# TB-OSW-DRV_V1_0.net
KiCad netlist of a schematic drawn in Altium Designer
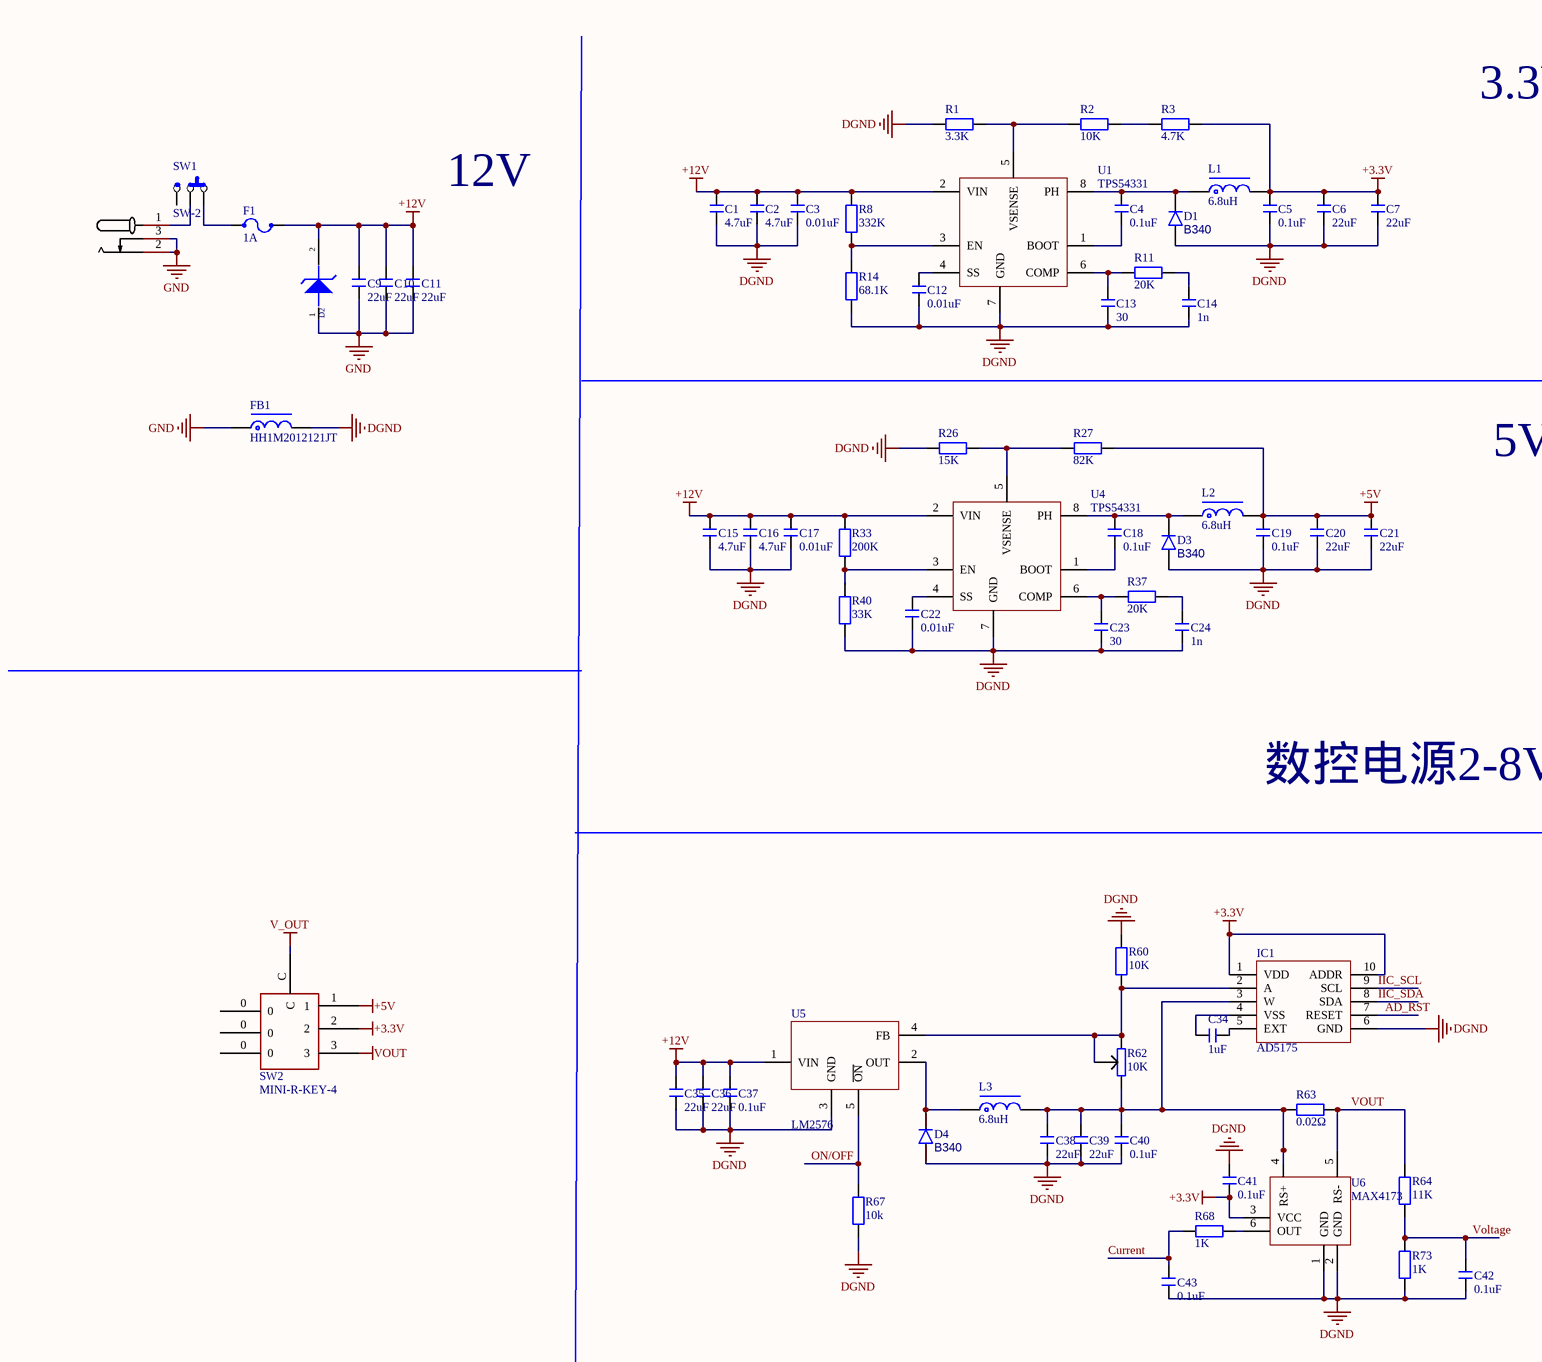
[diagram p0: TB-OSW-DRV V1.0.SchDoc, top left]
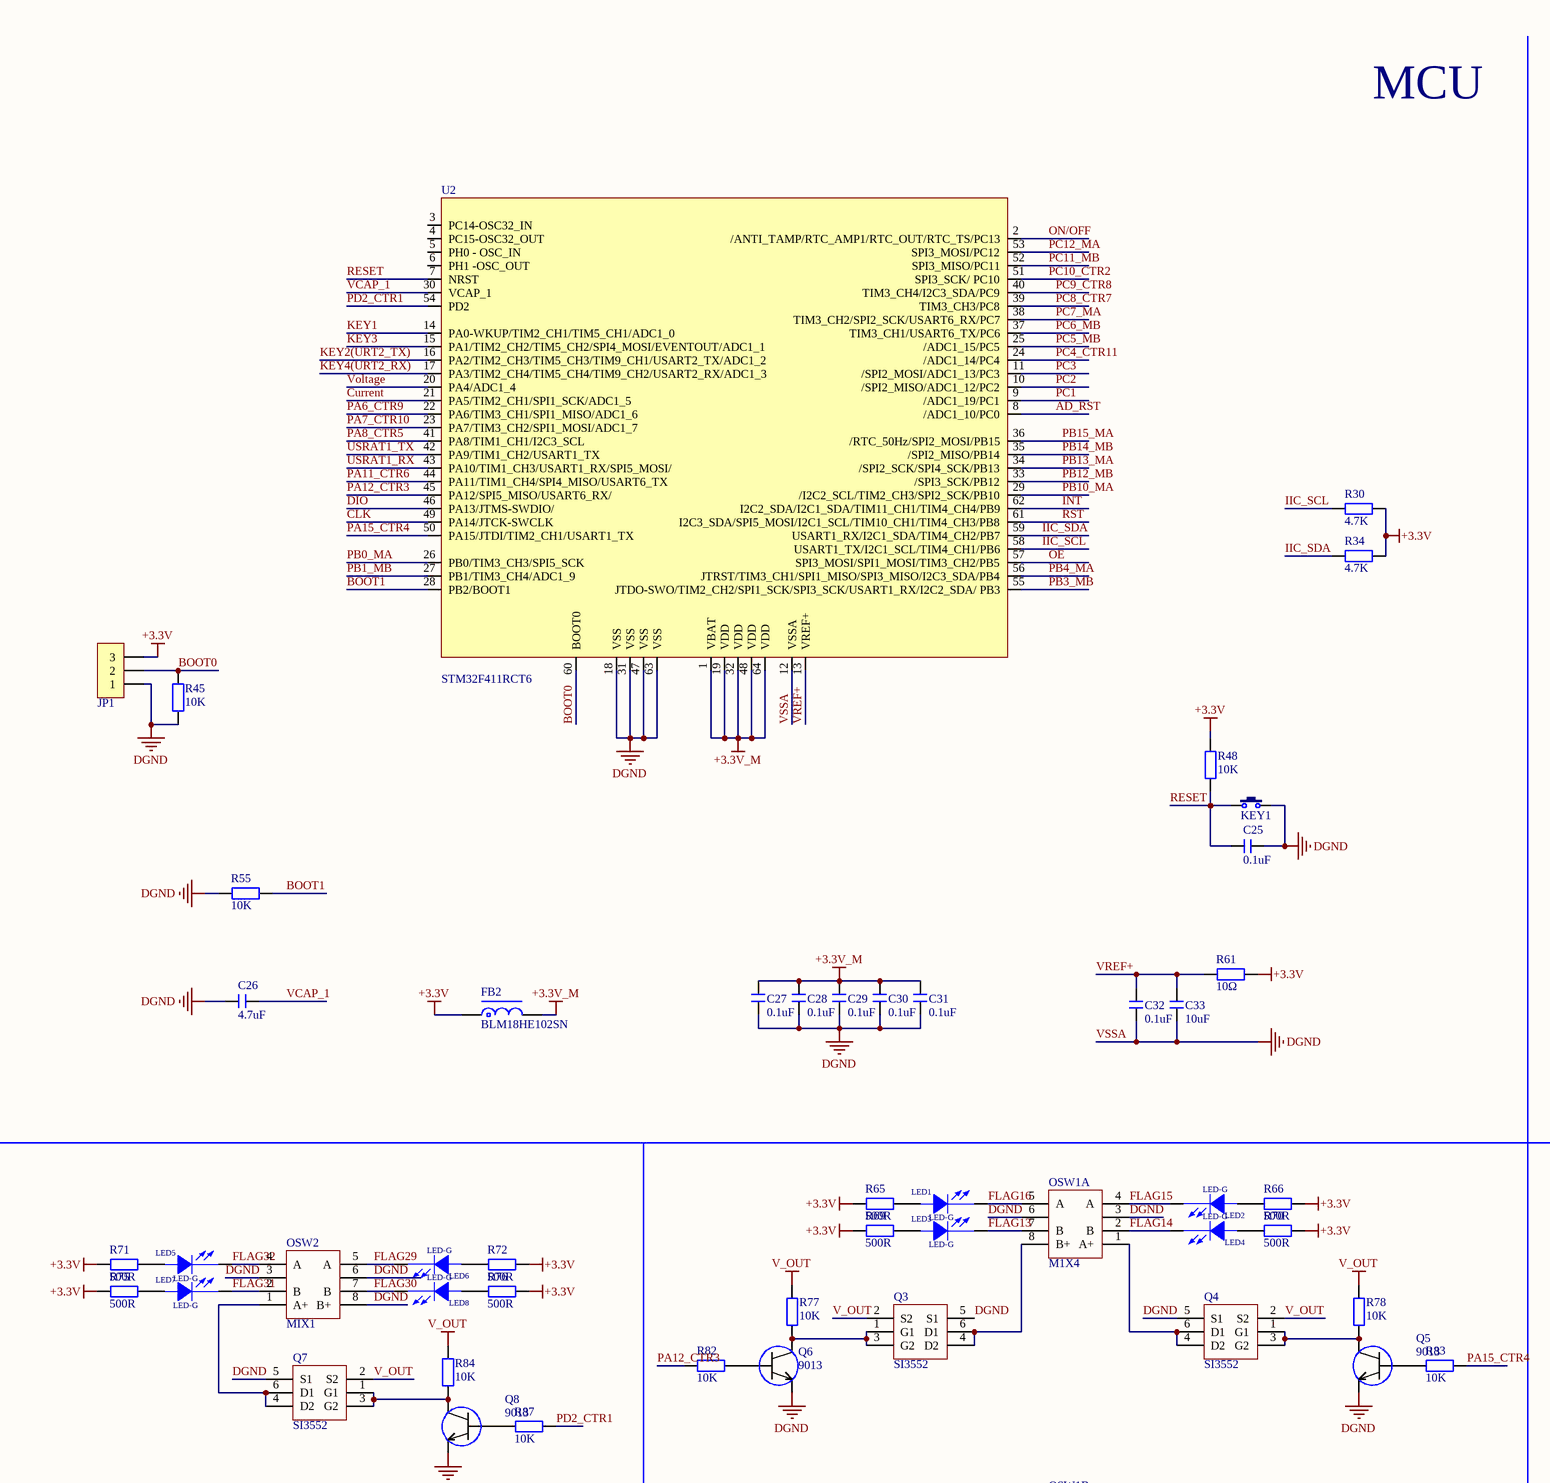
[diagram p1: TB-OSW-DRV V1.0.SchDoc, top middle]
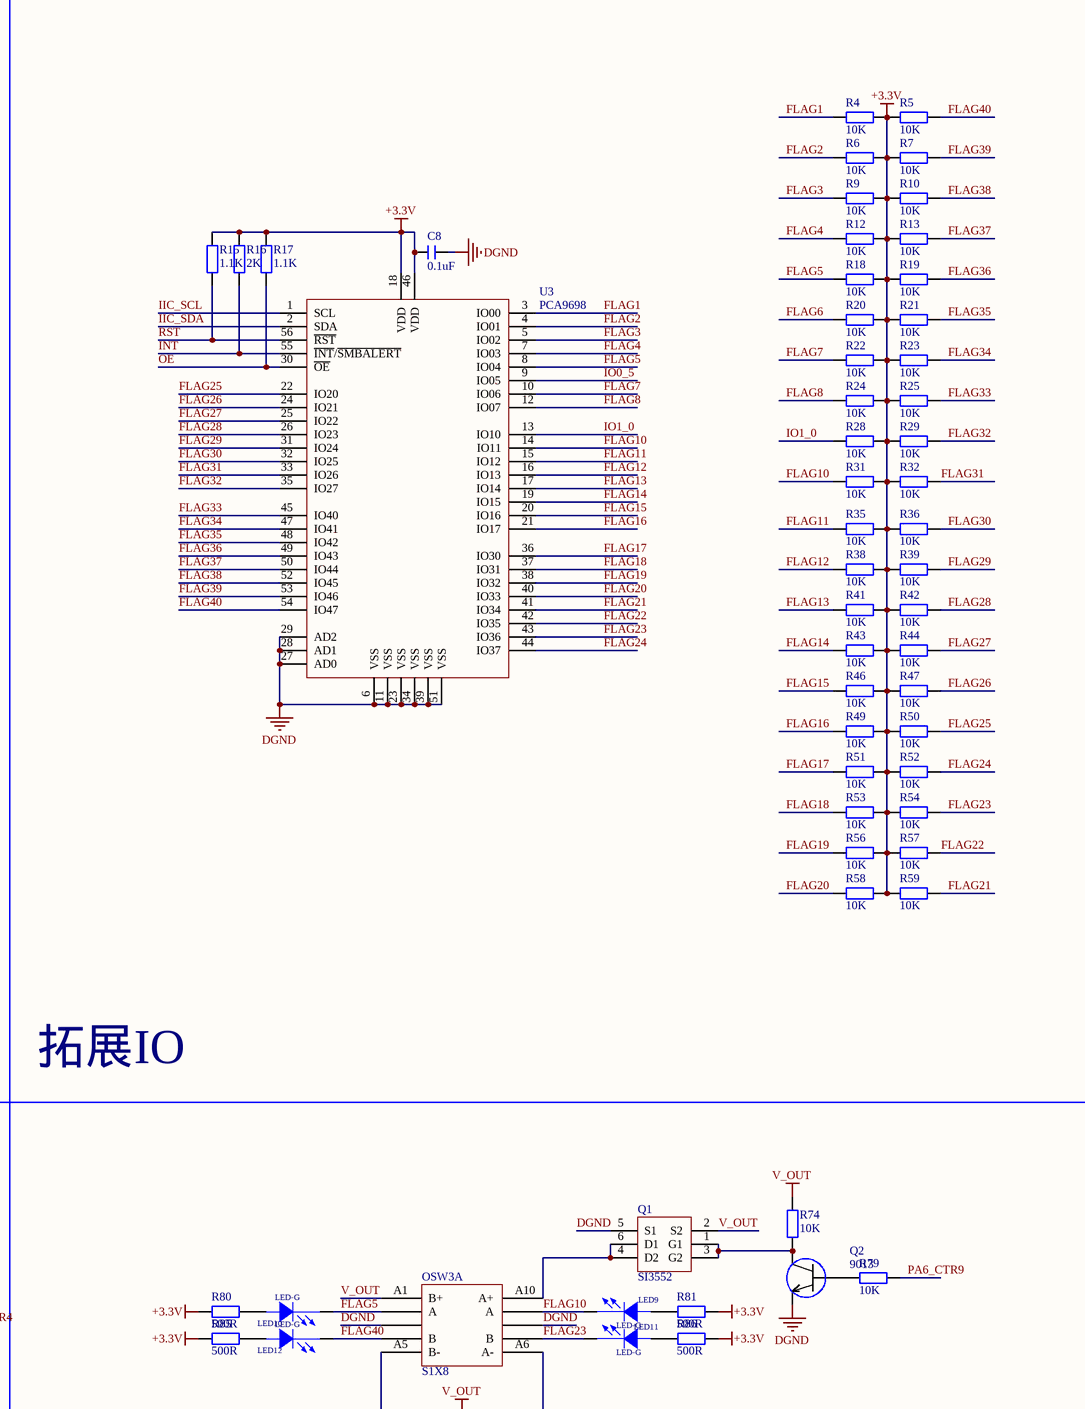
[diagram p2: TB-OSW-DRV V1.0.SchDoc, top right]
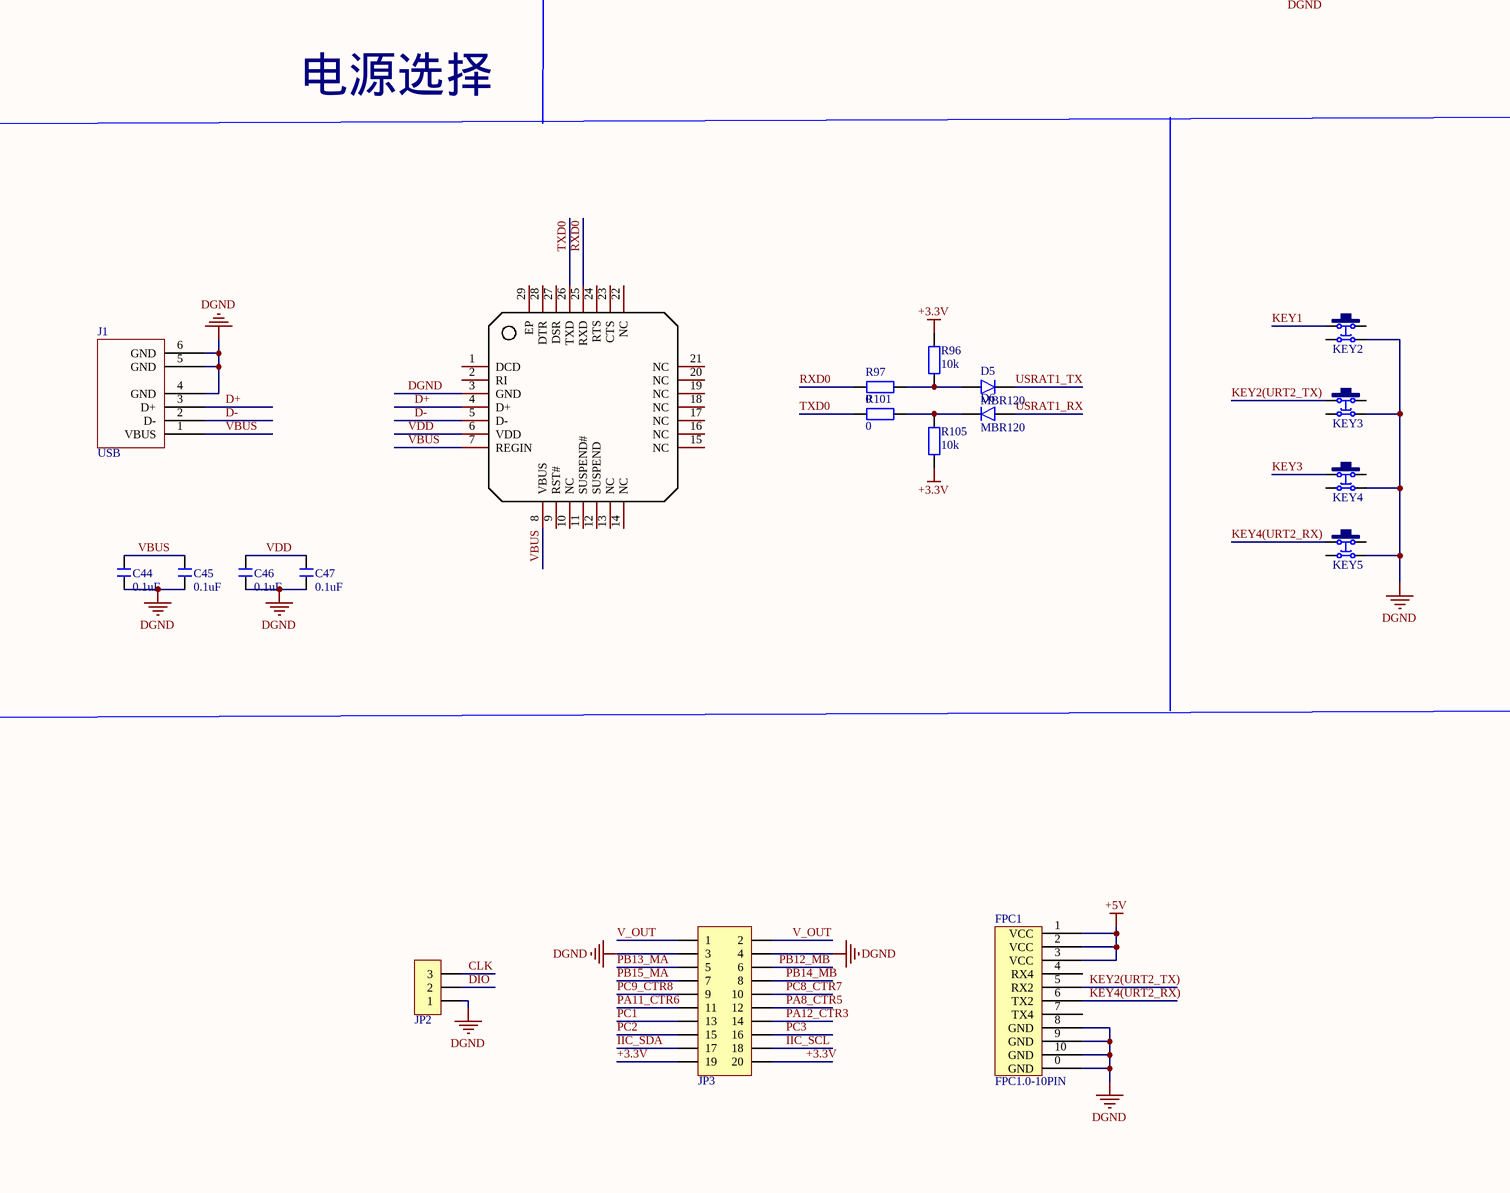
[diagram p3: TB-OSW-DRV V1.0.SchDoc, bottom left]
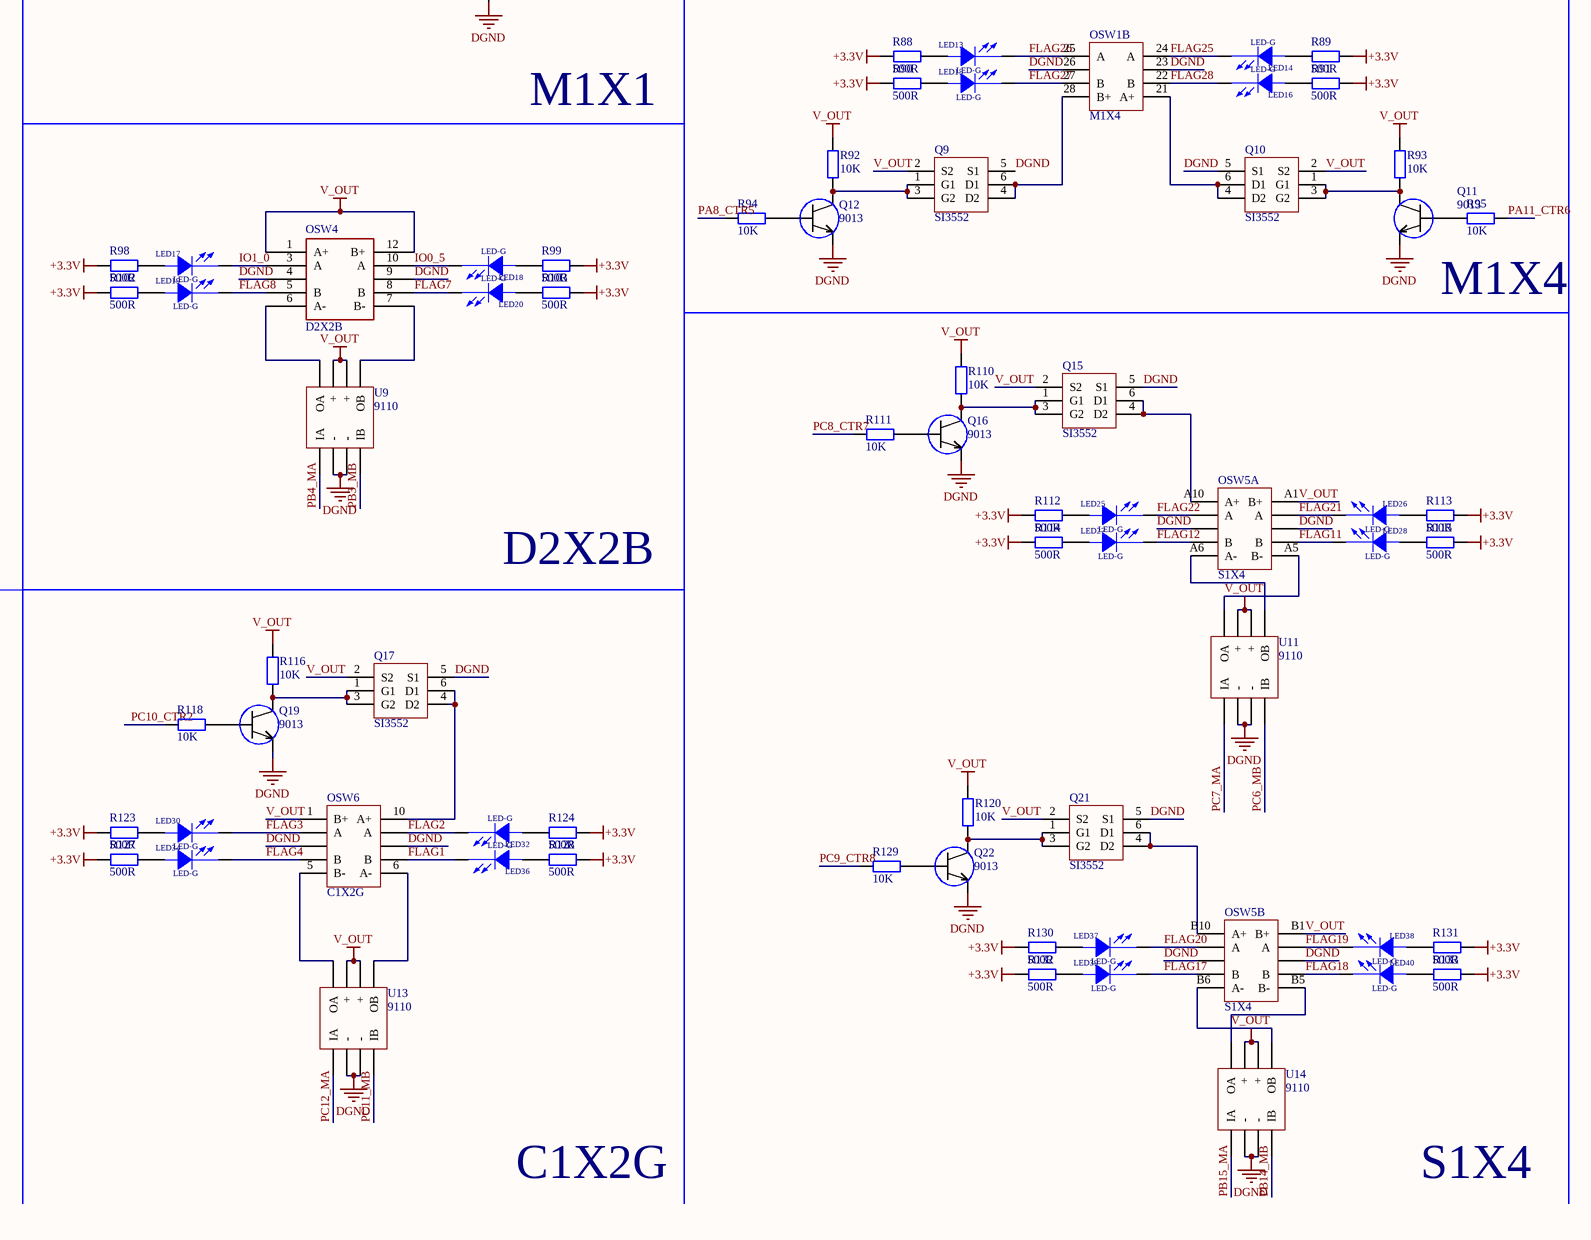
[diagram p4: TB-OSW-DRV V1.0.SchDoc, bottom middle]
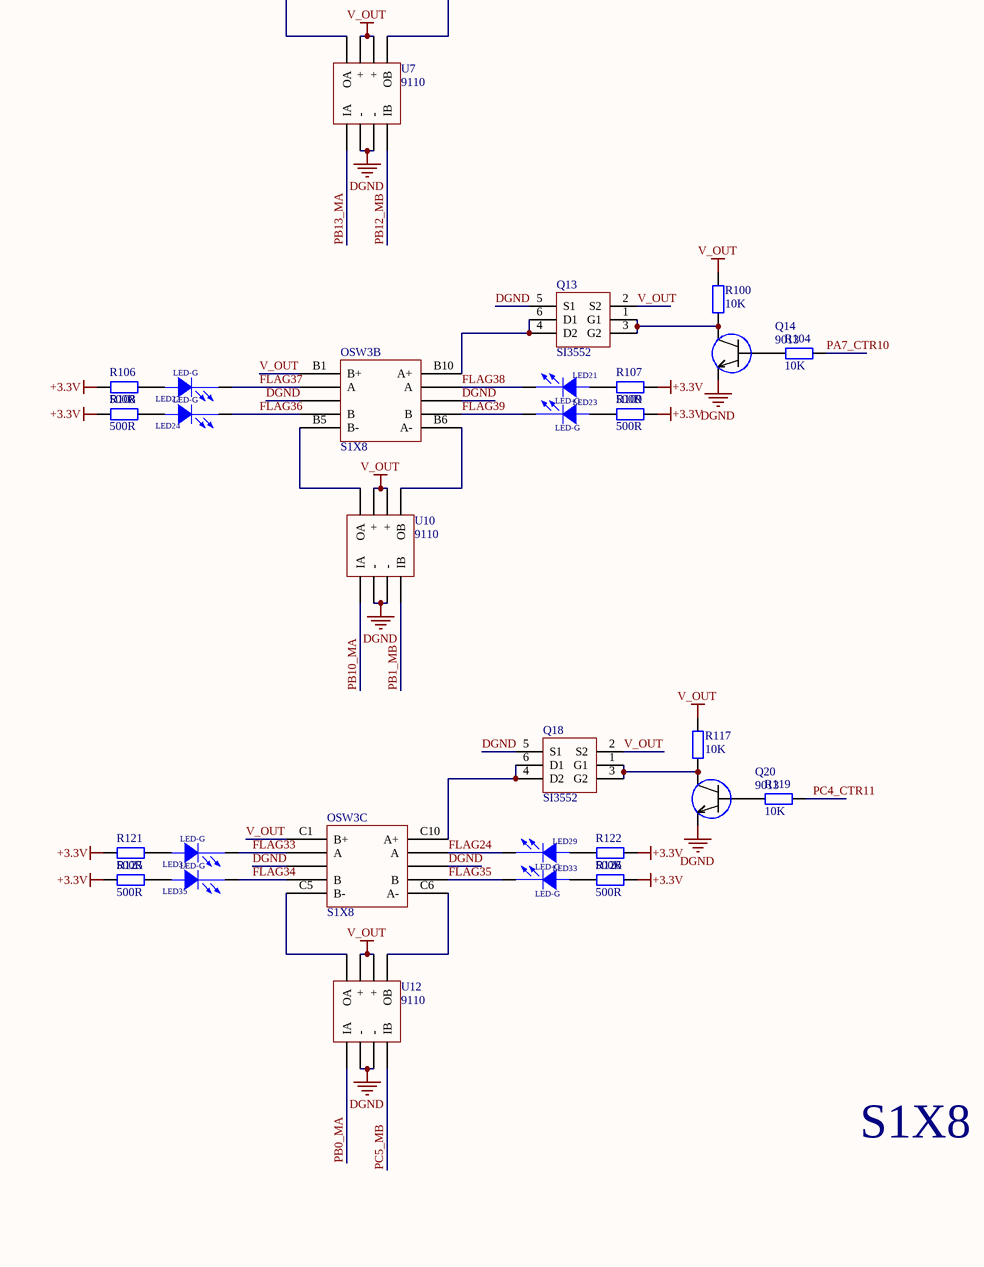
[diagram p5: TB-OSW-DRV V1.0.SchDoc, bottom right]

(export (version "E")
  (design (tool "Eeschema 10.0.6"))
  (components
    (comp (ref "C1")
      (value "4.7uF")
      (footprint "C 0805")
      (description "无极性贴片电容")
      (fields (field (name "版权归属") "源创客"))
      (libsource (lib "电阻-电容-电感") (part "C"))
    )
    (comp (ref "C2")
      (value "4.7uF")
      (footprint "C 0805")
      (description "无极性贴片电容")
      (fields (field (name "版权归属") "源创客"))
      (libsource (lib "电阻-电容-电感") (part "C"))
    )
    (comp (ref "C3")
      (value "0.01uF")
      (footprint "C 0805")
      (description "无极性贴片电容")
      (fields (field (name "版权归属") "源创客"))
      (libsource (lib "电阻-电容-电感") (part "C"))
    )
    (comp (ref "C4")
      (value "0.1uF")
      (footprint "C 0603")
      (description "无极性贴片电容")
      (fields (field (name "版权归属") "源创客"))
      (libsource (lib "电阻-电容-电感") (part "C"))
    )
    (comp (ref "C5")
      (value "0.1uF")
      (footprint "C 0603")
      (description "无极性贴片电容")
      (fields (field (name "版权归属") "源创客"))
      (libsource (lib "电阻-电容-电感") (part "C"))
    )
    (comp (ref "C6")
      (value "22uF")
      (footprint "C 0805")
      (description "无极性贴片电容")
      (fields (field (name "版权归属") "源创客"))
      (libsource (lib "电阻-电容-电感") (part "C"))
    )
    (comp (ref "C7")
      (value "22uF")
      (footprint "C 0805")
      (description "无极性贴片电容")
      (fields (field (name "版权归属") "源创客"))
      (libsource (lib "电阻-电容-电感") (part "C"))
    )
    (comp (ref "C8")
      (value "0.1uF")
      (footprint "C 0603")
      (description "无极性贴片电容")
      (fields (field (name "版权归属") "源创客"))
      (libsource (lib "电阻-电容-电感") (part "C"))
    )
    (comp (ref "C9")
      (value "22uF")
      (footprint "C 1206")
      (description "无极性贴片电容")
      (fields (field (name "版权归属") "源创客"))
      (libsource (lib "电阻-电容-电感") (part "C"))
    )
    (comp (ref "C10")
      (value "22uF")
      (footprint "C 1206")
      (description "无极性贴片电容")
      (fields (field (name "版权归属") "源创客"))
      (libsource (lib "电阻-电容-电感") (part "C"))
    )
    (comp (ref "C11")
      (value "22uF")
      (footprint "C 1206")
      (description "无极性贴片电容")
      (fields (field (name "版权归属") "源创客"))
      (libsource (lib "电阻-电容-电感") (part "C"))
    )
    (comp (ref "C12")
      (value "0.01uF")
      (footprint "C 0603")
      (description "无极性贴片电容")
      (fields (field (name "版权归属") "源创客"))
      (libsource (lib "电阻-电容-电感") (part "C"))
    )
    (comp (ref "C13")
      (value "30")
      (footprint "C 0603")
      (description "无极性贴片电容")
      (fields (field (name "版权归属") "源创客"))
      (libsource (lib "电阻-电容-电感") (part "C"))
    )
    (comp (ref "C14")
      (value "1n")
      (footprint "C 0603")
      (description "无极性贴片电容")
      (fields (field (name "版权归属") "源创客"))
      (libsource (lib "电阻-电容-电感") (part "C"))
    )
    (comp (ref "C15")
      (value "4.7uF")
      (footprint "C 0805")
      (description "无极性贴片电容")
      (fields (field (name "版权归属") "源创客"))
      (libsource (lib "电阻-电容-电感") (part "C"))
    )
    (comp (ref "C16")
      (value "4.7uF")
      (footprint "C 0805")
      (description "无极性贴片电容")
      (fields (field (name "版权归属") "源创客"))
      (libsource (lib "电阻-电容-电感") (part "C"))
    )
    (comp (ref "C17")
      (value "0.01uF")
      (footprint "C 0805")
      (description "无极性贴片电容")
      (fields (field (name "版权归属") "源创客"))
      (libsource (lib "电阻-电容-电感") (part "C"))
    )
    (comp (ref "C18")
      (value "0.1uF")
      (footprint "C 0603")
      (description "无极性贴片电容")
      (fields (field (name "版权归属") "源创客"))
      (libsource (lib "电阻-电容-电感") (part "C"))
    )
    (comp (ref "C19")
      (value "0.1uF")
      (footprint "C 0603")
      (description "无极性贴片电容")
      (fields (field (name "版权归属") "源创客"))
      (libsource (lib "电阻-电容-电感") (part "C"))
    )
    (comp (ref "C20")
      (value "22uF")
      (footprint "C 0805")
      (description "无极性贴片电容")
      (fields (field (name "版权归属") "源创客"))
      (libsource (lib "电阻-电容-电感") (part "C"))
    )
    (comp (ref "C21")
      (value "22uF")
      (footprint "C 0805")
      (description "无极性贴片电容")
      (fields (field (name "版权归属") "源创客"))
      (libsource (lib "电阻-电容-电感") (part "C"))
    )
    (comp (ref "C22")
      (value "0.01uF")
      (footprint "C 0603")
      (description "无极性贴片电容")
      (fields (field (name "版权归属") "源创客"))
      (libsource (lib "电阻-电容-电感") (part "C"))
    )
    (comp (ref "C23")
      (value "30")
      (footprint "C 0603")
      (description "无极性贴片电容")
      (fields (field (name "版权归属") "源创客"))
      (libsource (lib "电阻-电容-电感") (part "C"))
    )
    (comp (ref "C24")
      (value "1n")
      (footprint "C 0603")
      (description "无极性贴片电容")
      (fields (field (name "版权归属") "源创客"))
      (libsource (lib "电阻-电容-电感") (part "C"))
    )
    (comp (ref "C25")
      (value "0.1uF")
      (footprint "C 0603")
      (description "无极性贴片电容")
      (fields (field (name "版权归属") "源创客"))
      (libsource (lib "电阻-电容-电感") (part "C"))
    )
    (comp (ref "C26")
      (value "4.7uF")
      (footprint "C 0603")
      (description "无极性贴片电容")
      (fields (field (name "版权归属") "源创客"))
      (libsource (lib "电阻-电容-电感") (part "C"))
    )
    (comp (ref "C27")
      (value "0.1uF")
      (footprint "C 0603")
      (description "无极性贴片电容")
      (fields (field (name "版权归属") "源创客"))
      (libsource (lib "电阻-电容-电感") (part "C"))
    )
    (comp (ref "C28")
      (value "0.1uF")
      (footprint "C 0603")
      (description "无极性贴片电容")
      (fields (field (name "版权归属") "源创客"))
      (libsource (lib "电阻-电容-电感") (part "C"))
    )
    (comp (ref "C29")
      (value "0.1uF")
      (footprint "C 0603")
      (description "无极性贴片电容")
      (fields (field (name "版权归属") "源创客"))
      (libsource (lib "电阻-电容-电感") (part "C"))
    )
    (comp (ref "C30")
      (value "0.1uF")
      (footprint "C 0603")
      (description "无极性贴片电容")
      (fields (field (name "版权归属") "源创客"))
      (libsource (lib "电阻-电容-电感") (part "C"))
    )
    (comp (ref "C31")
      (value "0.1uF")
      (footprint "C 0603")
      (description "无极性贴片电容")
      (fields (field (name "版权归属") "源创客"))
      (libsource (lib "电阻-电容-电感") (part "C"))
    )
    (comp (ref "C32")
      (value "0.1uF")
      (footprint "C 0603")
      (description "无极性贴片电容")
      (fields (field (name "版权归属") "源创客"))
      (libsource (lib "电阻-电容-电感") (part "C"))
    )
    (comp (ref "C33")
      (value "10uF")
      (footprint "C 0603")
      (description "无极性贴片电容")
      (fields (field (name "版权归属") "源创客"))
      (libsource (lib "电阻-电容-电感") (part "C"))
    )
    (comp (ref "C34")
      (value "1uF")
      (footprint "C 0603")
      (description "无极性贴片电容")
      (fields (field (name "版权归属") "源创客"))
      (libsource (lib "电阻-电容-电感") (part "C"))
    )
    (comp (ref "C35")
      (value "22uF")
      (footprint "C 1206")
      (description "无极性贴片电容")
      (fields (field (name "版权归属") "源创客"))
      (libsource (lib "电阻-电容-电感") (part "C"))
    )
    (comp (ref "C36")
      (value "22uF")
      (footprint "C 1206")
      (description "无极性贴片电容")
      (fields (field (name "版权归属") "源创客"))
      (libsource (lib "电阻-电容-电感") (part "C"))
    )
    (comp (ref "C37")
      (value "0.1uF")
      (footprint "C 0603")
      (description "无极性贴片电容")
      (fields (field (name "版权归属") "源创客"))
      (libsource (lib "电阻-电容-电感") (part "C"))
    )
    (comp (ref "C38")
      (value "22uF")
      (footprint "C 0805")
      (description "无极性贴片电容")
      (fields (field (name "版权归属") "源创客"))
      (libsource (lib "电阻-电容-电感") (part "C"))
    )
    (comp (ref "C39")
      (value "22uF")
      (footprint "C 0805")
      (description "无极性贴片电容")
      (fields (field (name "版权归属") "源创客"))
      (libsource (lib "电阻-电容-电感") (part "C"))
    )
    (comp (ref "C40")
      (value "0.1uF")
      (footprint "C 0603")
      (description "无极性贴片电容")
      (fields (field (name "版权归属") "源创客"))
      (libsource (lib "电阻-电容-电感") (part "C"))
    )
    (comp (ref "C41")
      (value "0.1uF")
      (footprint "C 0603")
      (description "无极性贴片电容")
      (fields (field (name "版权归属") "源创客"))
      (libsource (lib "电阻-电容-电感") (part "C"))
    )
    (comp (ref "C42")
      (value "0.1uF")
      (footprint "C 0603")
      (description "无极性贴片电容")
      (fields (field (name "版权归属") "源创客"))
      (libsource (lib "电阻-电容-电感") (part "C"))
    )
    (comp (ref "C43")
      (value "0.1uF")
      (footprint "C 0603")
      (description "无极性贴片电容")
      (fields (field (name "版权归属") "源创客"))
      (libsource (lib "电阻-电容-电感") (part "C"))
    )
    (comp (ref "C44")
      (value "0.1uF")
      (footprint "C 0603")
      (description "无极性贴片电容")
      (fields (field (name "版权归属") "源创客"))
      (libsource (lib "电阻-电容-电感") (part "C"))
    )
    (comp (ref "C45")
      (value "0.1uF")
      (footprint "C 0603")
      (description "无极性贴片电容")
      (fields (field (name "版权归属") "源创客"))
      (libsource (lib "电阻-电容-电感") (part "C"))
    )
    (comp (ref "C46")
      (value "0.1uF")
      (footprint "C 0603")
      (description "无极性贴片电容")
      (fields (field (name "版权归属") "源创客"))
      (libsource (lib "电阻-电容-电感") (part "C"))
    )
    (comp (ref "C47")
      (value "0.1uF")
      (footprint "C 0603")
      (description "无极性贴片电容")
      (fields (field (name "版权归属") "源创客"))
      (libsource (lib "电阻-电容-电感") (part "C"))
    )
    (comp (ref "D1")
      (value "B340")
      (footprint "d1808")
      (libsource (lib "New_Integrated_Library") (part "DIODE"))
    )
    (comp (ref "D2")
      (value "TVS_SDO5C_SOD-323")
      (footprint "SOD-323")
      (description "1455000041")
      (libsource (lib "New_Integrated_Library") (part "TVS_SDO5C_SOD-323"))
    )
    (comp (ref "D3")
      (value "B340")
      (footprint "d1808")
      (libsource (lib "New_Integrated_Library") (part "DIODE"))
    )
    (comp (ref "D4")
      (value "B340")
      (footprint "d1808")
      (libsource (lib "New_Integrated_Library") (part "DIODE"))
    )
    (comp (ref "D5") (value "MBR120") (footprint "SOD-123") (libsource (lib "Schlib2") (part "MRB120")))
    (comp (ref "D6") (value "MBR120") (footprint "SOD-123") (libsource (lib "Schlib2") (part "MRB120")))
    (comp (ref "DC1")
      (value "DC005")
      (footprint "DC-IN-TH_DC005")
      (fields (field (name "MANUFACTURER") "SHOU HAN(首韩)"))
      (libsource (lib "New_Integrated_Library") (part "DC005"))
    )
    (comp (ref "F1") (value "1A") (footprint "R1206") (libsource (lib "Schlib2") (part "FUSE")))
    (comp (ref "FB1")
      (value "HH1M2012121JT")
      (footprint "L 0805")
      (description "小功率贴片电感")
      (fields (field (name "版权归属") "源创客"))
      (libsource (lib "电阻-电容-电感") (part "L"))
    )
    (comp (ref "FB2")
      (value "BLM18HE102SN")
      (footprint "L 0805")
      (description "小功率贴片电感")
      (fields (field (name "版权归属") "源创客"))
      (libsource (lib "电阻-电容-电感") (part "L"))
    )
    (comp (ref "FPC1")
      (value "FPC1.0-10PIN")
      (footprint "FPC1.0-2H-WS-10P")
      (libsource (lib "Schlib2") (part "2.4迪文串口屏"))
    )
    (comp (ref "IC1") (value "AD5175") (footprint "AD5175") (libsource (lib "Schlib2") (part "AD5175")))
    (comp (ref "J1") (value "USB") (footprint "USB-B") (libsource (lib "Schlib2") (part "USB")))
    (comp (ref "JP1")
      (value "HDR-1X3")
      (footprint "HDR-1X3")
      (description "3P接插件")
      (fields (field (name "版权归属") "源创客"))
      (libsource (lib "接插件") (part "Header 3"))
    )
    (comp (ref "JP2")
      (value "HDR-1X3")
      (footprint "HDR-1X3")
      (description "3P接插件")
      (fields (field (name "版权归属") "源创客"))
      (libsource (lib "接插件") (part "Header 3"))
    )
    (comp (ref "JP3")
      (value "Header 2X10")
      (footprint "HDR-10X2")
      (description "10*2P接插件")
      (fields (field (name "版权归属") "源创客"))
      (libsource (lib "接插件") (part "Header 10X2"))
    )
    (comp (ref "KEY1")
      (value "3x6x5")
      (footprint "TSW SMD-3*6*2.5")
      (description "3x6轻触开关")
      (fields (field (name "版权归属") "源创客"))
      (libsource (lib "按键-开关") (part "TSW 3x6"))
    )
    (comp (ref "KEY2")
      (value "12x12x5")
      (footprint "TSW DIP-12*12*11")
      (description "直插12x12轻触开关")
      (fields (field (name "版权归属") "源创客"))
      (libsource (lib "按键-开关") (part "TSW DIP-12x12"))
    )
    (comp (ref "KEY3")
      (value "12x12x5")
      (footprint "TSW DIP-12*12*11")
      (description "直插12x12轻触开关")
      (fields (field (name "版权归属") "源创客"))
      (libsource (lib "按键-开关") (part "TSW DIP-12x12"))
    )
    (comp (ref "KEY4")
      (value "12x12x5")
      (footprint "TSW DIP-12*12*11")
      (description "直插12x12轻触开关")
      (fields (field (name "版权归属") "源创客"))
      (libsource (lib "按键-开关") (part "TSW DIP-12x12"))
    )
    (comp (ref "KEY5")
      (value "12x12x5")
      (footprint "TSW DIP-12*12*11")
      (description "直插12x12轻触开关")
      (fields (field (name "版权归属") "源创客"))
      (libsource (lib "按键-开关") (part "TSW DIP-12x12"))
    )
    (comp (ref "L1")
      (value "6.8uH")
      (footprint "CD54")
      (description "贴片功率电感")
      (fields (field (name "版权归属") "源创客"))
      (libsource (lib "电阻-电容-电感") (part "L-CD"))
    )
    (comp (ref "L2")
      (value "6.8uH")
      (footprint "CD54")
      (description "贴片功率电感")
      (fields (field (name "版权归属") "源创客"))
      (libsource (lib "电阻-电容-电感") (part "L-CD"))
    )
    (comp (ref "L3")
      (value "6.8uH")
      (footprint "CD54")
      (description "贴片功率电感")
      (fields (field (name "版权归属") "源创客"))
      (libsource (lib "电阻-电容-电感") (part "L-CD"))
    )
    (comp (ref "LED1")
      (value "LED-G")
      (footprint "D0603B")
      (description "5110400395")
      (fields (field (name "Comment") "D_LED-G_D0603"))
      (libsource (lib "Schlib2") (part "D_LED-G_D0603"))
    )
    (comp (ref "LED2")
      (value "LED-G")
      (footprint "D0603B")
      (description "5110400395")
      (fields (field (name "Comment") "D_LED-G_D0603"))
      (libsource (lib "Schlib2") (part "D_LED-G_D0603"))
    )
    (comp (ref "LED3")
      (value "LED-G")
      (footprint "D0603B")
      (description "5110400395")
      (fields (field (name "Comment") "D_LED-G_D0603"))
      (libsource (lib "Schlib2") (part "D_LED-G_D0603"))
    )
    (comp (ref "LED4")
      (value "LED-G")
      (footprint "D0603B")
      (description "5110400395")
      (fields (field (name "Comment") "D_LED-G_D0603"))
      (libsource (lib "Schlib2") (part "D_LED-G_D0603"))
    )
    (comp (ref "LED5")
      (value "LED-G")
      (footprint "D0603B")
      (description "5110400395")
      (fields (field (name "Comment") "D_LED-G_D0603"))
      (libsource (lib "Schlib2") (part "D_LED-G_D0603"))
    )
    (comp (ref "LED6")
      (value "LED-G")
      (footprint "D0603B")
      (description "5110400395")
      (fields (field (name "Comment") "D_LED-G_D0603"))
      (libsource (lib "Schlib2") (part "D_LED-G_D0603"))
    )
    (comp (ref "LED7")
      (value "LED-G")
      (footprint "D0603B")
      (description "5110400395")
      (fields (field (name "Comment") "D_LED-G_D0603"))
      (libsource (lib "Schlib2") (part "D_LED-G_D0603"))
    )
    (comp (ref "LED8")
      (value "LED-G")
      (footprint "D0603B")
      (description "5110400395")
      (fields (field (name "Comment") "D_LED-G_D0603"))
      (libsource (lib "Schlib2") (part "D_LED-G_D0603"))
    )
    (comp (ref "LED9")
      (value "LED-G")
      (footprint "D0603B")
      (description "5110400395")
      (fields (field (name "Comment") "D_LED-G_D0603"))
      (libsource (lib "Schlib2") (part "D_LED-G_D0603"))
    )
    (comp (ref "LED10")
      (value "LED-G")
      (footprint "D0603B")
      (description "5110400395")
      (fields (field (name "Comment") "D_LED-G_D0603"))
      (libsource (lib "Schlib2") (part "D_LED-G_D0603"))
    )
    (comp (ref "LED11")
      (value "LED-G")
      (footprint "D0603B")
      (description "5110400395")
      (fields (field (name "Comment") "D_LED-G_D0603"))
      (libsource (lib "Schlib2") (part "D_LED-G_D0603"))
    )
    (comp (ref "LED12")
      (value "LED-G")
      (footprint "D0603B")
      (description "5110400395")
      (fields (field (name "Comment") "D_LED-G_D0603"))
      (libsource (lib "Schlib2") (part "D_LED-G_D0603"))
    )
    (comp (ref "LED13")
      (value "LED-G")
      (footprint "D0603B")
      (description "5110400395")
      (fields (field (name "Comment") "D_LED-G_D0603"))
      (libsource (lib "Schlib2") (part "D_LED-G_D0603"))
    )
    (comp (ref "LED14")
      (value "LED-G")
      (footprint "D0603B")
      (description "5110400395")
      (fields (field (name "Comment") "D_LED-G_D0603"))
      (libsource (lib "Schlib2") (part "D_LED-G_D0603"))
    )
    (comp (ref "LED15")
      (value "LED-G")
      (footprint "D0603B")
      (description "5110400395")
      (fields (field (name "Comment") "D_LED-G_D0603"))
      (libsource (lib "Schlib2") (part "D_LED-G_D0603"))
    )
    (comp (ref "LED16")
      (value "LED-G")
      (footprint "D0603B")
      (description "5110400395")
      (fields (field (name "Comment") "D_LED-G_D0603"))
      (libsource (lib "Schlib2") (part "D_LED-G_D0603"))
    )
    (comp (ref "LED17")
      (value "LED-G")
      (footprint "D0603B")
      (description "5110400395")
      (fields (field (name "Comment") "D_LED-G_D0603"))
      (libsource (lib "Schlib2") (part "D_LED-G_D0603"))
    )
    (comp (ref "LED18")
      (value "LED-G")
      (footprint "D0603B")
      (description "5110400395")
      (fields (field (name "Comment") "D_LED-G_D0603"))
      (libsource (lib "Schlib2") (part "D_LED-G_D0603"))
    )
    (comp (ref "LED19")
      (value "LED-G")
      (footprint "D0603B")
      (description "5110400395")
      (fields (field (name "Comment") "D_LED-G_D0603"))
      (libsource (lib "Schlib2") (part "D_LED-G_D0603"))
    )
    (comp (ref "LED20")
      (value "LED-G")
      (footprint "D0603B")
      (description "5110400395")
      (fields (field (name "Comment") "D_LED-G_D0603"))
      (libsource (lib "Schlib2") (part "D_LED-G_D0603"))
    )
    (comp (ref "LED21")
      (value "LED-G")
      (footprint "D0603B")
      (description "5110400395")
      (fields (field (name "Comment") "D_LED-G_D0603"))
      (libsource (lib "Schlib2") (part "D_LED-G_D0603"))
    )
    (comp (ref "LED22")
      (value "LED-G")
      (footprint "D0603B")
      (description "5110400395")
      (fields (field (name "Comment") "D_LED-G_D0603"))
      (libsource (lib "Schlib2") (part "D_LED-G_D0603"))
    )
    (comp (ref "LED23")
      (value "LED-G")
      (footprint "D0603B")
      (description "5110400395")
      (fields (field (name "Comment") "D_LED-G_D0603"))
      (libsource (lib "Schlib2") (part "D_LED-G_D0603"))
    )
    (comp (ref "LED24")
      (value "LED-G")
      (footprint "D0603B")
      (description "5110400395")
      (fields (field (name "Comment") "D_LED-G_D0603"))
      (libsource (lib "Schlib2") (part "D_LED-G_D0603"))
    )
    (comp (ref "LED25")
      (value "LED-G")
      (footprint "D0603B")
      (description "5110400395")
      (fields (field (name "Comment") "D_LED-G_D0603"))
      (libsource (lib "Schlib2") (part "D_LED-G_D0603"))
    )
    (comp (ref "LED26")
      (value "LED-G")
      (footprint "D0603B")
      (description "5110400395")
      (fields (field (name "Comment") "D_LED-G_D0603"))
      (libsource (lib "Schlib2") (part "D_LED-G_D0603"))
    )
    (comp (ref "LED27")
      (value "LED-G")
      (footprint "D0603B")
      (description "5110400395")
      (fields (field (name "Comment") "D_LED-G_D0603"))
      (libsource (lib "Schlib2") (part "D_LED-G_D0603"))
    )
    (comp (ref "LED28")
      (value "LED-G")
      (footprint "D0603B")
      (description "5110400395")
      (fields (field (name "Comment") "D_LED-G_D0603"))
      (libsource (lib "Schlib2") (part "D_LED-G_D0603"))
    )
    (comp (ref "LED29")
      (value "LED-G")
      (footprint "D0603B")
      (description "5110400395")
      (fields (field (name "Comment") "D_LED-G_D0603"))
      (libsource (lib "Schlib2") (part "D_LED-G_D0603"))
    )
    (comp (ref "LED30")
      (value "LED-G")
      (footprint "D0603B")
      (description "5110400395")
      (fields (field (name "Comment") "D_LED-G_D0603"))
      (libsource (lib "Schlib2") (part "D_LED-G_D0603"))
    )
    (comp (ref "LED31")
      (value "LED-G")
      (footprint "D0603B")
      (description "5110400395")
      (fields (field (name "Comment") "D_LED-G_D0603"))
      (libsource (lib "Schlib2") (part "D_LED-G_D0603"))
    )
    (comp (ref "LED32")
      (value "LED-G")
      (footprint "D0603B")
      (description "5110400395")
      (fields (field (name "Comment") "D_LED-G_D0603"))
      (libsource (lib "Schlib2") (part "D_LED-G_D0603"))
    )
    (comp (ref "LED33")
      (value "LED-G")
      (footprint "D0603B")
      (description "5110400395")
      (fields (field (name "Comment") "D_LED-G_D0603"))
      (libsource (lib "Schlib2") (part "D_LED-G_D0603"))
    )
    (comp (ref "LED34")
      (value "LED-G")
      (footprint "D0603B")
      (description "5110400395")
      (fields (field (name "Comment") "D_LED-G_D0603"))
      (libsource (lib "Schlib2") (part "D_LED-G_D0603"))
    )
    (comp (ref "LED35")
      (value "LED-G")
      (footprint "D0603B")
      (description "5110400395")
      (fields (field (name "Comment") "D_LED-G_D0603"))
      (libsource (lib "Schlib2") (part "D_LED-G_D0603"))
    )
    (comp (ref "LED36")
      (value "LED-G")
      (footprint "D0603B")
      (description "5110400395")
      (fields (field (name "Comment") "D_LED-G_D0603"))
      (libsource (lib "Schlib2") (part "D_LED-G_D0603"))
    )
    (comp (ref "LED37")
      (value "LED-G")
      (footprint "D0603B")
      (description "5110400395")
      (fields (field (name "Comment") "D_LED-G_D0603"))
      (libsource (lib "Schlib2") (part "D_LED-G_D0603"))
    )
    (comp (ref "LED38")
      (value "LED-G")
      (footprint "D0603B")
      (description "5110400395")
      (fields (field (name "Comment") "D_LED-G_D0603"))
      (libsource (lib "Schlib2") (part "D_LED-G_D0603"))
    )
    (comp (ref "LED39")
      (value "LED-G")
      (footprint "D0603B")
      (description "5110400395")
      (fields (field (name "Comment") "D_LED-G_D0603"))
      (libsource (lib "Schlib2") (part "D_LED-G_D0603"))
    )
    (comp (ref "LED40")
      (value "LED-G")
      (footprint "D0603B")
      (description "5110400395")
      (fields (field (name "Comment") "D_LED-G_D0603"))
      (libsource (lib "Schlib2") (part "D_LED-G_D0603"))
    )
    (comp (ref "OSW1")
      (value "M1X4")
      (footprint "MIN1X4")
      (libsource (lib "New_Integrated_Library") (part "OSWM2"))
    )
    (comp (ref "OSW2")
      (value "MIX1")
      (footprint "M1X1 - duplicate")
      (libsource (lib "New_Integrated_Library") (part "OSWM1"))
    )
    (comp (ref "OSW3")
      (value "S1X8")
      (footprint "S1X8 - duplicate")
      (libsource (lib "New_Integrated_Library") (part "OSW3"))
    )
    (comp (ref "OSW4")
      (value "D2X2B")
      (footprint "D2X2B - duplicate")
      (libsource (lib "Schlib2") (part "D2X2B"))
    )
    (comp (ref "OSW5")
      (value "S1X4")
      (footprint "S1X4 - duplicate")
      (libsource (lib "New_Integrated_Library") (part "OSW2"))
    )
    (comp (ref "OSW6")
      (value "C1X2G")
      (footprint "C1X2G - duplicate")
      (libsource (lib "New_Integrated_Library") (part "OSW1"))
    )
    (comp (ref "Q1") (value "SI3552") (footprint "3552") (libsource (lib "") (part "SI3552_1")))
    (comp (ref "Q2") (value "9013") (footprint "SOT-23") (libsource (lib "Schlib2") (part "S9013_SOT23")))
    (comp (ref "Q3") (value "SI3552") (footprint "3552") (libsource (lib "Schlib2") (part "SI3552")))
    (comp (ref "Q4") (value "SI3552") (footprint "3552") (libsource (lib "") (part "SI3552_1")))
    (comp (ref "Q5") (value "9013") (footprint "SOT-23") (libsource (lib "Schlib2") (part "S9013_SOT23")))
    (comp (ref "Q6") (value "9013") (footprint "SOT-23") (libsource (lib "") (part "S9013_SOT23_1")))
    (comp (ref "Q7") (value "SI3552") (footprint "3552") (libsource (lib "") (part "SI3552_1")))
    (comp (ref "Q8") (value "9013") (footprint "SOT-23") (libsource (lib "Schlib2") (part "S9013_SOT23")))
    (comp (ref "Q9") (value "SI3552") (footprint "3552") (libsource (lib "Schlib2") (part "SI3552")))
    (comp (ref "Q10") (value "SI3552") (footprint "3552") (libsource (lib "") (part "SI3552_1")))
    (comp (ref "Q11") (value "9013") (footprint "SOT-23") (libsource (lib "Schlib2") (part "S9013_SOT23")))
    (comp (ref "Q12") (value "9013") (footprint "SOT-23") (libsource (lib "") (part "S9013_SOT23_1")))
    (comp (ref "Q13") (value "SI3552") (footprint "3552") (libsource (lib "") (part "SI3552_1")))
    (comp (ref "Q14") (value "9013") (footprint "SOT-23") (libsource (lib "Schlib2") (part "S9013_SOT23")))
    (comp (ref "Q15") (value "SI3552") (footprint "3552") (libsource (lib "Schlib2") (part "SI3552")))
    (comp (ref "Q16") (value "9013") (footprint "SOT-23") (libsource (lib "") (part "S9013_SOT23_1")))
    (comp (ref "Q17") (value "SI3552") (footprint "3552") (libsource (lib "Schlib2") (part "SI3552")))
    (comp (ref "Q18") (value "SI3552") (footprint "3552") (libsource (lib "") (part "SI3552_1")))
    (comp (ref "Q19") (value "9013") (footprint "SOT-23") (libsource (lib "") (part "S9013_SOT23_1")))
    (comp (ref "Q20") (value "9013") (footprint "SOT-23") (libsource (lib "Schlib2") (part "S9013_SOT23")))
    (comp (ref "Q21") (value "SI3552") (footprint "3552") (libsource (lib "Schlib2") (part "SI3552")))
    (comp (ref "Q22") (value "9013") (footprint "SOT-23") (libsource (lib "") (part "S9013_SOT23_1")))
    (comp (ref "R1")
      (value "3.3K")
      (footprint "R 0603")
      (description "贴片电阻")
      (fields (field (name "版权归属") "源创客"))
      (libsource (lib "电阻-电容-电感") (part "R"))
    )
    (comp (ref "R2")
      (value "10K")
      (footprint "R 0603")
      (description "贴片电阻")
      (fields (field (name "版权归属") "源创客"))
      (libsource (lib "电阻-电容-电感") (part "R"))
    )
    (comp (ref "R3")
      (value "4.7K")
      (footprint "R 0603")
      (description "贴片电阻")
      (fields (field (name "版权归属") "源创客"))
      (libsource (lib "电阻-电容-电感") (part "R"))
    )
    (comp (ref "R4")
      (value "10K")
      (footprint "R 0603")
      (description "贴片电阻")
      (fields (field (name "版权归属") "源创客"))
      (libsource (lib "电阻-电容-电感") (part "R"))
    )
    (comp (ref "R5")
      (value "10K")
      (footprint "R 0603")
      (description "贴片电阻")
      (fields (field (name "版权归属") "源创客"))
      (libsource (lib "电阻-电容-电感") (part "R"))
    )
    (comp (ref "R6")
      (value "10K")
      (footprint "R 0603")
      (description "贴片电阻")
      (fields (field (name "版权归属") "源创客"))
      (libsource (lib "电阻-电容-电感") (part "R"))
    )
    (comp (ref "R7")
      (value "10K")
      (footprint "R 0603")
      (description "贴片电阻")
      (fields (field (name "版权归属") "源创客"))
      (libsource (lib "电阻-电容-电感") (part "R"))
    )
    (comp (ref "R8")
      (value "332K")
      (footprint "R 0603")
      (description "贴片电阻")
      (fields (field (name "版权归属") "源创客"))
      (libsource (lib "电阻-电容-电感") (part "R"))
    )
    (comp (ref "R9")
      (value "10K")
      (footprint "R 0603")
      (description "贴片电阻")
      (fields (field (name "版权归属") "源创客"))
      (libsource (lib "电阻-电容-电感") (part "R"))
    )
    (comp (ref "R10")
      (value "10K")
      (footprint "R 0603")
      (description "贴片电阻")
      (fields (field (name "版权归属") "源创客"))
      (libsource (lib "电阻-电容-电感") (part "R"))
    )
    (comp (ref "R11")
      (value "20K")
      (footprint "R 0603")
      (description "贴片电阻")
      (fields (field (name "版权归属") "源创客"))
      (libsource (lib "电阻-电容-电感") (part "R"))
    )
    (comp (ref "R12")
      (value "10K")
      (footprint "R 0603")
      (description "贴片电阻")
      (fields (field (name "版权归属") "源创客"))
      (libsource (lib "电阻-电容-电感") (part "R"))
    )
    (comp (ref "R13")
      (value "10K")
      (footprint "R 0603")
      (description "贴片电阻")
      (fields (field (name "版权归属") "源创客"))
      (libsource (lib "电阻-电容-电感") (part "R"))
    )
    (comp (ref "R14")
      (value "68.1K")
      (footprint "R 0603")
      (description "贴片电阻")
      (fields (field (name "版权归属") "源创客"))
      (libsource (lib "电阻-电容-电感") (part "R"))
    )
    (comp (ref "R15")
      (value "1.1K")
      (footprint "R 0603")
      (description "贴片电阻")
      (fields (field (name "版权归属") "源创客"))
      (libsource (lib "电阻-电容-电感") (part "R"))
    )
    (comp (ref "R16")
      (value "2K")
      (footprint "R 0603")
      (description "贴片电阻")
      (fields (field (name "版权归属") "源创客"))
      (libsource (lib "电阻-电容-电感") (part "R"))
    )
    (comp (ref "R17")
      (value "1.1K")
      (footprint "R 0603")
      (description "贴片电阻")
      (fields (field (name "版权归属") "源创客"))
      (libsource (lib "电阻-电容-电感") (part "R"))
    )
    (comp (ref "R18")
      (value "10K")
      (footprint "R 0603")
      (description "贴片电阻")
      (fields (field (name "版权归属") "源创客"))
      (libsource (lib "电阻-电容-电感") (part "R"))
    )
    (comp (ref "R19")
      (value "10K")
      (footprint "R 0603")
      (description "贴片电阻")
      (fields (field (name "版权归属") "源创客"))
      (libsource (lib "电阻-电容-电感") (part "R"))
    )
    (comp (ref "R20")
      (value "10K")
      (footprint "R 0603")
      (description "贴片电阻")
      (fields (field (name "版权归属") "源创客"))
      (libsource (lib "电阻-电容-电感") (part "R"))
    )
    (comp (ref "R21")
      (value "10K")
      (footprint "R 0603")
      (description "贴片电阻")
      (fields (field (name "版权归属") "源创客"))
      (libsource (lib "电阻-电容-电感") (part "R"))
    )
    (comp (ref "R22")
      (value "10K")
      (footprint "R 0603")
      (description "贴片电阻")
      (fields (field (name "版权归属") "源创客"))
      (libsource (lib "电阻-电容-电感") (part "R"))
    )
    (comp (ref "R23")
      (value "10K")
      (footprint "R 0603")
      (description "贴片电阻")
      (fields (field (name "版权归属") "源创客"))
      (libsource (lib "电阻-电容-电感") (part "R"))
    )
    (comp (ref "R24")
      (value "10K")
      (footprint "R 0603")
      (description "贴片电阻")
      (fields (field (name "版权归属") "源创客"))
      (libsource (lib "电阻-电容-电感") (part "R"))
    )
    (comp (ref "R25")
      (value "10K")
      (footprint "R 0603")
      (description "贴片电阻")
      (fields (field (name "版权归属") "源创客"))
      (libsource (lib "电阻-电容-电感") (part "R"))
    )
    (comp (ref "R26")
      (value "15K")
      (footprint "R 0603")
      (description "贴片电阻")
      (fields (field (name "版权归属") "源创客"))
      (libsource (lib "电阻-电容-电感") (part "R"))
    )
    (comp (ref "R27")
      (value "82K")
      (footprint "R 0603")
      (description "贴片电阻")
      (fields (field (name "版权归属") "源创客"))
      (libsource (lib "电阻-电容-电感") (part "R"))
    )
    (comp (ref "R28")
      (value "10K")
      (footprint "R 0603")
      (description "贴片电阻")
      (fields (field (name "版权归属") "源创客"))
      (libsource (lib "电阻-电容-电感") (part "R"))
    )
    (comp (ref "R29")
      (value "10K")
      (footprint "R 0603")
      (description "贴片电阻")
      (fields (field (name "版权归属") "源创客"))
      (libsource (lib "电阻-电容-电感") (part "R"))
    )
    (comp (ref "R30")
      (value "4.7K")
      (footprint "R 0603")
      (description "贴片电阻")
      (fields (field (name "版权归属") "源创客"))
      (libsource (lib "电阻-电容-电感") (part "R"))
    )
    (comp (ref "R31")
      (value "10K")
      (footprint "R 0603")
      (description "贴片电阻")
      (fields (field (name "版权归属") "源创客"))
      (libsource (lib "电阻-电容-电感") (part "R"))
    )
    (comp (ref "R32")
      (value "10K")
      (footprint "R 0603")
      (description "贴片电阻")
      (fields (field (name "版权归属") "源创客"))
      (libsource (lib "电阻-电容-电感") (part "R"))
    )
    (comp (ref "R33")
      (value "200K")
      (footprint "R 0603")
      (description "贴片电阻")
      (fields (field (name "版权归属") "源创客"))
      (libsource (lib "电阻-电容-电感") (part "R"))
    )
    (comp (ref "R34")
      (value "4.7K")
      (footprint "R 0603")
      (description "贴片电阻")
      (fields (field (name "版权归属") "源创客"))
      (libsource (lib "电阻-电容-电感") (part "R"))
    )
    (comp (ref "R35")
      (value "10K")
      (footprint "R 0603")
      (description "贴片电阻")
      (fields (field (name "版权归属") "源创客"))
      (libsource (lib "电阻-电容-电感") (part "R"))
    )
    (comp (ref "R36")
      (value "10K")
      (footprint "R 0603")
      (description "贴片电阻")
      (fields (field (name "版权归属") "源创客"))
      (libsource (lib "电阻-电容-电感") (part "R"))
    )
    (comp (ref "R37")
      (value "20K")
      (footprint "R 0603")
      (description "贴片电阻")
      (fields (field (name "版权归属") "源创客"))
      (libsource (lib "电阻-电容-电感") (part "R"))
    )
    (comp (ref "R38")
      (value "10K")
      (footprint "R 0603")
      (description "贴片电阻")
      (fields (field (name "版权归属") "源创客"))
      (libsource (lib "电阻-电容-电感") (part "R"))
    )
    (comp (ref "R39")
      (value "10K")
      (footprint "R 0603")
      (description "贴片电阻")
      (fields (field (name "版权归属") "源创客"))
      (libsource (lib "电阻-电容-电感") (part "R"))
    )
    (comp (ref "R40")
      (value "33K")
      (footprint "R 0603")
      (description "贴片电阻")
      (fields (field (name "版权归属") "源创客"))
      (libsource (lib "电阻-电容-电感") (part "R"))
    )
    (comp (ref "R41")
      (value "10K")
      (footprint "R 0603")
      (description "贴片电阻")
      (fields (field (name "版权归属") "源创客"))
      (libsource (lib "电阻-电容-电感") (part "R"))
    )
    (comp (ref "R42")
      (value "10K")
      (footprint "R 0603")
      (description "贴片电阻")
      (fields (field (name "版权归属") "源创客"))
      (libsource (lib "电阻-电容-电感") (part "R"))
    )
    (comp (ref "R43")
      (value "10K")
      (footprint "R 0603")
      (description "贴片电阻")
      (fields (field (name "版权归属") "源创客"))
      (libsource (lib "电阻-电容-电感") (part "R"))
    )
    (comp (ref "R44")
      (value "10K")
      (footprint "R 0603")
      (description "贴片电阻")
      (fields (field (name "版权归属") "源创客"))
      (libsource (lib "电阻-电容-电感") (part "R"))
    )
    (comp (ref "R45")
      (value "10K")
      (footprint "R 0603")
      (description "贴片电阻")
      (fields (field (name "版权归属") "源创客"))
      (libsource (lib "电阻-电容-电感") (part "R"))
    )
    (comp (ref "R46")
      (value "10K")
      (footprint "R 0603")
      (description "贴片电阻")
      (fields (field (name "版权归属") "源创客"))
      (libsource (lib "电阻-电容-电感") (part "R"))
    )
    (comp (ref "R47")
      (value "10K")
      (footprint "R 0603")
      (description "贴片电阻")
      (fields (field (name "版权归属") "源创客"))
      (libsource (lib "电阻-电容-电感") (part "R"))
    )
    (comp (ref "R48")
      (value "10K")
      (footprint "R 0603")
      (description "贴片电阻")
      (fields (field (name "版权归属") "源创客"))
      (libsource (lib "电阻-电容-电感") (part "R"))
    )
    (comp (ref "R49")
      (value "10K")
      (footprint "R 0603")
      (description "贴片电阻")
      (fields (field (name "版权归属") "源创客"))
      (libsource (lib "电阻-电容-电感") (part "R"))
    )
    (comp (ref "R50")
      (value "10K")
      (footprint "R 0603")
      (description "贴片电阻")
      (fields (field (name "版权归属") "源创客"))
      (libsource (lib "电阻-电容-电感") (part "R"))
    )
    (comp (ref "R51")
      (value "10K")
      (footprint "R 0603")
      (description "贴片电阻")
      (fields (field (name "版权归属") "源创客"))
      (libsource (lib "电阻-电容-电感") (part "R"))
    )
    (comp (ref "R52")
      (value "10K")
      (footprint "R 0603")
      (description "贴片电阻")
      (fields (field (name "版权归属") "源创客"))
      (libsource (lib "电阻-电容-电感") (part "R"))
    )
    (comp (ref "R53")
      (value "10K")
      (footprint "R 0603")
      (description "贴片电阻")
      (fields (field (name "版权归属") "源创客"))
      (libsource (lib "电阻-电容-电感") (part "R"))
    )
    (comp (ref "R54")
      (value "10K")
      (footprint "R 0603")
      (description "贴片电阻")
      (fields (field (name "版权归属") "源创客"))
      (libsource (lib "电阻-电容-电感") (part "R"))
    )
    (comp (ref "R55")
      (value "10K")
      (footprint "R 0603")
      (description "贴片电阻")
      (fields (field (name "版权归属") "源创客"))
      (libsource (lib "电阻-电容-电感") (part "R"))
    )
    (comp (ref "R56")
      (value "10K")
      (footprint "R 0603")
      (description "贴片电阻")
      (fields (field (name "版权归属") "源创客"))
      (libsource (lib "电阻-电容-电感") (part "R"))
    )
    (comp (ref "R57")
      (value "10K")
      (footprint "R 0603")
      (description "贴片电阻")
      (fields (field (name "版权归属") "源创客"))
      (libsource (lib "电阻-电容-电感") (part "R"))
    )
    (comp (ref "R58")
      (value "10K")
      (footprint "R 0603")
      (description "贴片电阻")
      (fields (field (name "版权归属") "源创客"))
      (libsource (lib "电阻-电容-电感") (part "R"))
    )
    (comp (ref "R59")
      (value "10K")
      (footprint "R 0603")
      (description "贴片电阻")
      (fields (field (name "版权归属") "源创客"))
      (libsource (lib "电阻-电容-电感") (part "R"))
    )
    (comp (ref "R60")
      (value "10K")
      (footprint "R 0603")
      (description "贴片电阻")
      (fields (field (name "版权归属") "源创客"))
      (libsource (lib "电阻-电容-电感") (part "R"))
    )
    (comp (ref "R61")
      (value "10Ω")
      (footprint "R 0603")
      (description "贴片电阻")
      (fields (field (name "版权归属") "源创客"))
      (libsource (lib "电阻-电容-电感") (part "R"))
    )
    (comp (ref "R62") (value "10K") (footprint "3296W") (libsource (lib "Schlib2") (part "RES-V")))
    (comp (ref "R63")
      (value "0.02Ω")
      (footprint "R 1206")
      (description "贴片电阻")
      (fields (field (name "版权归属") "源创客"))
      (libsource (lib "电阻-电容-电感") (part "R"))
    )
    (comp (ref "R64")
      (value "11K")
      (footprint "R 0603")
      (description "贴片电阻")
      (fields (field (name "版权归属") "源创客"))
      (libsource (lib "电阻-电容-电感") (part "R"))
    )
    (comp (ref "R65")
      (value "500R")
      (footprint "R 0603")
      (description "贴片电阻")
      (fields (field (name "版权归属") "源创客"))
      (libsource (lib "电阻-电容-电感") (part "R"))
    )
    (comp (ref "R66")
      (value "500R")
      (footprint "R 0603")
      (description "贴片电阻")
      (fields (field (name "版权归属") "源创客"))
      (libsource (lib "电阻-电容-电感") (part "R"))
    )
    (comp (ref "R67")
      (value "10k")
      (footprint "R 0603")
      (description "贴片电阻")
      (fields (field (name "版权归属") "源创客"))
      (libsource (lib "电阻-电容-电感") (part "R"))
    )
    (comp (ref "R68")
      (value "1K")
      (footprint "R 0603")
      (description "贴片电阻")
      (fields (field (name "版权归属") "源创客"))
      (libsource (lib "电阻-电容-电感") (part "R"))
    )
    (comp (ref "R69")
      (value "500R")
      (footprint "R 0603")
      (description "贴片电阻")
      (fields (field (name "版权归属") "源创客"))
      (libsource (lib "电阻-电容-电感") (part "R"))
    )
    (comp (ref "R70")
      (value "500R")
      (footprint "R 0603")
      (description "贴片电阻")
      (fields (field (name "版权归属") "源创客"))
      (libsource (lib "电阻-电容-电感") (part "R"))
    )
    (comp (ref "R71")
      (value "500R")
      (footprint "R 0603")
      (description "贴片电阻")
      (fields (field (name "版权归属") "源创客"))
      (libsource (lib "电阻-电容-电感") (part "R"))
    )
    (comp (ref "R72")
      (value "500R")
      (footprint "R 0603")
      (description "贴片电阻")
      (fields (field (name "版权归属") "源创客"))
      (libsource (lib "电阻-电容-电感") (part "R"))
    )
    (comp (ref "R73")
      (value "1K")
      (footprint "R 0603")
      (description "贴片电阻")
      (fields (field (name "版权归属") "源创客"))
      (libsource (lib "电阻-电容-电感") (part "R"))
    )
    (comp (ref "R74")
      (value "10K")
      (footprint "R 0603")
      (description "贴片电阻")
      (fields (field (name "版权归属") "源创客"))
      (libsource (lib "电阻-电容-电感") (part "R"))
    )
    (comp (ref "R75")
      (value "500R")
      (footprint "R 0603")
      (description "贴片电阻")
      (fields (field (name "版权归属") "源创客"))
      (libsource (lib "电阻-电容-电感") (part "R"))
    )
    (comp (ref "R76")
      (value "500R")
      (footprint "R 0603")
      (description "贴片电阻")
      (fields (field (name "版权归属") "源创客"))
      (libsource (lib "电阻-电容-电感") (part "R"))
    )
    (comp (ref "R77")
      (value "10K")
      (footprint "R 0603")
      (description "贴片电阻")
      (fields (field (name "版权归属") "源创客"))
      (libsource (lib "电阻-电容-电感") (part "R"))
    )
    (comp (ref "R78")
      (value "10K")
      (footprint "R 0603")
      (description "贴片电阻")
      (fields (field (name "版权归属") "源创客"))
      (libsource (lib "电阻-电容-电感") (part "R"))
    )
    (comp (ref "R79")
      (value "10K")
      (footprint "R 0603")
      (description "贴片电阻")
      (fields (field (name "版权归属") "源创客"))
      (libsource (lib "电阻-电容-电感") (part "R"))
    )
    (comp (ref "R80")
      (value "500R")
      (footprint "R 0603")
      (description "贴片电阻")
      (fields (field (name "版权归属") "源创客"))
      (libsource (lib "电阻-电容-电感") (part "R"))
    )
    (comp (ref "R81")
      (value "500R")
      (footprint "R 0603")
      (description "贴片电阻")
      (fields (field (name "版权归属") "源创客"))
      (libsource (lib "电阻-电容-电感") (part "R"))
    )
    (comp (ref "R82")
      (value "10K")
      (footprint "R 0603")
      (description "贴片电阻")
      (fields (field (name "版权归属") "源创客"))
      (libsource (lib "电阻-电容-电感") (part "R"))
    )
    (comp (ref "R83")
      (value "10K")
      (footprint "R 0603")
      (description "贴片电阻")
      (fields (field (name "版权归属") "源创客"))
      (libsource (lib "电阻-电容-电感") (part "R"))
    )
    (comp (ref "R84")
      (value "10K")
      (footprint "R 0603")
      (description "贴片电阻")
      (fields (field (name "版权归属") "源创客"))
      (libsource (lib "电阻-电容-电感") (part "R"))
    )
    (comp (ref "R85")
      (value "500R")
      (footprint "R 0603")
      (description "贴片电阻")
      (fields (field (name "版权归属") "源创客"))
      (libsource (lib "电阻-电容-电感") (part "R"))
    )
    (comp (ref "R86")
      (value "500R")
      (footprint "R 0603")
      (description "贴片电阻")
      (fields (field (name "版权归属") "源创客"))
      (libsource (lib "电阻-电容-电感") (part "R"))
    )
    (comp (ref "R87")
      (value "10K")
      (footprint "R 0603")
      (description "贴片电阻")
      (fields (field (name "版权归属") "源创客"))
      (libsource (lib "电阻-电容-电感") (part "R"))
    )
    (comp (ref "R88")
      (value "500R")
      (footprint "R 0603")
      (description "贴片电阻")
      (fields (field (name "版权归属") "源创客"))
      (libsource (lib "电阻-电容-电感") (part "R"))
    )
    (comp (ref "R89")
      (value "500R")
      (footprint "R 0603")
      (description "贴片电阻")
      (fields (field (name "版权归属") "源创客"))
      (libsource (lib "电阻-电容-电感") (part "R"))
    )
    (comp (ref "R90")
      (value "500R")
      (footprint "R 0603")
      (description "贴片电阻")
      (fields (field (name "版权归属") "源创客"))
      (libsource (lib "电阻-电容-电感") (part "R"))
    )
    (comp (ref "R91")
      (value "500R")
      (footprint "R 0603")
      (description "贴片电阻")
      (fields (field (name "版权归属") "源创客"))
      (libsource (lib "电阻-电容-电感") (part "R"))
    )
    (comp (ref "R92")
      (value "10K")
      (footprint "R 0603")
      (description "贴片电阻")
      (fields (field (name "版权归属") "源创客"))
      (libsource (lib "电阻-电容-电感") (part "R"))
    )
    (comp (ref "R93")
      (value "10K")
      (footprint "R 0603")
      (description "贴片电阻")
      (fields (field (name "版权归属") "源创客"))
      (libsource (lib "电阻-电容-电感") (part "R"))
    )
    (comp (ref "R94")
      (value "10K")
      (footprint "R 0603")
      (description "贴片电阻")
      (fields (field (name "版权归属") "源创客"))
      (libsource (lib "电阻-电容-电感") (part "R"))
    )
    (comp (ref "R95")
      (value "10K")
      (footprint "R 0603")
      (description "贴片电阻")
      (fields (field (name "版权归属") "源创客"))
      (libsource (lib "电阻-电容-电感") (part "R"))
    )
    (comp (ref "R96")
      (value "10k")
      (footprint "R 0603")
      (description "贴片电阻")
      (fields (field (name "版权归属") "源创客"))
      (libsource (lib "电阻-电容-电感") (part "R"))
    )
    (comp (ref "R97")
      (value "0")
      (footprint "R 0603")
      (description "贴片电阻")
      (fields (field (name "版权归属") "源创客"))
      (libsource (lib "电阻-电容-电感") (part "R"))
    )
    (comp (ref "R98")
      (value "500R")
      (footprint "R 0603")
      (description "贴片电阻")
      (fields (field (name "版权归属") "源创客"))
      (libsource (lib "电阻-电容-电感") (part "R"))
    )
    (comp (ref "R99")
      (value "500R")
      (footprint "R 0603")
      (description "贴片电阻")
      (fields (field (name "版权归属") "源创客"))
      (libsource (lib "电阻-电容-电感") (part "R"))
    )
    (comp (ref "R100")
      (value "10K")
      (footprint "R 0603")
      (description "贴片电阻")
      (fields (field (name "版权归属") "源创客"))
      (libsource (lib "电阻-电容-电感") (part "R"))
    )
    (comp (ref "R101")
      (value "0")
      (footprint "R 0603")
      (description "贴片电阻")
      (fields (field (name "版权归属") "源创客"))
      (libsource (lib "电阻-电容-电感") (part "R"))
    )
    (comp (ref "R102")
      (value "500R")
      (footprint "R 0603")
      (description "贴片电阻")
      (fields (field (name "版权归属") "源创客"))
      (libsource (lib "电阻-电容-电感") (part "R"))
    )
    (comp (ref "R103")
      (value "500R")
      (footprint "R 0603")
      (description "贴片电阻")
      (fields (field (name "版权归属") "源创客"))
      (libsource (lib "电阻-电容-电感") (part "R"))
    )
    (comp (ref "R104")
      (value "10K")
      (footprint "R 0603")
      (description "贴片电阻")
      (fields (field (name "版权归属") "源创客"))
      (libsource (lib "电阻-电容-电感") (part "R"))
    )
    (comp (ref "R105")
      (value "10k")
      (footprint "R 0603")
      (description "贴片电阻")
      (fields (field (name "版权归属") "源创客"))
      (libsource (lib "电阻-电容-电感") (part "R"))
    )
    (comp (ref "R106")
      (value "500R")
      (footprint "R 0603")
      (description "贴片电阻")
      (fields (field (name "版权归属") "源创客"))
      (libsource (lib "电阻-电容-电感") (part "R"))
    )
    (comp (ref "R107")
      (value "500R")
      (footprint "R 0603")
      (description "贴片电阻")
      (fields (field (name "版权归属") "源创客"))
      (libsource (lib "电阻-电容-电感") (part "R"))
    )
    (comp (ref "R108")
      (value "500R")
      (footprint "R 0603")
      (description "贴片电阻")
      (fields (field (name "版权归属") "源创客"))
      (libsource (lib "电阻-电容-电感") (part "R"))
    )
    (comp (ref "R109")
      (value "500R")
      (footprint "R 0603")
      (description "贴片电阻")
      (fields (field (name "版权归属") "源创客"))
      (libsource (lib "电阻-电容-电感") (part "R"))
    )
    (comp (ref "R110")
      (value "10K")
      (footprint "R 0603")
      (description "贴片电阻")
      (fields (field (name "版权归属") "源创客"))
      (libsource (lib "电阻-电容-电感") (part "R"))
    )
    (comp (ref "R111")
      (value "10K")
      (footprint "R 0603")
      (description "贴片电阻")
      (fields (field (name "版权归属") "源创客"))
      (libsource (lib "电阻-电容-电感") (part "R"))
    )
    (comp (ref "R112")
      (value "500R")
      (footprint "R 0603")
      (description "贴片电阻")
      (fields (field (name "版权归属") "源创客"))
      (libsource (lib "电阻-电容-电感") (part "R"))
    )
    (comp (ref "R113")
      (value "500R")
      (footprint "R 0603")
      (description "贴片电阻")
      (fields (field (name "版权归属") "源创客"))
      (libsource (lib "电阻-电容-电感") (part "R"))
    )
    (comp (ref "R114")
      (value "500R")
      (footprint "R 0603")
      (description "贴片电阻")
      (fields (field (name "版权归属") "源创客"))
      (libsource (lib "电阻-电容-电感") (part "R"))
    )
    (comp (ref "R115")
      (value "500R")
      (footprint "R 0603")
      (description "贴片电阻")
      (fields (field (name "版权归属") "源创客"))
      (libsource (lib "电阻-电容-电感") (part "R"))
    )
    (comp (ref "R116")
      (value "10K")
      (footprint "R 0603")
      (description "贴片电阻")
      (fields (field (name "版权归属") "源创客"))
      (libsource (lib "电阻-电容-电感") (part "R"))
    )
    (comp (ref "R117")
      (value "10K")
      (footprint "R 0603")
      (description "贴片电阻")
      (fields (field (name "版权归属") "源创客"))
      (libsource (lib "电阻-电容-电感") (part "R"))
    )
    (comp (ref "R118")
      (value "10K")
      (footprint "R 0603")
      (description "贴片电阻")
      (fields (field (name "版权归属") "源创客"))
      (libsource (lib "电阻-电容-电感") (part "R"))
    )
    (comp (ref "R119")
      (value "10K")
      (footprint "R 0603")
      (description "贴片电阻")
      (fields (field (name "版权归属") "源创客"))
      (libsource (lib "电阻-电容-电感") (part "R"))
    )
    (comp (ref "R120")
      (value "10K")
      (footprint "R 0603")
      (description "贴片电阻")
      (fields (field (name "版权归属") "源创客"))
      (libsource (lib "电阻-电容-电感") (part "R"))
    )
    (comp (ref "R121")
      (value "500R")
      (footprint "R 0603")
      (description "贴片电阻")
      (fields (field (name "版权归属") "源创客"))
      (libsource (lib "电阻-电容-电感") (part "R"))
    )
    (comp (ref "R122")
      (value "500R")
      (footprint "R 0603")
      (description "贴片电阻")
      (fields (field (name "版权归属") "源创客"))
      (libsource (lib "电阻-电容-电感") (part "R"))
    )
    (comp (ref "R123")
      (value "500R")
      (footprint "R 0603")
      (description "贴片电阻")
      (fields (field (name "版权归属") "源创客"))
      (libsource (lib "电阻-电容-电感") (part "R"))
    )
    (comp (ref "R124")
      (value "500R")
      (footprint "R 0603")
      (description "贴片电阻")
      (fields (field (name "版权归属") "源创客"))
      (libsource (lib "电阻-电容-电感") (part "R"))
    )
    (comp (ref "R125")
      (value "500R")
      (footprint "R 0603")
      (description "贴片电阻")
      (fields (field (name "版权归属") "源创客"))
      (libsource (lib "电阻-电容-电感") (part "R"))
    )
    (comp (ref "R126")
      (value "500R")
      (footprint "R 0603")
      (description "贴片电阻")
      (fields (field (name "版权归属") "源创客"))
      (libsource (lib "电阻-电容-电感") (part "R"))
    )
    (comp (ref "R127")
      (value "500R")
      (footprint "R 0603")
      (description "贴片电阻")
      (fields (field (name "版权归属") "源创客"))
      (libsource (lib "电阻-电容-电感") (part "R"))
    )
    (comp (ref "R128")
      (value "500R")
      (footprint "R 0603")
      (description "贴片电阻")
      (fields (field (name "版权归属") "源创客"))
      (libsource (lib "电阻-电容-电感") (part "R"))
    )
    (comp (ref "R129")
      (value "10K")
      (footprint "R 0603")
      (description "贴片电阻")
      (fields (field (name "版权归属") "源创客"))
      (libsource (lib "电阻-电容-电感") (part "R"))
    )
    (comp (ref "R130")
      (value "500R")
      (footprint "R 0603")
      (description "贴片电阻")
      (fields (field (name "版权归属") "源创客"))
      (libsource (lib "电阻-电容-电感") (part "R"))
    )
    (comp (ref "R131")
      (value "500R")
      (footprint "R 0603")
      (description "贴片电阻")
      (fields (field (name "版权归属") "源创客"))
      (libsource (lib "电阻-电容-电感") (part "R"))
    )
    (comp (ref "R132")
      (value "500R")
      (footprint "R 0603")
      (description "贴片电阻")
      (fields (field (name "版权归属") "源创客"))
      (libsource (lib "电阻-电容-电感") (part "R"))
    )
    (comp (ref "R133")
      (value "500R")
      (footprint "R 0603")
      (description "贴片电阻")
      (fields (field (name "版权归属") "源创客"))
      (libsource (lib "电阻-电容-电感") (part "R"))
    )
    (comp (ref "SW1") (value "SW-2") (footprint "SWSD - V") (libsource (lib "glsun") (part "SW-2")))
    (comp (ref "SW2")
      (value "MINI-R-KEY-4")
      (footprint "MINI-R-KEY-4")
      (libsource (lib "Schlib2") (part "MINI-R-KEY-4"))
    )
    (comp (ref "U1")
      (value "TPS54331")
      (footprint "SOP8")
      (libsource (lib "New_Integrated_Library") (part "TPS54331_SOP8"))
    )
    (comp (ref "U2")
      (value "STM32F411RCT6")
      (footprint "TQFP64")
      (libsource (lib "New_Integrated_Library") (part "STM32F411_64"))
    )
    (comp (ref "U3") (value "PCA9698") (footprint "PCA9698") (libsource (lib "Schlib2") (part "PCA9698_")))
    (comp (ref "U4")
      (value "TPS54331")
      (footprint "SOP8")
      (libsource (lib "New_Integrated_Library") (part "TPS54331_SOP8"))
    )
    (comp (ref "U5")
      (value "LM2576")
      (footprint "TO-263-5")
      (libsource (lib "New_Integrated_Library") (part "LM2576"))
    )
    (comp (ref "U6")
      (value "MAX4173")
      (footprint "SOT-23-6")
      (libsource (lib "New_Integrated_Library") (part "MAX4173_SOT23-6"))
    )
    (comp (ref "U7") (value "9110") (footprint "SOP8") (libsource (lib "Schlib2") (part "L9110S_SOP8")))
    (comp (ref "U8")
      (value "CP2102-GMR")
      (footprint "WQFN-28_L5.0-W5.0-P0.50-BL-EP3.2")
      (fields (field (name "MANUFACTURER") "SILICON LABS(芯科)"))
      (libsource (lib "Schlib2") (part "CP2102-GMR"))
    )
    (comp (ref "U9") (value "9110") (footprint "SOP8") (libsource (lib "Schlib2") (part "L9110S_SOP8")))
    (comp (ref "U10") (value "9110") (footprint "SOP8") (libsource (lib "Schlib2") (part "L9110S_SOP8")))
    (comp (ref "U11") (value "9110") (footprint "SOP8") (libsource (lib "Schlib2") (part "L9110S_SOP8")))
    (comp (ref "U12") (value "9110") (footprint "SOP8") (libsource (lib "Schlib2") (part "L9110S_SOP8")))
    (comp (ref "U13") (value "9110") (footprint "SOP8") (libsource (lib "Schlib2") (part "L9110S_SOP8")))
    (comp (ref "U14") (value "9110") (footprint "SOP8") (libsource (lib "Schlib2") (part "L9110S_SOP8")))
  )
  (nets
    (net (code "1") (name "+3.3V") (class "Default")
      (node (ref "C41") (pin "1") (pinfunction "1_1") (pintype "passive"))
      (node (ref "C5") (pin "1") (pinfunction "1_1") (pintype "passive"))
      (node (ref "C6") (pin "1") (pinfunction "1_1") (pintype "passive"))
      (node (ref "C7") (pin "1") (pinfunction "1_1") (pintype "passive"))
      (node (ref "C8") (pin "2") (pinfunction "2_2") (pintype "passive"))
      (node (ref "FB2") (pin "1") (pinfunction "1_1") (pintype "passive"))
      (node (ref "IC1") (pin "1") (pinfunction "VDD_1") (pintype "passive"))
      (node (ref "IC1") (pin "10") (pinfunction "ADDR_10") (pintype "passive"))
      (node (ref "JP1") (pin "3") (pinfunction "3_3") (pintype "passive"))
      (node (ref "JP3") (pin "19") (pinfunction "19_19") (pintype "passive"))
      (node (ref "JP3") (pin "20") (pinfunction "20_20") (pintype "passive"))
      (node (ref "L1") (pin "2") (pinfunction "2_2") (pintype "passive"))
      (node (ref "R10") (pin "2") (pinfunction "2_2") (pintype "passive"))
      (node (ref "R102") (pin "2") (pinfunction "2_2") (pintype "passive"))
      (node (ref "R103") (pin "1") (pinfunction "1_1") (pintype "passive"))
      (node (ref "R105") (pin "1") (pinfunction "1_1") (pintype "passive"))
      (node (ref "R106") (pin "1") (pinfunction "1_1") (pintype "passive"))
      (node (ref "R107") (pin "2") (pinfunction "2_2") (pintype "passive"))
      (node (ref "R108") (pin "2") (pinfunction "2_2") (pintype "passive"))
      (node (ref "R109") (pin "1") (pinfunction "1_1") (pintype "passive"))
      (node (ref "R112") (pin "2") (pinfunction "2_2") (pintype "passive"))
      (node (ref "R113") (pin "2") (pinfunction "2_2") (pintype "passive"))
      (node (ref "R114") (pin "1") (pinfunction "1_1") (pintype "passive"))
      (node (ref "R115") (pin "1") (pinfunction "1_1") (pintype "passive"))
      (node (ref "R12") (pin "1") (pinfunction "1_1") (pintype "passive"))
      (node (ref "R121") (pin "1") (pinfunction "1_1") (pintype "passive"))
      (node (ref "R122") (pin "2") (pinfunction "2_2") (pintype "passive"))
      (node (ref "R123") (pin "2") (pinfunction "2_2") (pintype "passive"))
      (node (ref "R124") (pin "2") (pinfunction "2_2") (pintype "passive"))
      (node (ref "R125") (pin "2") (pinfunction "2_2") (pintype "passive"))
      (node (ref "R126") (pin "1") (pinfunction "1_1") (pintype "passive"))
      (node (ref "R127") (pin "1") (pinfunction "1_1") (pintype "passive"))
      (node (ref "R128") (pin "1") (pinfunction "1_1") (pintype "passive"))
      (node (ref "R13") (pin "2") (pinfunction "2_2") (pintype "passive"))
      (node (ref "R130") (pin "2") (pinfunction "2_2") (pintype "passive"))
      (node (ref "R131") (pin "2") (pinfunction "2_2") (pintype "passive"))
      (node (ref "R132") (pin "1") (pinfunction "1_1") (pintype "passive"))
      (node (ref "R133") (pin "1") (pinfunction "1_1") (pintype "passive"))
      (node (ref "R15") (pin "1") (pinfunction "1_1") (pintype "passive"))
      (node (ref "R16") (pin "1") (pinfunction "1_1") (pintype "passive"))
      (node (ref "R17") (pin "1") (pinfunction "1_1") (pintype "passive"))
      (node (ref "R18") (pin "1") (pinfunction "1_1") (pintype "passive"))
      (node (ref "R19") (pin "2") (pinfunction "2_2") (pintype "passive"))
      (node (ref "R20") (pin "1") (pinfunction "1_1") (pintype "passive"))
      (node (ref "R21") (pin "2") (pinfunction "2_2") (pintype "passive"))
      (node (ref "R22") (pin "1") (pinfunction "1_1") (pintype "passive"))
      (node (ref "R23") (pin "2") (pinfunction "2_2") (pintype "passive"))
      (node (ref "R24") (pin "1") (pinfunction "1_1") (pintype "passive"))
      (node (ref "R25") (pin "2") (pinfunction "2_2") (pintype "passive"))
      (node (ref "R28") (pin "1") (pinfunction "1_1") (pintype "passive"))
      (node (ref "R29") (pin "2") (pinfunction "2_2") (pintype "passive"))
      (node (ref "R3") (pin "2") (pinfunction "2_2") (pintype "passive"))
      (node (ref "R30") (pin "1") (pinfunction "1_1") (pintype "passive"))
      (node (ref "R31") (pin "1") (pinfunction "1_1") (pintype "passive"))
      (node (ref "R32") (pin "2") (pinfunction "2_2") (pintype "passive"))
      (node (ref "R34") (pin "1") (pinfunction "1_1") (pintype "passive"))
      (node (ref "R35") (pin "1") (pinfunction "1_1") (pintype "passive"))
      (node (ref "R36") (pin "2") (pinfunction "2_2") (pintype "passive"))
      (node (ref "R38") (pin "1") (pinfunction "1_1") (pintype "passive"))
      (node (ref "R39") (pin "2") (pinfunction "2_2") (pintype "passive"))
      (node (ref "R4") (pin "1") (pinfunction "1_1") (pintype "passive"))
      (node (ref "R41") (pin "1") (pinfunction "1_1") (pintype "passive"))
      (node (ref "R42") (pin "2") (pinfunction "2_2") (pintype "passive"))
      (node (ref "R43") (pin "1") (pinfunction "1_1") (pintype "passive"))
      (node (ref "R44") (pin "2") (pinfunction "2_2") (pintype "passive"))
      (node (ref "R46") (pin "1") (pinfunction "1_1") (pintype "passive"))
      (node (ref "R47") (pin "2") (pinfunction "2_2") (pintype "passive"))
      (node (ref "R48") (pin "2") (pinfunction "2_2") (pintype "passive"))
      (node (ref "R49") (pin "1") (pinfunction "1_1") (pintype "passive"))
      (node (ref "R5") (pin "2") (pinfunction "2_2") (pintype "passive"))
      (node (ref "R50") (pin "2") (pinfunction "2_2") (pintype "passive"))
      (node (ref "R51") (pin "1") (pinfunction "1_1") (pintype "passive"))
      (node (ref "R52") (pin "2") (pinfunction "2_2") (pintype "passive"))
      (node (ref "R53") (pin "1") (pinfunction "1_1") (pintype "passive"))
      (node (ref "R54") (pin "2") (pinfunction "2_2") (pintype "passive"))
      (node (ref "R56") (pin "1") (pinfunction "1_1") (pintype "passive"))
      (node (ref "R57") (pin "2") (pinfunction "2_2") (pintype "passive"))
      (node (ref "R58") (pin "1") (pinfunction "1_1") (pintype "passive"))
      (node (ref "R59") (pin "2") (pinfunction "2_2") (pintype "passive"))
      (node (ref "R6") (pin "1") (pinfunction "1_1") (pintype "passive"))
      (node (ref "R61") (pin "1") (pinfunction "1_1") (pintype "passive"))
      (node (ref "R65") (pin "2") (pinfunction "2_2") (pintype "passive"))
      (node (ref "R66") (pin "2") (pinfunction "2_2") (pintype "passive"))
      (node (ref "R69") (pin "1") (pinfunction "1_1") (pintype "passive"))
      (node (ref "R7") (pin "2") (pinfunction "2_2") (pintype "passive"))
      (node (ref "R70") (pin "1") (pinfunction "1_1") (pintype "passive"))
      (node (ref "R71") (pin "1") (pinfunction "1_1") (pintype "passive"))
      (node (ref "R72") (pin "2") (pinfunction "2_2") (pintype "passive"))
      (node (ref "R75") (pin "2") (pinfunction "2_2") (pintype "passive"))
      (node (ref "R76") (pin "1") (pinfunction "1_1") (pintype "passive"))
      (node (ref "R80") (pin "1") (pinfunction "1_1") (pintype "passive"))
      (node (ref "R81") (pin "2") (pinfunction "2_2") (pintype "passive"))
      (node (ref "R85") (pin "2") (pinfunction "2_2") (pintype "passive"))
      (node (ref "R86") (pin "1") (pinfunction "1_1") (pintype "passive"))
      (node (ref "R88") (pin "2") (pinfunction "2_2") (pintype "passive"))
      (node (ref "R89") (pin "2") (pinfunction "2_2") (pintype "passive"))
      (node (ref "R9") (pin "1") (pinfunction "1_1") (pintype "passive"))
      (node (ref "R90") (pin "1") (pinfunction "1_1") (pintype "passive"))
      (node (ref "R91") (pin "1") (pinfunction "1_1") (pintype "passive"))
      (node (ref "R96") (pin "2") (pinfunction "2_2") (pintype "passive"))
      (node (ref "R98") (pin "1") (pinfunction "1_1") (pintype "passive"))
      (node (ref "R99") (pin "2") (pinfunction "2_2") (pintype "passive"))
      (node (ref "SW2") (pin "2") (pinfunction "2_2") (pintype "passive"))
      (node (ref "U3") (pin "18") (pinfunction "VDD_18") (pintype "passive"))
      (node (ref "U3") (pin "46") (pinfunction "VDD_46") (pintype "passive"))
      (node (ref "U6") (pin "3") (pinfunction "VCC_3") (pintype "passive"))
    )
    (net (code "2") (name "+3.3V_M") (class "Default")
      (node (ref "C27") (pin "1") (pinfunction "1_1") (pintype "passive"))
      (node (ref "C28") (pin "1") (pinfunction "1_1") (pintype "passive"))
      (node (ref "C29") (pin "1") (pinfunction "1_1") (pintype "passive"))
      (node (ref "C30") (pin "1") (pinfunction "1_1") (pintype "passive"))
      (node (ref "C31") (pin "1") (pinfunction "1_1") (pintype "passive"))
      (node (ref "FB2") (pin "2") (pinfunction "2_2") (pintype "passive"))
      (node (ref "U2") (pin "1") (pinfunction "VBAT_1") (pintype "passive"))
      (node (ref "U2") (pin "19") (pinfunction "VDD_19") (pintype "passive"))
      (node (ref "U2") (pin "32") (pinfunction "VDD_32") (pintype "passive"))
      (node (ref "U2") (pin "48") (pinfunction "VDD_48") (pintype "passive"))
      (node (ref "U2") (pin "64") (pinfunction "VDD_64") (pintype "passive"))
    )
    (net (code "3") (name "+5V") (class "Default")
      (node (ref "C19") (pin "1") (pinfunction "1_1") (pintype "passive"))
      (node (ref "C20") (pin "1") (pinfunction "1_1") (pintype "passive"))
      (node (ref "C21") (pin "1") (pinfunction "1_1") (pintype "passive"))
      (node (ref "FPC1") (pin "1") (pinfunction "VCC_1") (pintype "passive"))
      (node (ref "FPC1") (pin "2") (pinfunction "VCC_2") (pintype "passive"))
      (node (ref "FPC1") (pin "3") (pinfunction "VCC_3") (pintype "passive"))
      (node (ref "L2") (pin "2") (pinfunction "2_2") (pintype "passive"))
      (node (ref "R27") (pin "2") (pinfunction "2_2") (pintype "passive"))
      (node (ref "SW2") (pin "1") (pinfunction "1_1") (pintype "passive"))
    )
    (net (code "4") (name "+12V") (class "Default")
      (node (ref "C1") (pin "1") (pinfunction "1_1") (pintype "passive"))
      (node (ref "C10") (pin "1") (pinfunction "1_1") (pintype "passive"))
      (node (ref "C11") (pin "1") (pinfunction "1_1") (pintype "passive"))
      (node (ref "C15") (pin "1") (pinfunction "1_1") (pintype "passive"))
      (node (ref "C16") (pin "1") (pinfunction "1_1") (pintype "passive"))
      (node (ref "C17") (pin "1") (pinfunction "1_1") (pintype "passive"))
      (node (ref "C2") (pin "1") (pinfunction "1_1") (pintype "passive"))
      (node (ref "C3") (pin "1") (pinfunction "1_1") (pintype "passive"))
      (node (ref "C35") (pin "1") (pinfunction "1_1") (pintype "passive"))
      (node (ref "C36") (pin "1") (pinfunction "1_1") (pintype "passive"))
      (node (ref "C37") (pin "1") (pinfunction "1_1") (pintype "passive"))
      (node (ref "C9") (pin "1") (pinfunction "1_1") (pintype "passive"))
      (node (ref "D2") (pin "2") (pinfunction "2_2") (pintype "passive"))
      (node (ref "F1") (pin "2") (pintype "passive"))
      (node (ref "R33") (pin "1") (pinfunction "1_1") (pintype "passive"))
      (node (ref "R8") (pin "1") (pinfunction "1_1") (pintype "passive"))
      (node (ref "U1") (pin "2") (pinfunction "VIN_2") (pintype "passive"))
      (node (ref "U4") (pin "2") (pinfunction "VIN_2") (pintype "passive"))
      (node (ref "U5") (pin "1") (pinfunction "VIN_1") (pintype "passive"))
    )
    (net (code "6") (name "/AD_RST") (class "Default")
      (node (ref "IC1") (pin "7") (pinfunction "RESET_7") (pintype "passive"))
      (node (ref "U2") (pin "8") (pinfunction "/ADC1_10/PC0_8") (pintype "passive"))
    )
    (net (code "7") (name "/BOOT0") (class "Default")
      (node (ref "JP1") (pin "2") (pinfunction "2_2") (pintype "passive"))
      (node (ref "R45") (pin "1") (pinfunction "1_1") (pintype "passive"))
      (node (ref "U2") (pin "60") (pinfunction "BOOT0_60") (pintype "passive"))
    )
    (net (code "8") (name "/BOOT1") (class "Default")
      (node (ref "R55") (pin "1") (pinfunction "1_1") (pintype "passive"))
      (node (ref "U2") (pin "28") (pinfunction "PB2/BOOT1_28") (pintype "passive"))
    )
    (net (code "9") (name "/CLK") (class "Default")
      (node (ref "JP2") (pin "3") (pinfunction "3_3") (pintype "passive"))
      (node (ref "U2") (pin "49") (pinfunction "PA14/JTCK-SWCLK_49") (pintype "passive"))
    )
    (net (code "10") (name "/Current") (class "Default")
      (node (ref "C43") (pin "1") (pinfunction "1_1") (pintype "passive"))
      (node (ref "R68") (pin "1") (pinfunction "1_1") (pintype "passive"))
      (node (ref "U2") (pin "21") (pinfunction "PA5/TIM2_CH1/SPI1_SCK/ADC1_5_21") (pintype "passive"))
    )
    (net (code "11") (name "/D+") (class "Default")
      (node (ref "J1") (pin "3") (pinfunction "D+_3") (pintype "passive"))
      (node (ref "U8") (pin "4") (pinfunction "D+_4") (pintype "passive"))
    )
    (net (code "12") (name "/D-") (class "Default")
      (node (ref "J1") (pin "2") (pinfunction "D-_2") (pintype "passive"))
      (node (ref "U8") (pin "5") (pinfunction "D-_5") (pintype "passive"))
    )
    (net (code "13") (name "/DIO") (class "Default")
      (node (ref "JP2") (pin "2") (pinfunction "2_2") (pintype "passive"))
      (node (ref "U2") (pin "46") (pinfunction "PA13/JTMS-SWDIO/_46") (pintype "passive"))
    )
    (net (code "14") (name "/FLAG1") (class "Default")
      (node (ref "LED36") (pin "2") (pinfunction "CATHODE_2") (pintype "passive"))
      (node (ref "OSW6") (pin "7") (pinfunction "B_7") (pintype "passive"))
      (node (ref "R4") (pin "2") (pinfunction "2_2") (pintype "passive"))
      (node (ref "U3") (pin "3") (pinfunction "IO00_3") (pintype "passive"))
    )
    (net (code "15") (name "/FLAG2") (class "Default")
      (node (ref "LED32") (pin "2") (pinfunction "CATHODE_2") (pintype "passive"))
      (node (ref "OSW6") (pin "9") (pinfunction "A_9") (pintype "passive"))
      (node (ref "R6") (pin "2") (pinfunction "2_2") (pintype "passive"))
      (node (ref "U3") (pin "4") (pinfunction "IO01_4") (pintype "passive"))
    )
    (net (code "16") (name "/FLAG3") (class "Default")
      (node (ref "LED30") (pin "2") (pinfunction "CATHODE_2") (pintype "passive"))
      (node (ref "OSW6") (pin "2") (pinfunction "A_2") (pintype "passive"))
      (node (ref "R9") (pin "2") (pinfunction "2_2") (pintype "passive"))
      (node (ref "U3") (pin "5") (pinfunction "IO02_5") (pintype "passive"))
    )
    (net (code "17") (name "/FLAG4") (class "Default")
      (node (ref "LED34") (pin "2") (pinfunction "CATHODE_2") (pintype "passive"))
      (node (ref "OSW6") (pin "4") (pinfunction "B_4") (pintype "passive"))
      (node (ref "R12") (pin "2") (pinfunction "2_2") (pintype "passive"))
      (node (ref "U3") (pin "7") (pinfunction "IO03_7") (pintype "passive"))
    )
    (net (code "18") (name "/FLAG5") (class "Default")
      (node (ref "LED10") (pin "2") (pinfunction "CATHODE_2") (pintype "passive"))
      (node (ref "OSW3") (pin "A2") (pinfunction "A_A2") (pintype "passive"))
      (node (ref "R18") (pin "2") (pinfunction "2_2") (pintype "passive"))
      (node (ref "U3") (pin "8") (pinfunction "IO04_8") (pintype "passive"))
    )
    (net (code "19") (name "/FLAG6") (class "Default")
      (node (ref "R20") (pin "2") (pinfunction "2_2") (pintype "passive"))
    )
    (net (code "20") (name "/FLAG7") (class "Default")
      (node (ref "LED20") (pin "2") (pinfunction "CATHODE_2") (pintype "passive"))
      (node (ref "OSW4") (pin "8") (pinfunction "B_8") (pintype "passive"))
      (node (ref "R22") (pin "2") (pinfunction "2_2") (pintype "passive"))
      (node (ref "U3") (pin "10") (pinfunction "IO06_10") (pintype "passive"))
    )
    (net (code "21") (name "/FLAG8") (class "Default")
      (node (ref "LED19") (pin "2") (pinfunction "CATHODE_2") (pintype "passive"))
      (node (ref "OSW4") (pin "5") (pinfunction "B_5") (pintype "passive"))
      (node (ref "R24") (pin "2") (pinfunction "2_2") (pintype "passive"))
      (node (ref "U3") (pin "12") (pinfunction "IO07_12") (pintype "passive"))
    )
    (net (code "22") (name "/FLAG10") (class "Default")
      (node (ref "LED9") (pin "2") (pinfunction "CATHODE_2") (pintype "passive"))
      (node (ref "OSW3") (pin "A9") (pinfunction "A_A9") (pintype "passive"))
      (node (ref "R31") (pin "2") (pinfunction "2_2") (pintype "passive"))
      (node (ref "U3") (pin "14") (pinfunction "IO11_14") (pintype "passive"))
    )
    (net (code "23") (name "/FLAG11") (class "Default")
      (node (ref "LED28") (pin "2") (pinfunction "CATHODE_2") (pintype "passive"))
      (node (ref "OSW5") (pin "A4") (pinfunction "B_A4") (pintype "passive"))
      (node (ref "R35") (pin "2") (pinfunction "2_2") (pintype "passive"))
      (node (ref "U3") (pin "15") (pinfunction "IO12_15") (pintype "passive"))
    )
    (net (code "24") (name "/FLAG12") (class "Default")
      (node (ref "LED27") (pin "2") (pinfunction "CATHODE_2") (pintype "passive"))
      (node (ref "OSW5") (pin "A7") (pinfunction "B_A7") (pintype "passive"))
      (node (ref "R38") (pin "2") (pinfunction "2_2") (pintype "passive"))
      (node (ref "U3") (pin "16") (pinfunction "IO13_16") (pintype "passive"))
    )
    (net (code "25") (name "/FLAG13") (class "Default")
      (node (ref "LED3") (pin "2") (pinfunction "CATHODE_2") (pintype "passive"))
      (node (ref "OSW1") (pin "7") (pinfunction "B_7") (pintype "passive"))
      (node (ref "R41") (pin "2") (pinfunction "2_2") (pintype "passive"))
      (node (ref "U3") (pin "17") (pinfunction "IO14_17") (pintype "passive"))
    )
    (net (code "26") (name "/FLAG14") (class "Default")
      (node (ref "LED4") (pin "2") (pinfunction "CATHODE_2") (pintype "passive"))
      (node (ref "OSW1") (pin "2") (pinfunction "B_2") (pintype "passive"))
      (node (ref "R43") (pin "2") (pinfunction "2_2") (pintype "passive"))
      (node (ref "U3") (pin "19") (pinfunction "IO15_19") (pintype "passive"))
    )
    (net (code "27") (name "/FLAG15") (class "Default")
      (node (ref "LED2") (pin "2") (pinfunction "CATHODE_2") (pintype "passive"))
      (node (ref "OSW1") (pin "4") (pinfunction "A_4") (pintype "passive"))
      (node (ref "R46") (pin "2") (pinfunction "2_2") (pintype "passive"))
      (node (ref "U3") (pin "20") (pinfunction "IO16_20") (pintype "passive"))
    )
    (net (code "28") (name "/FLAG16") (class "Default")
      (node (ref "LED1") (pin "2") (pinfunction "CATHODE_2") (pintype "passive"))
      (node (ref "OSW1") (pin "5") (pinfunction "A_5") (pintype "passive"))
      (node (ref "R49") (pin "2") (pinfunction "2_2") (pintype "passive"))
      (node (ref "U3") (pin "21") (pinfunction "IO17_21") (pintype "passive"))
    )
    (net (code "29") (name "/FLAG17") (class "Default")
      (node (ref "LED39") (pin "2") (pinfunction "CATHODE_2") (pintype "passive"))
      (node (ref "OSW5") (pin "B7") (pinfunction "B_B7") (pintype "passive"))
      (node (ref "R51") (pin "2") (pinfunction "2_2") (pintype "passive"))
      (node (ref "U3") (pin "36") (pinfunction "IO30_36") (pintype "passive"))
    )
    (net (code "30") (name "/FLAG18") (class "Default")
      (node (ref "LED40") (pin "2") (pinfunction "CATHODE_2") (pintype "passive"))
      (node (ref "OSW5") (pin "B4") (pinfunction "B_B4") (pintype "passive"))
      (node (ref "R53") (pin "2") (pinfunction "2_2") (pintype "passive"))
      (node (ref "U3") (pin "37") (pinfunction "IO31_37") (pintype "passive"))
    )
    (net (code "31") (name "/FLAG19") (class "Default")
      (node (ref "LED38") (pin "2") (pinfunction "CATHODE_2") (pintype "passive"))
      (node (ref "OSW5") (pin "B2") (pinfunction "A_B2") (pintype "passive"))
      (node (ref "R56") (pin "2") (pinfunction "2_2") (pintype "passive"))
      (node (ref "U3") (pin "38") (pinfunction "IO32_38") (pintype "passive"))
    )
    (net (code "32") (name "/FLAG20") (class "Default")
      (node (ref "LED37") (pin "2") (pinfunction "CATHODE_2") (pintype "passive"))
      (node (ref "OSW5") (pin "B9") (pinfunction "A_B9") (pintype "passive"))
      (node (ref "R58") (pin "2") (pinfunction "2_2") (pintype "passive"))
      (node (ref "U3") (pin "40") (pinfunction "IO33_40") (pintype "passive"))
    )
    (net (code "33") (name "/FLAG21") (class "Default")
      (node (ref "LED26") (pin "2") (pinfunction "CATHODE_2") (pintype "passive"))
      (node (ref "OSW5") (pin "A2") (pinfunction "A_A2") (pintype "passive"))
      (node (ref "R59") (pin "1") (pinfunction "1_1") (pintype "passive"))
      (node (ref "U3") (pin "41") (pinfunction "IO34_41") (pintype "passive"))
    )
    (net (code "34") (name "/FLAG22") (class "Default")
      (node (ref "LED25") (pin "2") (pinfunction "CATHODE_2") (pintype "passive"))
      (node (ref "OSW5") (pin "A9") (pinfunction "A_A9") (pintype "passive"))
      (node (ref "R57") (pin "1") (pinfunction "1_1") (pintype "passive"))
      (node (ref "U3") (pin "42") (pinfunction "IO35_42") (pintype "passive"))
    )
    (net (code "35") (name "/FLAG23") (class "Default")
      (node (ref "LED11") (pin "2") (pinfunction "CATHODE_2") (pintype "passive"))
      (node (ref "OSW3") (pin "A7") (pinfunction "B_A7") (pintype "passive"))
      (node (ref "R54") (pin "1") (pinfunction "1_1") (pintype "passive"))
      (node (ref "U3") (pin "43") (pinfunction "IO36_43") (pintype "passive"))
    )
    (net (code "36") (name "/FLAG24") (class "Default")
      (node (ref "LED29") (pin "2") (pinfunction "CATHODE_2") (pintype "passive"))
      (node (ref "OSW3") (pin "C9") (pinfunction "A_C9") (pintype "passive"))
      (node (ref "R52") (pin "1") (pinfunction "1_1") (pintype "passive"))
      (node (ref "U3") (pin "44") (pinfunction "IO37_44") (pintype "passive"))
    )
    (net (code "37") (name "/FLAG25") (class "Default")
      (node (ref "LED14") (pin "2") (pinfunction "CATHODE_2") (pintype "passive"))
      (node (ref "OSW1") (pin "24") (pinfunction "A_24") (pintype "passive"))
      (node (ref "R50") (pin "1") (pinfunction "1_1") (pintype "passive"))
      (node (ref "U3") (pin "22") (pinfunction "IO20_22") (pintype "passive"))
    )
    (net (code "38") (name "/FLAG26") (class "Default")
      (node (ref "LED13") (pin "2") (pinfunction "CATHODE_2") (pintype "passive"))
      (node (ref "OSW1") (pin "25") (pinfunction "A_25") (pintype "passive"))
      (node (ref "R47") (pin "1") (pinfunction "1_1") (pintype "passive"))
      (node (ref "U3") (pin "24") (pinfunction "IO21_24") (pintype "passive"))
    )
    (net (code "39") (name "/FLAG27") (class "Default")
      (node (ref "LED15") (pin "2") (pinfunction "CATHODE_2") (pintype "passive"))
      (node (ref "OSW1") (pin "27") (pinfunction "B_27") (pintype "passive"))
      (node (ref "R44") (pin "1") (pinfunction "1_1") (pintype "passive"))
      (node (ref "U3") (pin "25") (pinfunction "IO22_25") (pintype "passive"))
    )
    (net (code "40") (name "/FLAG28") (class "Default")
      (node (ref "LED16") (pin "2") (pinfunction "CATHODE_2") (pintype "passive"))
      (node (ref "OSW1") (pin "22") (pinfunction "B_22") (pintype "passive"))
      (node (ref "R42") (pin "1") (pinfunction "1_1") (pintype "passive"))
      (node (ref "U3") (pin "26") (pinfunction "IO23_26") (pintype "passive"))
    )
    (net (code "41") (name "/FLAG29") (class "Default")
      (node (ref "LED6") (pin "2") (pinfunction "CATHODE_2") (pintype "passive"))
      (node (ref "OSW2") (pin "5") (pinfunction "A_5") (pintype "passive"))
      (node (ref "R39") (pin "1") (pinfunction "1_1") (pintype "passive"))
      (node (ref "U3") (pin "31") (pinfunction "IO24_31") (pintype "passive"))
    )
    (net (code "42") (name "/FLAG30") (class "Default")
      (node (ref "LED8") (pin "2") (pinfunction "CATHODE_2") (pintype "passive"))
      (node (ref "OSW2") (pin "7") (pinfunction "B_7") (pintype "passive"))
      (node (ref "R36") (pin "1") (pinfunction "1_1") (pintype "passive"))
      (node (ref "U3") (pin "32") (pinfunction "IO25_32") (pintype "passive"))
    )
    (net (code "43") (name "/FLAG31") (class "Default")
      (node (ref "LED7") (pin "2") (pinfunction "CATHODE_2") (pintype "passive"))
      (node (ref "OSW2") (pin "2") (pinfunction "B_2") (pintype "passive"))
      (node (ref "R32") (pin "1") (pinfunction "1_1") (pintype "passive"))
      (node (ref "U3") (pin "33") (pinfunction "IO26_33") (pintype "passive"))
    )
    (net (code "44") (name "/FLAG32") (class "Default")
      (node (ref "LED5") (pin "2") (pinfunction "CATHODE_2") (pintype "passive"))
      (node (ref "OSW2") (pin "4") (pinfunction "A_4") (pintype "passive"))
      (node (ref "R29") (pin "1") (pinfunction "1_1") (pintype "passive"))
      (node (ref "U3") (pin "35") (pinfunction "IO27_35") (pintype "passive"))
    )
    (net (code "45") (name "/FLAG33") (class "Default")
      (node (ref "LED31") (pin "2") (pinfunction "CATHODE_2") (pintype "passive"))
      (node (ref "OSW3") (pin "C2") (pinfunction "A_C2") (pintype "passive"))
      (node (ref "R25") (pin "1") (pinfunction "1_1") (pintype "passive"))
      (node (ref "U3") (pin "45") (pinfunction "IO40_45") (pintype "passive"))
    )
    (net (code "46") (name "/FLAG34") (class "Default")
      (node (ref "LED35") (pin "2") (pinfunction "CATHODE_2") (pintype "passive"))
      (node (ref "OSW3") (pin "C4") (pinfunction "B_C4") (pintype "passive"))
      (node (ref "R23") (pin "1") (pinfunction "1_1") (pintype "passive"))
      (node (ref "U3") (pin "47") (pinfunction "IO41_47") (pintype "passive"))
    )
    (net (code "47") (name "/FLAG35") (class "Default")
      (node (ref "LED33") (pin "2") (pinfunction "CATHODE_2") (pintype "passive"))
      (node (ref "OSW3") (pin "C7") (pinfunction "B_C7") (pintype "passive"))
      (node (ref "R21") (pin "1") (pinfunction "1_1") (pintype "passive"))
      (node (ref "U3") (pin "48") (pinfunction "IO42_48") (pintype "passive"))
    )
    (net (code "48") (name "/FLAG36") (class "Default")
      (node (ref "LED24") (pin "2") (pinfunction "CATHODE_2") (pintype "passive"))
      (node (ref "OSW3") (pin "B4") (pinfunction "B_B4") (pintype "passive"))
      (node (ref "R19") (pin "1") (pinfunction "1_1") (pintype "passive"))
      (node (ref "U3") (pin "49") (pinfunction "IO43_49") (pintype "passive"))
    )
    (net (code "49") (name "/FLAG37") (class "Default")
      (node (ref "LED22") (pin "2") (pinfunction "CATHODE_2") (pintype "passive"))
      (node (ref "OSW3") (pin "B2") (pinfunction "A_B2") (pintype "passive"))
      (node (ref "R13") (pin "1") (pinfunction "1_1") (pintype "passive"))
      (node (ref "U3") (pin "50") (pinfunction "IO44_50") (pintype "passive"))
    )
    (net (code "50") (name "/FLAG38") (class "Default")
      (node (ref "LED21") (pin "2") (pinfunction "CATHODE_2") (pintype "passive"))
      (node (ref "OSW3") (pin "B9") (pinfunction "A_B9") (pintype "passive"))
      (node (ref "R10") (pin "1") (pinfunction "1_1") (pintype "passive"))
      (node (ref "U3") (pin "52") (pinfunction "IO45_52") (pintype "passive"))
    )
    (net (code "51") (name "/FLAG39") (class "Default")
      (node (ref "LED23") (pin "2") (pinfunction "CATHODE_2") (pintype "passive"))
      (node (ref "OSW3") (pin "B7") (pinfunction "B_B7") (pintype "passive"))
      (node (ref "R7") (pin "1") (pinfunction "1_1") (pintype "passive"))
      (node (ref "U3") (pin "53") (pinfunction "IO46_53") (pintype "passive"))
    )
    (net (code "52") (name "/FLAG40") (class "Default")
      (node (ref "LED12") (pin "2") (pinfunction "CATHODE_2") (pintype "passive"))
      (node (ref "OSW3") (pin "A4") (pinfunction "B_A4") (pintype "passive"))
      (node (ref "R5") (pin "1") (pinfunction "1_1") (pintype "passive"))
      (node (ref "U3") (pin "54") (pinfunction "IO47_54") (pintype "passive"))
    )
    (net (code "53") (name "/IIC_SCL") (class "Default")
      (node (ref "IC1") (pin "9") (pinfunction "SCL_9") (pintype "passive"))
      (node (ref "JP3") (pin "18") (pinfunction "18_18") (pintype "passive"))
      (node (ref "R30") (pin "2") (pinfunction "2_2") (pintype "passive"))
      (node (ref "U2") (pin "58") (pinfunction "USART1_TX/I2C1_SCL/TIM4_CH1/PB6_58") (pintype "passive"))
      (node (ref "U3") (pin "1") (pinfunction "SCL_1") (pintype "passive"))
    )
    (net (code "54") (name "/IIC_SDA") (class "Default")
      (node (ref "IC1") (pin "8") (pinfunction "SDA_8") (pintype "passive"))
      (node (ref "JP3") (pin "17") (pinfunction "17_17") (pintype "passive"))
      (node (ref "R34") (pin "2") (pinfunction "2_2") (pintype "passive"))
      (node (ref "U2") (pin "59") (pinfunction "USART1_RX/I2C1_SDA/TIM4_CH2/PB7_59") (pintype "passive"))
      (node (ref "U3") (pin "2") (pinfunction "SDA_2") (pintype "passive"))
    )
    (net (code "55") (name "/INT") (class "Default")
      (node (ref "R16") (pin "2") (pinfunction "2_2") (pintype "passive"))
      (node (ref "U2") (pin "62") (pinfunction "I2C2_SDA/I2C1_SDA/TIM11_CH1/TIM4_CH4/PB9_62") (pintype "passive"))
      (node (ref "U3") (pin "55") (pinfunction "~{INT}/~{SMBALERT}_55") (pintype "passive"))
    )
    (net (code "56") (name "/IO0_5") (class "Default")
      (node (ref "LED18") (pin "2") (pinfunction "CATHODE_2") (pintype "passive"))
      (node (ref "OSW4") (pin "10") (pinfunction "A_10") (pintype "passive"))
      (node (ref "U3") (pin "9") (pinfunction "IO05_9") (pintype "passive"))
    )
    (net (code "57") (name "/IO1_0") (class "Default")
      (node (ref "LED17") (pin "2") (pinfunction "CATHODE_2") (pintype "passive"))
      (node (ref "OSW4") (pin "3") (pinfunction "A_3") (pintype "passive"))
      (node (ref "R28") (pin "2") (pinfunction "2_2") (pintype "passive"))
      (node (ref "U3") (pin "13") (pinfunction "IO10_13") (pintype "passive"))
    )
    (net (code "58") (name "/KEY1") (class "Default")
      (node (ref "KEY2") (pin "1") (pinfunction "1_1") (pintype "passive"))
      (node (ref "U2") (pin "14") (pinfunction "PA0-WKUP/TIM2_CH1/TIM5_CH1/ADC1_0_14") (pintype "passive"))
    )
    (net (code "59") (name "/KEY2(URT2_TX)") (class "Default")
      (node (ref "FPC1") (pin "5") (pinfunction "RX2_5") (pintype "passive"))
      (node (ref "KEY3") (pin "1") (pinfunction "1_1") (pintype "passive"))
      (node (ref "U2") (pin "16") (pinfunction "PA2/TIM2_CH3/TIM5_CH3/TIM9_CH1/USART2_TX/ADC1_2_16") (pintype "passive"))
    )
    (net (code "60") (name "/KEY3") (class "Default")
      (node (ref "KEY4") (pin "1") (pinfunction "1_1") (pintype "passive"))
      (node (ref "U2") (pin "15") (pinfunction "PA1/TIM2_CH2/TIM5_CH2/SPI4_MOSI/EVENTOUT/ADC1_1_15") (pintype "passive"))
    )
    (net (code "61") (name "/KEY4(URT2_RX)") (class "Default")
      (node (ref "FPC1") (pin "6") (pinfunction "TX2_6") (pintype "passive"))
      (node (ref "KEY5") (pin "1") (pinfunction "1_1") (pintype "passive"))
      (node (ref "U2") (pin "17") (pinfunction "PA3/TIM2_CH4/TIM5_CH4/TIM9_CH2/USART2_RX/ADC1_3_17") (pintype "passive"))
    )
    (net (code "62") (name "/OE") (class "Default")
      (node (ref "R17") (pin "2") (pinfunction "2_2") (pintype "passive"))
      (node (ref "U2") (pin "57") (pinfunction "SPI3_MOSI/SPI1_MOSI/TIM3_CH2/PB5_57") (pintype "passive"))
      (node (ref "U3") (pin "30") (pinfunction "~{OE}_30") (pintype "passive"))
    )
    (net (code "63") (name "/ON{slash}OFF") (class "Default")
      (node (ref "R67") (pin "2") (pinfunction "2_2") (pintype "passive"))
      (node (ref "U2") (pin "2") (pinfunction "/ANTI_TAMP/RTC_AMP1/RTC_OUT/RTC_TS/PC13_2") (pintype "passive"))
      (node (ref "U5") (pin "5") (pinfunction "~{ON}_5") (pintype "passive"))
    )
    (net (code "64") (name "/PA6_CTR9") (class "Default")
      (node (ref "R79") (pin "2") (pinfunction "2_2") (pintype "passive"))
      (node (ref "U2") (pin "22") (pinfunction "PA6/TIM3_CH1/SPI1_MISO/ADC1_6_22") (pintype "passive"))
    )
    (net (code "65") (name "/PA7_CTR10") (class "Default")
      (node (ref "R104") (pin "2") (pinfunction "2_2") (pintype "passive"))
      (node (ref "U2") (pin "23") (pinfunction "PA7/TIM3_CH2/SPI1_MOSI/ADC1_7_23") (pintype "passive"))
    )
    (net (code "66") (name "/PA8_CTR5") (class "Default")
      (node (ref "JP3") (pin "12") (pinfunction "12_12") (pintype "passive"))
      (node (ref "R94") (pin "2") (pinfunction "2_2") (pintype "passive"))
      (node (ref "U2") (pin "41") (pinfunction "PA8/TIM1_CH1/I2C3_SCL_41") (pintype "passive"))
    )
    (net (code "67") (name "/PA11_CTR6") (class "Default")
      (node (ref "JP3") (pin "11") (pinfunction "11_11") (pintype "passive"))
      (node (ref "R95") (pin "2") (pinfunction "2_2") (pintype "passive"))
      (node (ref "U2") (pin "44") (pinfunction "PA11/TIM1_CH4/SPI4_MISO/USART6_TX_44") (pintype "passive"))
    )
    (net (code "68") (name "/PA12_CTR3") (class "Default")
      (node (ref "JP3") (pin "14") (pinfunction "14_14") (pintype "passive"))
      (node (ref "R82") (pin "2") (pinfunction "2_2") (pintype "passive"))
      (node (ref "U2") (pin "45") (pinfunction "PA12/SPI5_MISO/USART6_RX/_45") (pintype "passive"))
    )
    (net (code "69") (name "/PA15_CTR4") (class "Default")
      (node (ref "R83") (pin "2") (pinfunction "2_2") (pintype "passive"))
      (node (ref "U2") (pin "50") (pinfunction "PA15/JTDI/TIM2_CH1/USART1_TX_50") (pintype "passive"))
    )
    (net (code "70") (name "/PB0_MA") (class "Default")
      (node (ref "U12") (pin "6") (pinfunction "IA_6") (pintype "passive"))
      (node (ref "U2") (pin "26") (pinfunction "PB0/TIM3_CH3/SPI5_SCK_26") (pintype "passive"))
    )
    (net (code "71") (name "/PB1_MB") (class "Default")
      (node (ref "U10") (pin "7") (pinfunction "IB_7") (pintype "passive"))
      (node (ref "U2") (pin "27") (pinfunction "PB1/TIM3_CH4/ADC1_9_27") (pintype "passive"))
    )
    (net (code "72") (name "/PB3_MB") (class "Default")
      (node (ref "U2") (pin "55") (pinfunction "JTDO-SWO/TIM2_CH2/SPI1_SCK/SPI3_SCK/USART1_RX/I2C2_SDA/_PB3_55") (pintype "passive"))
      (node (ref "U9") (pin "7") (pinfunction "IB_7") (pintype "passive"))
    )
    (net (code "73") (name "/PB4_MA") (class "Default")
      (node (ref "U2") (pin "56") (pinfunction "JTRST/TIM3_CH1/SPI1_MISO/SPI3_MISO/I2C3_SDA/PB4_56") (pintype "passive"))
      (node (ref "U9") (pin "6") (pinfunction "IA_6") (pintype "passive"))
    )
    (net (code "74") (name "/PB10_MA") (class "Default")
      (node (ref "U10") (pin "6") (pinfunction "IA_6") (pintype "passive"))
      (node (ref "U2") (pin "29") (pinfunction "/I2C2_SCL/TIM2_CH3/SPI2_SCK/PB10_29") (pintype "passive"))
    )
    (net (code "75") (name "/PB12_MB") (class "Default")
      (node (ref "JP3") (pin "6") (pinfunction "6_6") (pintype "passive"))
      (node (ref "U2") (pin "33") (pinfunction "/SPI3_SCK/PB12_33") (pintype "passive"))
      (node (ref "U7") (pin "7") (pinfunction "IB_7") (pintype "passive"))
    )
    (net (code "76") (name "/PB13_MA") (class "Default")
      (node (ref "JP3") (pin "5") (pinfunction "5_5") (pintype "passive"))
      (node (ref "U2") (pin "34") (pinfunction "/SPI2_SCK/SPI4_SCK/PB13_34") (pintype "passive"))
      (node (ref "U7") (pin "6") (pinfunction "IA_6") (pintype "passive"))
    )
    (net (code "77") (name "/PB14_MB") (class "Default")
      (node (ref "JP3") (pin "8") (pinfunction "8_8") (pintype "passive"))
      (node (ref "U14") (pin "7") (pinfunction "IB_7") (pintype "passive"))
      (node (ref "U2") (pin "35") (pinfunction "/SPI2_MISO/PB14_35") (pintype "passive"))
    )
    (net (code "78") (name "/PB15_MA") (class "Default")
      (node (ref "JP3") (pin "7") (pinfunction "7_7") (pintype "passive"))
      (node (ref "U14") (pin "6") (pinfunction "IA_6") (pintype "passive"))
      (node (ref "U2") (pin "36") (pinfunction "/RTC_50Hz/SPI2_MOSI/PB15_36") (pintype "passive"))
    )
    (net (code "79") (name "/PC1") (class "Default")
      (node (ref "JP3") (pin "13") (pinfunction "13_13") (pintype "passive"))
      (node (ref "U2") (pin "9") (pinfunction "/ADC1_19/PC1_9") (pintype "passive"))
    )
    (net (code "80") (name "/PC2") (class "Default")
      (node (ref "JP3") (pin "15") (pinfunction "15_15") (pintype "passive"))
      (node (ref "U2") (pin "10") (pinfunction "/SPI2_MISO/ADC1_12/PC2_10") (pintype "passive"))
    )
    (net (code "81") (name "/PC3") (class "Default")
      (node (ref "JP3") (pin "16") (pinfunction "16_16") (pintype "passive"))
      (node (ref "U2") (pin "11") (pinfunction "/SPI2_MOSI/ADC1_13/PC3_11") (pintype "passive"))
    )
    (net (code "82") (name "/PC4_CTR11") (class "Default")
      (node (ref "R119") (pin "2") (pinfunction "2_2") (pintype "passive"))
      (node (ref "U2") (pin "24") (pinfunction "/ADC1_14/PC4_24") (pintype "passive"))
    )
    (net (code "83") (name "/PC5_MB") (class "Default")
      (node (ref "U12") (pin "7") (pinfunction "IB_7") (pintype "passive"))
      (node (ref "U2") (pin "25") (pinfunction "/ADC1_15/PC5_25") (pintype "passive"))
    )
    (net (code "84") (name "/PC6_MB") (class "Default")
      (node (ref "U11") (pin "7") (pinfunction "IB_7") (pintype "passive"))
      (node (ref "U2") (pin "37") (pinfunction "TIM3_CH1/USART6_TX/PC6_37") (pintype "passive"))
    )
    (net (code "85") (name "/PC7_MA") (class "Default")
      (node (ref "U11") (pin "6") (pinfunction "IA_6") (pintype "passive"))
      (node (ref "U2") (pin "38") (pinfunction "TIM3_CH2/SPI2_SCK/USART6_RX/PC7_38") (pintype "passive"))
    )
    (net (code "86") (name "/PC8_CTR7") (class "Default")
      (node (ref "JP3") (pin "10") (pinfunction "10_10") (pintype "passive"))
      (node (ref "R111") (pin "2") (pinfunction "2_2") (pintype "passive"))
      (node (ref "U2") (pin "39") (pinfunction "TIM3_CH3/PC8_39") (pintype "passive"))
    )
    (net (code "87") (name "/PC9_CTR8") (class "Default")
      (node (ref "JP3") (pin "9") (pinfunction "9_9") (pintype "passive"))
      (node (ref "R129") (pin "2") (pinfunction "2_2") (pintype "passive"))
      (node (ref "U2") (pin "40") (pinfunction "TIM3_CH4/I2C3_SDA/PC9_40") (pintype "passive"))
    )
    (net (code "88") (name "/PC10_CTR2") (class "Default")
      (node (ref "R118") (pin "2") (pinfunction "2_2") (pintype "passive"))
      (node (ref "U2") (pin "51") (pinfunction "SPI3_SCK/_PC10_51") (pintype "passive"))
    )
    (net (code "89") (name "/PC11_MB") (class "Default")
      (node (ref "U13") (pin "7") (pinfunction "IB_7") (pintype "passive"))
      (node (ref "U2") (pin "52") (pinfunction "SPI3_MISO/PC11_52") (pintype "passive"))
    )
    (net (code "90") (name "/PC12_MA") (class "Default")
      (node (ref "U13") (pin "6") (pinfunction "IA_6") (pintype "passive"))
      (node (ref "U2") (pin "53") (pinfunction "SPI3_MOSI/PC12_53") (pintype "passive"))
    )
    (net (code "91") (name "/PD2_CTR1") (class "Default")
      (node (ref "R87") (pin "2") (pinfunction "2_2") (pintype "passive"))
      (node (ref "U2") (pin "54") (pinfunction "PD2_54") (pintype "passive"))
    )
    (net (code "92") (name "/RESET") (class "Default")
      (node (ref "C25") (pin "2") (pinfunction "2_2") (pintype "passive"))
      (node (ref "KEY1") (pin "1") (pinfunction "1_1") (pintype "passive"))
      (node (ref "R48") (pin "1") (pinfunction "1_1") (pintype "passive"))
      (node (ref "U2") (pin "7") (pinfunction "NRST_7") (pintype "passive"))
    )
    (net (code "93") (name "/RST") (class "Default")
      (node (ref "R15") (pin "2") (pinfunction "2_2") (pintype "passive"))
      (node (ref "U2") (pin "61") (pinfunction "I2C3_SDA/SPI5_MOSI/I2C1_SCL/TIM10_CH1/TIM4_CH3/PB8_61") (pintype "passive"))
      (node (ref "U3") (pin "56") (pinfunction "~{RST}_56") (pintype "passive"))
    )
    (net (code "94") (name "/RXD0") (class "Default")
      (node (ref "R97") (pin "2") (pinfunction "2_2") (pintype "passive"))
      (node (ref "U8") (pin "25") (pinfunction "RXD_25") (pintype "passive"))
    )
    (net (code "95") (name "/TXD0") (class "Default")
      (node (ref "R101") (pin "2") (pinfunction "2_2") (pintype "passive"))
      (node (ref "U8") (pin "26") (pinfunction "TXD_26") (pintype "passive"))
    )
    (net (code "96") (name "/USRAT1_RX") (class "Default")
      (node (ref "D6") (pin "-") (pinfunction "1_-") (pintype "passive"))
      (node (ref "U2") (pin "43") (pinfunction "PA10/TIM1_CH3/USART1_RX/SPI5_MOSI/_43") (pintype "passive"))
    )
    (net (code "97") (name "/USRAT1_TX") (class "Default")
      (node (ref "D5") (pin "+") (pinfunction "2_+") (pintype "passive"))
      (node (ref "U2") (pin "42") (pinfunction "PA9/TIM1_CH2/USART1_TX_42") (pintype "passive"))
    )
    (net (code "98") (name "/VBUS") (class "Default")
      (node (ref "C44") (pin "2") (pinfunction "2_2") (pintype "passive"))
      (node (ref "C45") (pin "2") (pinfunction "2_2") (pintype "passive"))
      (node (ref "J1") (pin "1") (pinfunction "VBUS_1") (pintype "passive"))
      (node (ref "U8") (pin "7") (pinfunction "REGIN_7") (pintype "passive"))
      (node (ref "U8") (pin "8") (pinfunction "VBUS_8") (pintype "passive"))
    )
    (net (code "99") (name "/VCAP_1") (class "Default")
      (node (ref "C26") (pin "2") (pinfunction "2_2") (pintype "passive"))
      (node (ref "U2") (pin "30") (pinfunction "VCAP_1_30") (pintype "passive"))
    )
    (net (code "100") (name "/VDD") (class "Default")
      (node (ref "C46") (pin "2") (pinfunction "2_2") (pintype "passive"))
      (node (ref "C47") (pin "2") (pinfunction "2_2") (pintype "passive"))
      (node (ref "U8") (pin "6") (pinfunction "VDD_6") (pintype "passive"))
    )
    (net (code "101") (name "/VREF+") (class "Default")
      (node (ref "C32") (pin "2") (pinfunction "2_2") (pintype "passive"))
      (node (ref "C33") (pin "1") (pinfunction "1_1") (pintype "passive"))
      (node (ref "R61") (pin "2") (pinfunction "2_2") (pintype "passive"))
      (node (ref "U2") (pin "13") (pinfunction "VREF+_13") (pintype "passive"))
    )
    (net (code "102") (name "/Voltage") (class "Default")
      (node (ref "C42") (pin "2") (pinfunction "2_2") (pintype "passive"))
      (node (ref "R64") (pin "1") (pinfunction "1_1") (pintype "passive"))
      (node (ref "R73") (pin "2") (pinfunction "2_2") (pintype "passive"))
      (node (ref "U2") (pin "20") (pinfunction "PA4/ADC1_4_20") (pintype "passive"))
    )
    (net (code "103") (name "DGND") (class "Default")
      (node (ref "C1") (pin "2") (pinfunction "2_2") (pintype "passive"))
      (node (ref "C12") (pin "2") (pinfunction "2_2") (pintype "passive"))
      (node (ref "C13") (pin "2") (pinfunction "2_2") (pintype "passive"))
      (node (ref "C14") (pin "2") (pinfunction "2_2") (pintype "passive"))
      (node (ref "C15") (pin "2") (pinfunction "2_2") (pintype "passive"))
      (node (ref "C16") (pin "2") (pinfunction "2_2") (pintype "passive"))
      (node (ref "C17") (pin "2") (pinfunction "2_2") (pintype "passive"))
      (node (ref "C19") (pin "2") (pinfunction "2_2") (pintype "passive"))
      (node (ref "C2") (pin "2") (pinfunction "2_2") (pintype "passive"))
      (node (ref "C20") (pin "2") (pinfunction "2_2") (pintype "passive"))
      (node (ref "C21") (pin "2") (pinfunction "2_2") (pintype "passive"))
      (node (ref "C22") (pin "2") (pinfunction "2_2") (pintype "passive"))
      (node (ref "C23") (pin "2") (pinfunction "2_2") (pintype "passive"))
      (node (ref "C24") (pin "2") (pinfunction "2_2") (pintype "passive"))
      (node (ref "C25") (pin "1") (pinfunction "1_1") (pintype "passive"))
      (node (ref "C26") (pin "1") (pinfunction "1_1") (pintype "passive"))
      (node (ref "C27") (pin "2") (pinfunction "2_2") (pintype "passive"))
      (node (ref "C28") (pin "2") (pinfunction "2_2") (pintype "passive"))
      (node (ref "C29") (pin "2") (pinfunction "2_2") (pintype "passive"))
      (node (ref "C3") (pin "2") (pinfunction "2_2") (pintype "passive"))
      (node (ref "C30") (pin "2") (pinfunction "2_2") (pintype "passive"))
      (node (ref "C31") (pin "2") (pinfunction "2_2") (pintype "passive"))
      (node (ref "C32") (pin "1") (pinfunction "1_1") (pintype "passive"))
      (node (ref "C33") (pin "2") (pinfunction "2_2") (pintype "passive"))
      (node (ref "C35") (pin "2") (pinfunction "2_2") (pintype "passive"))
      (node (ref "C36") (pin "2") (pinfunction "2_2") (pintype "passive"))
      (node (ref "C37") (pin "2") (pinfunction "2_2") (pintype "passive"))
      (node (ref "C38") (pin "2") (pinfunction "2_2") (pintype "passive"))
      (node (ref "C39") (pin "2") (pinfunction "2_2") (pintype "passive"))
      (node (ref "C40") (pin "2") (pinfunction "2_2") (pintype "passive"))
      (node (ref "C41") (pin "2") (pinfunction "2_2") (pintype "passive"))
      (node (ref "C42") (pin "1") (pinfunction "1_1") (pintype "passive"))
      (node (ref "C43") (pin "2") (pinfunction "2_2") (pintype "passive"))
      (node (ref "C44") (pin "1") (pinfunction "1_1") (pintype "passive"))
      (node (ref "C45") (pin "1") (pinfunction "1_1") (pintype "passive"))
      (node (ref "C46") (pin "1") (pinfunction "1_1") (pintype "passive"))
      (node (ref "C47") (pin "1") (pinfunction "1_1") (pintype "passive"))
      (node (ref "C5") (pin "2") (pinfunction "2_2") (pintype "passive"))
      (node (ref "C6") (pin "2") (pinfunction "2_2") (pintype "passive"))
      (node (ref "C7") (pin "2") (pinfunction "2_2") (pintype "passive"))
      (node (ref "C8") (pin "1") (pinfunction "1_1") (pintype "passive"))
      (node (ref "D1") (pin "+") (pinfunction "1_+") (pintype "passive"))
      (node (ref "D3") (pin "+") (pinfunction "1_+") (pintype "passive"))
      (node (ref "D4") (pin "+") (pinfunction "1_+") (pintype "passive"))
      (node (ref "FB1") (pin "2") (pinfunction "2_2") (pintype "passive"))
      (node (ref "FPC1") (pin "0") (pinfunction "GND_0") (pintype "passive"))
      (node (ref "FPC1") (pin "10") (pinfunction "GND_10") (pintype "passive"))
      (node (ref "FPC1") (pin "8") (pinfunction "GND_8") (pintype "passive"))
      (node (ref "FPC1") (pin "9") (pinfunction "GND_9") (pintype "passive"))
      (node (ref "IC1") (pin "6") (pinfunction "GND_6") (pintype "passive"))
      (node (ref "J1") (pin "4") (pinfunction "GND_4") (pintype "passive"))
      (node (ref "J1") (pin "5") (pinfunction "GND_5") (pintype "passive"))
      (node (ref "J1") (pin "6") (pinfunction "GND_6") (pintype "passive"))
      (node (ref "JP1") (pin "1") (pinfunction "1_1") (pintype "passive"))
      (node (ref "JP2") (pin "1") (pinfunction "1_1") (pintype "passive"))
      (node (ref "JP3") (pin "3") (pinfunction "3_3") (pintype "passive"))
      (node (ref "JP3") (pin "4") (pinfunction "4_4") (pintype "passive"))
      (node (ref "KEY1") (pin "2") (pinfunction "2_2") (pintype "passive"))
      (node (ref "KEY2") (pin "3") (pinfunction "3_3") (pintype "passive"))
      (node (ref "KEY3") (pin "3") (pinfunction "3_3") (pintype "passive"))
      (node (ref "KEY4") (pin "3") (pinfunction "3_3") (pintype "passive"))
      (node (ref "KEY5") (pin "3") (pinfunction "3_3") (pintype "passive"))
      (node (ref "OSW1") (pin "23") (pintype "passive"))
      (node (ref "OSW1") (pin "26") (pintype "passive"))
      (node (ref "OSW1") (pin "3") (pintype "passive"))
      (node (ref "OSW1") (pin "6") (pintype "passive"))
      (node (ref "OSW2") (pin "3") (pintype "passive"))
      (node (ref "OSW2") (pin "6") (pintype "passive"))
      (node (ref "OSW2") (pin "8") (pinfunction "B+_8") (pintype "passive"))
      (node (ref "OSW3") (pin "A3") (pintype "passive"))
      (node (ref "OSW3") (pin "A8") (pintype "passive"))
      (node (ref "OSW3") (pin "B3") (pintype "passive"))
      (node (ref "OSW3") (pin "B8") (pintype "passive"))
      (node (ref "OSW3") (pin "C3") (pintype "passive"))
      (node (ref "OSW3") (pin "C8") (pintype "passive"))
      (node (ref "OSW4") (pin "4") (pintype "passive"))
      (node (ref "OSW4") (pin "9") (pintype "passive"))
      (node (ref "OSW5") (pin "A3") (pintype "passive"))
      (node (ref "OSW5") (pin "A8") (pintype "passive"))
      (node (ref "OSW5") (pin "B3") (pintype "passive"))
      (node (ref "OSW5") (pin "B8") (pintype "passive"))
      (node (ref "OSW6") (pin "3") (pintype "passive"))
      (node (ref "OSW6") (pin "8") (pintype "passive"))
      (node (ref "Q1") (pin "5") (pinfunction "S1_5") (pintype "passive"))
      (node (ref "Q10") (pin "5") (pinfunction "S1_5") (pintype "passive"))
      (node (ref "Q11") (pin "e") (pintype "passive"))
      (node (ref "Q12") (pin "e") (pintype "passive"))
      (node (ref "Q13") (pin "5") (pinfunction "S1_5") (pintype "passive"))
      (node (ref "Q14") (pin "e") (pintype "passive"))
      (node (ref "Q15") (pin "5") (pinfunction "S1_5") (pintype "passive"))
      (node (ref "Q16") (pin "e") (pintype "passive"))
      (node (ref "Q17") (pin "5") (pinfunction "S1_5") (pintype "passive"))
      (node (ref "Q18") (pin "5") (pinfunction "S1_5") (pintype "passive"))
      (node (ref "Q19") (pin "e") (pintype "passive"))
      (node (ref "Q2") (pin "e") (pintype "passive"))
      (node (ref "Q20") (pin "e") (pintype "passive"))
      (node (ref "Q21") (pin "5") (pinfunction "S1_5") (pintype "passive"))
      (node (ref "Q22") (pin "e") (pintype "passive"))
      (node (ref "Q3") (pin "5") (pinfunction "S1_5") (pintype "passive"))
      (node (ref "Q4") (pin "5") (pinfunction "S1_5") (pintype "passive"))
      (node (ref "Q5") (pin "e") (pintype "passive"))
      (node (ref "Q6") (pin "e") (pintype "passive"))
      (node (ref "Q7") (pin "5") (pinfunction "S1_5") (pintype "passive"))
      (node (ref "Q8") (pin "e") (pintype "passive"))
      (node (ref "Q9") (pin "5") (pinfunction "S1_5") (pintype "passive"))
      (node (ref "R1") (pin "1") (pinfunction "1_1") (pintype "passive"))
      (node (ref "R14") (pin "2") (pinfunction "2_2") (pintype "passive"))
      (node (ref "R26") (pin "1") (pinfunction "1_1") (pintype "passive"))
      (node (ref "R40") (pin "2") (pinfunction "2_2") (pintype "passive"))
      (node (ref "R45") (pin "2") (pinfunction "2_2") (pintype "passive"))
      (node (ref "R55") (pin "2") (pinfunction "2_2") (pintype "passive"))
      (node (ref "R60") (pin "2") (pinfunction "2_2") (pintype "passive"))
      (node (ref "R67") (pin "1") (pinfunction "1_1") (pintype "passive"))
      (node (ref "R73") (pin "1") (pinfunction "1_1") (pintype "passive"))
      (node (ref "U1") (pin "7") (pinfunction "GND_7") (pintype "passive"))
      (node (ref "U10") (pin "5") (pinfunction "-_5") (pintype "passive"))
      (node (ref "U10") (pin "8") (pinfunction "-_8") (pintype "passive"))
      (node (ref "U11") (pin "5") (pinfunction "-_5") (pintype "passive"))
      (node (ref "U11") (pin "8") (pinfunction "-_8") (pintype "passive"))
      (node (ref "U12") (pin "5") (pinfunction "-_5") (pintype "passive"))
      (node (ref "U12") (pin "8") (pinfunction "-_8") (pintype "passive"))
      (node (ref "U13") (pin "5") (pinfunction "-_5") (pintype "passive"))
      (node (ref "U13") (pin "8") (pinfunction "-_8") (pintype "passive"))
      (node (ref "U14") (pin "5") (pinfunction "-_5") (pintype "passive"))
      (node (ref "U14") (pin "8") (pinfunction "-_8") (pintype "passive"))
      (node (ref "U2") (pin "12") (pinfunction "VSSA_12") (pintype "passive"))
      (node (ref "U2") (pin "18") (pinfunction "VSS_18") (pintype "passive"))
      (node (ref "U2") (pin "31") (pinfunction "VSS_31") (pintype "passive"))
      (node (ref "U2") (pin "47") (pinfunction "VSS_47") (pintype "passive"))
      (node (ref "U2") (pin "63") (pinfunction "VSS_63") (pintype "passive"))
      (node (ref "U3") (pin "11") (pinfunction "VSS_11") (pintype "passive"))
      (node (ref "U3") (pin "23") (pinfunction "VSS_23") (pintype "passive"))
      (node (ref "U3") (pin "27") (pinfunction "AD0_27") (pintype "passive"))
      (node (ref "U3") (pin "28") (pinfunction "AD1_28") (pintype "passive"))
      (node (ref "U3") (pin "29") (pinfunction "AD2_29") (pintype "passive"))
      (node (ref "U3") (pin "34") (pinfunction "VSS_34") (pintype "passive"))
      (node (ref "U3") (pin "39") (pinfunction "VSS_39") (pintype "passive"))
      (node (ref "U3") (pin "51") (pinfunction "VSS_51") (pintype "passive"))
      (node (ref "U3") (pin "6") (pinfunction "VSS_6") (pintype "passive"))
      (node (ref "U4") (pin "7") (pinfunction "GND_7") (pintype "passive"))
      (node (ref "U5") (pin "3") (pinfunction "GND_3") (pintype "passive"))
      (node (ref "U6") (pin "1") (pinfunction "GND_1") (pintype "passive"))
      (node (ref "U6") (pin "2") (pinfunction "GND_2") (pintype "passive"))
      (node (ref "U7") (pin "5") (pinfunction "-_5") (pintype "passive"))
      (node (ref "U7") (pin "8") (pinfunction "-_8") (pintype "passive"))
      (node (ref "U8") (pin "3") (pinfunction "GND_3") (pintype "passive"))
      (node (ref "U9") (pin "5") (pinfunction "-_5") (pintype "passive"))
      (node (ref "U9") (pin "8") (pinfunction "-_8") (pintype "passive"))
    )
    (net (code "104") (name "GND") (class "Default")
      (node (ref "C10") (pin "2") (pinfunction "2_2") (pintype "passive"))
      (node (ref "C11") (pin "2") (pinfunction "2_2") (pintype "passive"))
      (node (ref "C9") (pin "2") (pinfunction "2_2") (pintype "passive"))
      (node (ref "D2") (pin "1") (pinfunction "1_1") (pintype "passive"))
      (node (ref "DC1") (pin "2") (pinfunction "2_2") (pintype "passive"))
      (node (ref "DC1") (pin "3") (pinfunction "3_3") (pintype "passive"))
      (node (ref "FB1") (pin "1") (pinfunction "1_1") (pintype "passive"))
    )
    (net (code "105") (name "Net-(C14-Pad1)") (class "Default")
      (node (ref "C14") (pin "1") (pinfunction "1_1") (pintype "passive"))
      (node (ref "R11") (pin "2") (pinfunction "2_2") (pintype "passive"))
    )
    (net (code "106") (name "Net-(C24-Pad1)") (class "Default")
      (node (ref "C24") (pin "1") (pinfunction "1_1") (pintype "passive"))
      (node (ref "R37") (pin "2") (pinfunction "2_2") (pintype "passive"))
    )
    (net (code "107") (name "Net-(D1-2)") (class "Default")
      (node (ref "C4") (pin "1") (pinfunction "1_1") (pintype "passive"))
      (node (ref "D1") (pin "-") (pinfunction "2_-") (pintype "passive"))
      (node (ref "L1") (pin "1") (pinfunction "1_1") (pintype "passive"))
      (node (ref "U1") (pin "8") (pinfunction "PH_8") (pintype "passive"))
    )
    (net (code "108") (name "Net-(D3-2)") (class "Default")
      (node (ref "C18") (pin "1") (pinfunction "1_1") (pintype "passive"))
      (node (ref "D3") (pin "-") (pinfunction "2_-") (pintype "passive"))
      (node (ref "L2") (pin "1") (pinfunction "1_1") (pintype "passive"))
      (node (ref "U4") (pin "8") (pinfunction "PH_8") (pintype "passive"))
    )
    (net (code "109") (name "Net-(D4-2)") (class "Default")
      (node (ref "D4") (pin "-") (pinfunction "2_-") (pintype "passive"))
      (node (ref "L3") (pin "1") (pinfunction "1_1") (pintype "passive"))
      (node (ref "U5") (pin "2") (pinfunction "OUT_2") (pintype "passive"))
    )
    (net (code "110") (name "Net-(D5-1)") (class "Default")
      (node (ref "D5") (pin "-") (pinfunction "1_-") (pintype "passive"))
      (node (ref "R96") (pin "1") (pinfunction "1_1") (pintype "passive"))
      (node (ref "R97") (pin "1") (pinfunction "1_1") (pintype "passive"))
    )
    (net (code "111") (name "Net-(D6-2)") (class "Default")
      (node (ref "D6") (pin "+") (pinfunction "2_+") (pintype "passive"))
      (node (ref "R101") (pin "1") (pinfunction "1_1") (pintype "passive"))
      (node (ref "R105") (pin "2") (pinfunction "2_2") (pintype "passive"))
    )
    (net (code "112") (name "Net-(DC1-Pad1)") (class "Default")
      (node (ref "DC1") (pin "1") (pinfunction "1_1") (pintype "passive"))
      (node (ref "SW1") (pin "1") (pinfunction "1_1") (pintype "passive"))
    )
    (net (code "113") (name "Net-(F1-Pad1)") (class "Default")
      (node (ref "F1") (pin "1") (pintype "passive"))
      (node (ref "SW1") (pin "2") (pinfunction "2_2") (pintype "passive"))
    )
    (net (code "114") (name "Net-(IC1-A)") (class "Default")
      (node (ref "IC1") (pin "2") (pinfunction "A_2") (pintype "passive"))
      (node (ref "R60") (pin "1") (pinfunction "1_1") (pintype "passive"))
      (node (ref "R62") (pin "1") (pinfunction "1_1") (pintype "passive"))
      (node (ref "R62") (pin "2") (pinfunction "3_2") (pintype "passive"))
      (node (ref "U5") (pin "4") (pinfunction "FB_4") (pintype "passive"))
    )
    (net (code "115") (name "Net-(IC1-EXT)") (class "Default")
      (node (ref "C34") (pin "2") (pinfunction "2_2") (pintype "passive"))
      (node (ref "IC1") (pin "5") (pinfunction "EXT_5") (pintype "passive"))
    )
    (net (code "116") (name "Net-(IC1-VSS)") (class "Default")
      (node (ref "C34") (pin "1") (pinfunction "1_1") (pintype "passive"))
      (node (ref "IC1") (pin "4") (pinfunction "VSS_4") (pintype "passive"))
    )
    (net (code "117") (name "Net-(IC1-W)") (class "Default")
      (node (ref "C38") (pin "1") (pinfunction "1_1") (pintype "passive"))
      (node (ref "C39") (pin "1") (pinfunction "1_1") (pintype "passive"))
      (node (ref "C40") (pin "1") (pinfunction "1_1") (pintype "passive"))
      (node (ref "IC1") (pin "3") (pinfunction "W_3") (pintype "passive"))
      (node (ref "L3") (pin "2") (pinfunction "2_2") (pintype "passive"))
      (node (ref "R62") (pin "3") (pinfunction "2_3") (pintype "passive"))
      (node (ref "R63") (pin "1") (pinfunction "1_1") (pintype "passive"))
      (node (ref "U6") (pin "4") (pinfunction "RS+_4") (pintype "passive"))
    )
    (net (code "118") (name "Net-(LED1-ANODE)") (class "Default")
      (node (ref "LED1") (pin "1") (pinfunction "ANODE_1") (pintype "passive"))
      (node (ref "R65") (pin "1") (pinfunction "1_1") (pintype "passive"))
    )
    (net (code "119") (name "Net-(LED2-ANODE)") (class "Default")
      (node (ref "LED2") (pin "1") (pinfunction "ANODE_1") (pintype "passive"))
      (node (ref "R66") (pin "1") (pinfunction "1_1") (pintype "passive"))
    )
    (net (code "120") (name "Net-(LED3-ANODE)") (class "Default")
      (node (ref "LED3") (pin "1") (pinfunction "ANODE_1") (pintype "passive"))
      (node (ref "R69") (pin "2") (pinfunction "2_2") (pintype "passive"))
    )
    (net (code "121") (name "Net-(LED4-ANODE)") (class "Default")
      (node (ref "LED4") (pin "1") (pinfunction "ANODE_1") (pintype "passive"))
      (node (ref "R70") (pin "2") (pinfunction "2_2") (pintype "passive"))
    )
    (net (code "122") (name "Net-(LED5-ANODE)") (class "Default")
      (node (ref "LED5") (pin "1") (pinfunction "ANODE_1") (pintype "passive"))
      (node (ref "R71") (pin "2") (pinfunction "2_2") (pintype "passive"))
    )
    (net (code "123") (name "Net-(LED6-ANODE)") (class "Default")
      (node (ref "LED6") (pin "1") (pinfunction "ANODE_1") (pintype "passive"))
      (node (ref "R72") (pin "1") (pinfunction "1_1") (pintype "passive"))
    )
    (net (code "124") (name "Net-(LED7-ANODE)") (class "Default")
      (node (ref "LED7") (pin "1") (pinfunction "ANODE_1") (pintype "passive"))
      (node (ref "R75") (pin "1") (pinfunction "1_1") (pintype "passive"))
    )
    (net (code "125") (name "Net-(LED8-ANODE)") (class "Default")
      (node (ref "LED8") (pin "1") (pinfunction "ANODE_1") (pintype "passive"))
      (node (ref "R76") (pin "2") (pinfunction "2_2") (pintype "passive"))
    )
    (net (code "126") (name "Net-(LED9-ANODE)") (class "Default")
      (node (ref "LED9") (pin "1") (pinfunction "ANODE_1") (pintype "passive"))
      (node (ref "R81") (pin "1") (pinfunction "1_1") (pintype "passive"))
    )
    (net (code "127") (name "Net-(LED10-ANODE)") (class "Default")
      (node (ref "LED10") (pin "1") (pinfunction "ANODE_1") (pintype "passive"))
      (node (ref "R80") (pin "2") (pinfunction "2_2") (pintype "passive"))
    )
    (net (code "128") (name "Net-(LED11-ANODE)") (class "Default")
      (node (ref "LED11") (pin "1") (pinfunction "ANODE_1") (pintype "passive"))
      (node (ref "R86") (pin "2") (pinfunction "2_2") (pintype "passive"))
    )
    (net (code "129") (name "Net-(LED12-ANODE)") (class "Default")
      (node (ref "LED12") (pin "1") (pinfunction "ANODE_1") (pintype "passive"))
      (node (ref "R85") (pin "1") (pinfunction "1_1") (pintype "passive"))
    )
    (net (code "130") (name "Net-(LED13-ANODE)") (class "Default")
      (node (ref "LED13") (pin "1") (pinfunction "ANODE_1") (pintype "passive"))
      (node (ref "R88") (pin "1") (pinfunction "1_1") (pintype "passive"))
    )
    (net (code "131") (name "Net-(LED14-ANODE)") (class "Default")
      (node (ref "LED14") (pin "1") (pinfunction "ANODE_1") (pintype "passive"))
      (node (ref "R89") (pin "1") (pinfunction "1_1") (pintype "passive"))
    )
    (net (code "132") (name "Net-(LED15-ANODE)") (class "Default")
      (node (ref "LED15") (pin "1") (pinfunction "ANODE_1") (pintype "passive"))
      (node (ref "R90") (pin "2") (pinfunction "2_2") (pintype "passive"))
    )
    (net (code "133") (name "Net-(LED16-ANODE)") (class "Default")
      (node (ref "LED16") (pin "1") (pinfunction "ANODE_1") (pintype "passive"))
      (node (ref "R91") (pin "2") (pinfunction "2_2") (pintype "passive"))
    )
    (net (code "134") (name "Net-(LED17-ANODE)") (class "Default")
      (node (ref "LED17") (pin "1") (pinfunction "ANODE_1") (pintype "passive"))
      (node (ref "R98") (pin "2") (pinfunction "2_2") (pintype "passive"))
    )
    (net (code "135") (name "Net-(LED18-ANODE)") (class "Default")
      (node (ref "LED18") (pin "1") (pinfunction "ANODE_1") (pintype "passive"))
      (node (ref "R99") (pin "1") (pinfunction "1_1") (pintype "passive"))
    )
    (net (code "136") (name "Net-(LED19-ANODE)") (class "Default")
      (node (ref "LED19") (pin "1") (pinfunction "ANODE_1") (pintype "passive"))
      (node (ref "R102") (pin "1") (pinfunction "1_1") (pintype "passive"))
    )
    (net (code "137") (name "Net-(LED20-ANODE)") (class "Default")
      (node (ref "LED20") (pin "1") (pinfunction "ANODE_1") (pintype "passive"))
      (node (ref "R103") (pin "2") (pinfunction "2_2") (pintype "passive"))
    )
    (net (code "138") (name "Net-(LED21-ANODE)") (class "Default")
      (node (ref "LED21") (pin "1") (pinfunction "ANODE_1") (pintype "passive"))
      (node (ref "R107") (pin "1") (pinfunction "1_1") (pintype "passive"))
    )
    (net (code "139") (name "Net-(LED22-ANODE)") (class "Default")
      (node (ref "LED22") (pin "1") (pinfunction "ANODE_1") (pintype "passive"))
      (node (ref "R106") (pin "2") (pinfunction "2_2") (pintype "passive"))
    )
    (net (code "140") (name "Net-(LED23-ANODE)") (class "Default")
      (node (ref "LED23") (pin "1") (pinfunction "ANODE_1") (pintype "passive"))
      (node (ref "R109") (pin "2") (pinfunction "2_2") (pintype "passive"))
    )
    (net (code "141") (name "Net-(LED24-ANODE)") (class "Default")
      (node (ref "LED24") (pin "1") (pinfunction "ANODE_1") (pintype "passive"))
      (node (ref "R108") (pin "1") (pinfunction "1_1") (pintype "passive"))
    )
    (net (code "142") (name "Net-(LED25-ANODE)") (class "Default")
      (node (ref "LED25") (pin "1") (pinfunction "ANODE_1") (pintype "passive"))
      (node (ref "R112") (pin "1") (pinfunction "1_1") (pintype "passive"))
    )
    (net (code "143") (name "Net-(LED26-ANODE)") (class "Default")
      (node (ref "LED26") (pin "1") (pinfunction "ANODE_1") (pintype "passive"))
      (node (ref "R113") (pin "1") (pinfunction "1_1") (pintype "passive"))
    )
    (net (code "144") (name "Net-(LED27-ANODE)") (class "Default")
      (node (ref "LED27") (pin "1") (pinfunction "ANODE_1") (pintype "passive"))
      (node (ref "R114") (pin "2") (pinfunction "2_2") (pintype "passive"))
    )
    (net (code "145") (name "Net-(LED28-ANODE)") (class "Default")
      (node (ref "LED28") (pin "1") (pinfunction "ANODE_1") (pintype "passive"))
      (node (ref "R115") (pin "2") (pinfunction "2_2") (pintype "passive"))
    )
    (net (code "146") (name "Net-(LED29-ANODE)") (class "Default")
      (node (ref "LED29") (pin "1") (pinfunction "ANODE_1") (pintype "passive"))
      (node (ref "R122") (pin "1") (pinfunction "1_1") (pintype "passive"))
    )
    (net (code "147") (name "Net-(LED30-ANODE)") (class "Default")
      (node (ref "LED30") (pin "1") (pinfunction "ANODE_1") (pintype "passive"))
      (node (ref "R123") (pin "1") (pinfunction "1_1") (pintype "passive"))
    )
    (net (code "148") (name "Net-(LED31-ANODE)") (class "Default")
      (node (ref "LED31") (pin "1") (pinfunction "ANODE_1") (pintype "passive"))
      (node (ref "R121") (pin "2") (pinfunction "2_2") (pintype "passive"))
    )
    (net (code "149") (name "Net-(LED32-ANODE)") (class "Default")
      (node (ref "LED32") (pin "1") (pinfunction "ANODE_1") (pintype "passive"))
      (node (ref "R124") (pin "1") (pinfunction "1_1") (pintype "passive"))
    )
    (net (code "150") (name "Net-(LED33-ANODE)") (class "Default")
      (node (ref "LED33") (pin "1") (pinfunction "ANODE_1") (pintype "passive"))
      (node (ref "R126") (pin "2") (pinfunction "2_2") (pintype "passive"))
    )
    (net (code "151") (name "Net-(LED34-ANODE)") (class "Default")
      (node (ref "LED34") (pin "1") (pinfunction "ANODE_1") (pintype "passive"))
      (node (ref "R127") (pin "2") (pinfunction "2_2") (pintype "passive"))
    )
    (net (code "152") (name "Net-(LED35-ANODE)") (class "Default")
      (node (ref "LED35") (pin "1") (pinfunction "ANODE_1") (pintype "passive"))
      (node (ref "R125") (pin "1") (pinfunction "1_1") (pintype "passive"))
    )
    (net (code "153") (name "Net-(LED36-ANODE)") (class "Default")
      (node (ref "LED36") (pin "1") (pinfunction "ANODE_1") (pintype "passive"))
      (node (ref "R128") (pin "2") (pinfunction "2_2") (pintype "passive"))
    )
    (net (code "154") (name "Net-(LED37-ANODE)") (class "Default")
      (node (ref "LED37") (pin "1") (pinfunction "ANODE_1") (pintype "passive"))
      (node (ref "R130") (pin "1") (pinfunction "1_1") (pintype "passive"))
    )
    (net (code "155") (name "Net-(LED38-ANODE)") (class "Default")
      (node (ref "LED38") (pin "1") (pinfunction "ANODE_1") (pintype "passive"))
      (node (ref "R131") (pin "1") (pinfunction "1_1") (pintype "passive"))
    )
    (net (code "156") (name "Net-(LED39-ANODE)") (class "Default")
      (node (ref "LED39") (pin "1") (pinfunction "ANODE_1") (pintype "passive"))
      (node (ref "R132") (pin "2") (pinfunction "2_2") (pintype "passive"))
    )
    (net (code "157") (name "Net-(LED40-ANODE)") (class "Default")
      (node (ref "LED40") (pin "1") (pinfunction "ANODE_1") (pintype "passive"))
      (node (ref "R133") (pin "2") (pinfunction "2_2") (pintype "passive"))
    )
    (net (code "158") (name "Net-(OSW1A-A+)") (class "Default")
      (node (ref "OSW1") (pin "1") (pinfunction "A+_1") (pintype "passive"))
      (node (ref "Q4") (pin "4") (pinfunction "D2_4") (pintype "passive"))
      (node (ref "Q4") (pin "6") (pinfunction "D1_6") (pintype "passive"))
    )
    (net (code "159") (name "Net-(OSW1A-B+)") (class "Default")
      (node (ref "OSW1") (pin "8") (pinfunction "B+_8") (pintype "passive"))
      (node (ref "Q3") (pin "4") (pinfunction "D2_4") (pintype "passive"))
      (node (ref "Q3") (pin "6") (pinfunction "D1_6") (pintype "passive"))
    )
    (net (code "160") (name "Net-(OSW1B-A+)") (class "Default")
      (node (ref "OSW1") (pin "21") (pinfunction "A+_21") (pintype "passive"))
      (node (ref "Q10") (pin "4") (pinfunction "D2_4") (pintype "passive"))
      (node (ref "Q10") (pin "6") (pinfunction "D1_6") (pintype "passive"))
    )
    (net (code "161") (name "Net-(OSW1B-B+)") (class "Default")
      (node (ref "OSW1") (pin "28") (pinfunction "B+_28") (pintype "passive"))
      (node (ref "Q9") (pin "4") (pinfunction "D2_4") (pintype "passive"))
      (node (ref "Q9") (pin "6") (pinfunction "D1_6") (pintype "passive"))
    )
    (net (code "162") (name "Net-(OSW2-A+)") (class "Default")
      (node (ref "OSW2") (pin "1") (pinfunction "A+_1") (pintype "passive"))
      (node (ref "Q7") (pin "4") (pinfunction "D2_4") (pintype "passive"))
      (node (ref "Q7") (pin "6") (pinfunction "D1_6") (pintype "passive"))
    )
    (net (code "163") (name "Net-(OSW3A-A+)") (class "Default")
      (node (ref "OSW3") (pin "A10") (pinfunction "A+_A10") (pintype "passive"))
      (node (ref "Q1") (pin "4") (pinfunction "D2_4") (pintype "passive"))
      (node (ref "Q1") (pin "6") (pinfunction "D1_6") (pintype "passive"))
    )
    (net (code "164") (name "Net-(OSW3A-A-)") (class "Default")
      (node (ref "OSW3") (pin "A6") (pinfunction "A-_A6") (pintype "passive"))
      (node (ref "U7") (pin "4") (pinfunction "OB_4") (pintype "passive"))
    )
    (net (code "165") (name "Net-(OSW3A-B-)") (class "Default")
      (node (ref "OSW3") (pin "A5") (pinfunction "B-_A5") (pintype "passive"))
      (node (ref "U7") (pin "1") (pinfunction "OA_1") (pintype "passive"))
    )
    (net (code "166") (name "Net-(OSW3B-A+)") (class "Default")
      (node (ref "OSW3") (pin "B10") (pinfunction "A+_B10") (pintype "passive"))
      (node (ref "Q13") (pin "4") (pinfunction "D2_4") (pintype "passive"))
      (node (ref "Q13") (pin "6") (pinfunction "D1_6") (pintype "passive"))
    )
    (net (code "167") (name "Net-(OSW3B-A-)") (class "Default")
      (node (ref "OSW3") (pin "B6") (pinfunction "A-_B6") (pintype "passive"))
      (node (ref "U10") (pin "4") (pinfunction "OB_4") (pintype "passive"))
    )
    (net (code "168") (name "Net-(OSW3B-B-)") (class "Default")
      (node (ref "OSW3") (pin "B5") (pinfunction "B-_B5") (pintype "passive"))
      (node (ref "U10") (pin "1") (pinfunction "OA_1") (pintype "passive"))
    )
    (net (code "169") (name "Net-(OSW3C-A+)") (class "Default")
      (node (ref "OSW3") (pin "C10") (pinfunction "A+_C10") (pintype "passive"))
      (node (ref "Q18") (pin "4") (pinfunction "D2_4") (pintype "passive"))
      (node (ref "Q18") (pin "6") (pinfunction "D1_6") (pintype "passive"))
    )
    (net (code "170") (name "Net-(OSW3C-A-)") (class "Default")
      (node (ref "OSW3") (pin "C6") (pinfunction "A-_C6") (pintype "passive"))
      (node (ref "U12") (pin "4") (pinfunction "OB_4") (pintype "passive"))
    )
    (net (code "171") (name "Net-(OSW3C-B-)") (class "Default")
      (node (ref "OSW3") (pin "C5") (pinfunction "B-_C5") (pintype "passive"))
      (node (ref "U12") (pin "1") (pinfunction "OA_1") (pintype "passive"))
    )
    (net (code "172") (name "Net-(OSW4-A-)") (class "Default")
      (node (ref "OSW4") (pin "6") (pinfunction "A-_6") (pintype "passive"))
      (node (ref "U9") (pin "1") (pinfunction "OA_1") (pintype "passive"))
    )
    (net (code "173") (name "Net-(OSW4-B-)") (class "Default")
      (node (ref "OSW4") (pin "7") (pinfunction "B-_7") (pintype "passive"))
      (node (ref "U9") (pin "4") (pinfunction "OB_4") (pintype "passive"))
    )
    (net (code "174") (name "Net-(OSW5A-A+)") (class "Default")
      (node (ref "OSW5") (pin "A10") (pinfunction "A+_A10") (pintype "passive"))
      (node (ref "Q15") (pin "4") (pinfunction "D2_4") (pintype "passive"))
      (node (ref "Q15") (pin "6") (pinfunction "D1_6") (pintype "passive"))
    )
    (net (code "175") (name "Net-(OSW5A-A-)") (class "Default")
      (node (ref "OSW5") (pin "A6") (pinfunction "A-_A6") (pintype "passive"))
      (node (ref "U11") (pin "4") (pinfunction "OB_4") (pintype "passive"))
    )
    (net (code "176") (name "Net-(OSW5A-B-)") (class "Default")
      (node (ref "OSW5") (pin "A5") (pinfunction "B-_A5") (pintype "passive"))
      (node (ref "U11") (pin "1") (pinfunction "OA_1") (pintype "passive"))
    )
    (net (code "177") (name "Net-(OSW5B-A+)") (class "Default")
      (node (ref "OSW5") (pin "B10") (pinfunction "A+_B10") (pintype "passive"))
      (node (ref "Q21") (pin "4") (pinfunction "D2_4") (pintype "passive"))
      (node (ref "Q21") (pin "6") (pinfunction "D1_6") (pintype "passive"))
    )
    (net (code "178") (name "Net-(OSW5B-A-)") (class "Default")
      (node (ref "OSW5") (pin "B6") (pinfunction "A-_B6") (pintype "passive"))
      (node (ref "U14") (pin "4") (pinfunction "OB_4") (pintype "passive"))
    )
    (net (code "179") (name "Net-(OSW5B-B-)") (class "Default")
      (node (ref "OSW5") (pin "B5") (pinfunction "B-_B5") (pintype "passive"))
      (node (ref "U14") (pin "1") (pinfunction "OA_1") (pintype "passive"))
    )
    (net (code "180") (name "Net-(OSW6-A+)") (class "Default")
      (node (ref "OSW6") (pin "10") (pinfunction "A+_10") (pintype "passive"))
      (node (ref "Q17") (pin "4") (pinfunction "D2_4") (pintype "passive"))
      (node (ref "Q17") (pin "6") (pinfunction "D1_6") (pintype "passive"))
    )
    (net (code "181") (name "Net-(OSW6-A-)") (class "Default")
      (node (ref "OSW6") (pin "6") (pinfunction "A-_6") (pintype "passive"))
      (node (ref "U13") (pin "4") (pinfunction "OB_4") (pintype "passive"))
    )
    (net (code "182") (name "Net-(OSW6-B-)") (class "Default")
      (node (ref "OSW6") (pin "5") (pinfunction "B-_5") (pintype "passive"))
      (node (ref "U13") (pin "1") (pinfunction "OA_1") (pintype "passive"))
    )
    (net (code "183") (name "Net-(Q1-G1)") (class "Default")
      (node (ref "Q1") (pin "1") (pinfunction "G1_1") (pintype "passive"))
      (node (ref "Q1") (pin "3") (pinfunction "G2_3") (pintype "passive"))
      (node (ref "Q2") (pin "c") (pintype "passive"))
      (node (ref "R74") (pin "2") (pinfunction "2_2") (pintype "passive"))
    )
    (net (code "184") (name "Net-(Q2-Padb)") (class "Default")
      (node (ref "Q2") (pin "b") (pintype "passive"))
      (node (ref "R79") (pin "1") (pinfunction "1_1") (pintype "passive"))
    )
    (net (code "185") (name "Net-(Q3-G1)") (class "Default")
      (node (ref "Q3") (pin "1") (pinfunction "G1_1") (pintype "passive"))
      (node (ref "Q3") (pin "3") (pinfunction "G2_3") (pintype "passive"))
      (node (ref "Q6") (pin "c") (pintype "passive"))
      (node (ref "R77") (pin "2") (pinfunction "2_2") (pintype "passive"))
    )
    (net (code "186") (name "Net-(Q4-G1)") (class "Default")
      (node (ref "Q4") (pin "1") (pinfunction "G1_1") (pintype "passive"))
      (node (ref "Q4") (pin "3") (pinfunction "G2_3") (pintype "passive"))
      (node (ref "Q5") (pin "c") (pintype "passive"))
      (node (ref "R78") (pin "2") (pinfunction "2_2") (pintype "passive"))
    )
    (net (code "187") (name "Net-(Q5-Padb)") (class "Default")
      (node (ref "Q5") (pin "b") (pintype "passive"))
      (node (ref "R83") (pin "1") (pinfunction "1_1") (pintype "passive"))
    )
    (net (code "188") (name "Net-(Q6-Padb)") (class "Default")
      (node (ref "Q6") (pin "b") (pintype "passive"))
      (node (ref "R82") (pin "1") (pinfunction "1_1") (pintype "passive"))
    )
    (net (code "189") (name "Net-(Q7-G1)") (class "Default")
      (node (ref "Q7") (pin "1") (pinfunction "G1_1") (pintype "passive"))
      (node (ref "Q7") (pin "3") (pinfunction "G2_3") (pintype "passive"))
      (node (ref "Q8") (pin "c") (pintype "passive"))
      (node (ref "R84") (pin "2") (pinfunction "2_2") (pintype "passive"))
    )
    (net (code "190") (name "Net-(Q8-Padb)") (class "Default")
      (node (ref "Q8") (pin "b") (pintype "passive"))
      (node (ref "R87") (pin "1") (pinfunction "1_1") (pintype "passive"))
    )
    (net (code "191") (name "Net-(Q9-G1)") (class "Default")
      (node (ref "Q12") (pin "c") (pintype "passive"))
      (node (ref "Q9") (pin "1") (pinfunction "G1_1") (pintype "passive"))
      (node (ref "Q9") (pin "3") (pinfunction "G2_3") (pintype "passive"))
      (node (ref "R92") (pin "2") (pinfunction "2_2") (pintype "passive"))
    )
    (net (code "192") (name "Net-(Q10-G1)") (class "Default")
      (node (ref "Q10") (pin "1") (pinfunction "G1_1") (pintype "passive"))
      (node (ref "Q10") (pin "3") (pinfunction "G2_3") (pintype "passive"))
      (node (ref "Q11") (pin "c") (pintype "passive"))
      (node (ref "R93") (pin "2") (pinfunction "2_2") (pintype "passive"))
    )
    (net (code "193") (name "Net-(Q11-Padb)") (class "Default")
      (node (ref "Q11") (pin "b") (pintype "passive"))
      (node (ref "R95") (pin "1") (pinfunction "1_1") (pintype "passive"))
    )
    (net (code "194") (name "Net-(Q12-Padb)") (class "Default")
      (node (ref "Q12") (pin "b") (pintype "passive"))
      (node (ref "R94") (pin "1") (pinfunction "1_1") (pintype "passive"))
    )
    (net (code "195") (name "Net-(Q13-G1)") (class "Default")
      (node (ref "Q13") (pin "1") (pinfunction "G1_1") (pintype "passive"))
      (node (ref "Q13") (pin "3") (pinfunction "G2_3") (pintype "passive"))
      (node (ref "Q14") (pin "c") (pintype "passive"))
      (node (ref "R100") (pin "2") (pinfunction "2_2") (pintype "passive"))
    )
    (net (code "196") (name "Net-(Q14-Padb)") (class "Default")
      (node (ref "Q14") (pin "b") (pintype "passive"))
      (node (ref "R104") (pin "1") (pinfunction "1_1") (pintype "passive"))
    )
    (net (code "197") (name "Net-(Q15-G1)") (class "Default")
      (node (ref "Q15") (pin "1") (pinfunction "G1_1") (pintype "passive"))
      (node (ref "Q15") (pin "3") (pinfunction "G2_3") (pintype "passive"))
      (node (ref "Q16") (pin "c") (pintype "passive"))
      (node (ref "R110") (pin "2") (pinfunction "2_2") (pintype "passive"))
    )
    (net (code "198") (name "Net-(Q16-Padb)") (class "Default")
      (node (ref "Q16") (pin "b") (pintype "passive"))
      (node (ref "R111") (pin "1") (pinfunction "1_1") (pintype "passive"))
    )
    (net (code "199") (name "Net-(Q17-G1)") (class "Default")
      (node (ref "Q17") (pin "1") (pinfunction "G1_1") (pintype "passive"))
      (node (ref "Q17") (pin "3") (pinfunction "G2_3") (pintype "passive"))
      (node (ref "Q19") (pin "c") (pintype "passive"))
      (node (ref "R116") (pin "2") (pinfunction "2_2") (pintype "passive"))
    )
    (net (code "200") (name "Net-(Q18-G1)") (class "Default")
      (node (ref "Q18") (pin "1") (pinfunction "G1_1") (pintype "passive"))
      (node (ref "Q18") (pin "3") (pinfunction "G2_3") (pintype "passive"))
      (node (ref "Q20") (pin "c") (pintype "passive"))
      (node (ref "R117") (pin "2") (pinfunction "2_2") (pintype "passive"))
    )
    (net (code "201") (name "Net-(Q19-Padb)") (class "Default")
      (node (ref "Q19") (pin "b") (pintype "passive"))
      (node (ref "R118") (pin "1") (pinfunction "1_1") (pintype "passive"))
    )
    (net (code "202") (name "Net-(Q20-Padb)") (class "Default")
      (node (ref "Q20") (pin "b") (pintype "passive"))
      (node (ref "R119") (pin "1") (pinfunction "1_1") (pintype "passive"))
    )
    (net (code "203") (name "Net-(Q21-G1)") (class "Default")
      (node (ref "Q21") (pin "1") (pinfunction "G1_1") (pintype "passive"))
      (node (ref "Q21") (pin "3") (pinfunction "G2_3") (pintype "passive"))
      (node (ref "Q22") (pin "c") (pintype "passive"))
      (node (ref "R120") (pin "2") (pinfunction "2_2") (pintype "passive"))
    )
    (net (code "204") (name "Net-(Q22-Padb)") (class "Default")
      (node (ref "Q22") (pin "b") (pintype "passive"))
      (node (ref "R129") (pin "1") (pinfunction "1_1") (pintype "passive"))
    )
    (net (code "205") (name "Net-(R2-Pad2)") (class "Default")
      (node (ref "R2") (pin "2") (pinfunction "2_2") (pintype "passive"))
      (node (ref "R3") (pin "1") (pinfunction "1_1") (pintype "passive"))
    )
    (net (code "206") (name "Net-(U1-BOOT)") (class "Default")
      (node (ref "C4") (pin "2") (pinfunction "2_2") (pintype "passive"))
      (node (ref "U1") (pin "1") (pinfunction "BOOT_1") (pintype "passive"))
    )
    (net (code "207") (name "Net-(U1-COMP)") (class "Default")
      (node (ref "C13") (pin "1") (pinfunction "1_1") (pintype "passive"))
      (node (ref "R11") (pin "1") (pinfunction "1_1") (pintype "passive"))
      (node (ref "U1") (pin "6") (pinfunction "COMP_6") (pintype "passive"))
    )
    (net (code "208") (name "Net-(U1-EN)") (class "Default")
      (node (ref "R14") (pin "1") (pinfunction "1_1") (pintype "passive"))
      (node (ref "R8") (pin "2") (pinfunction "2_2") (pintype "passive"))
      (node (ref "U1") (pin "3") (pinfunction "EN_3") (pintype "passive"))
    )
    (net (code "209") (name "Net-(U1-SS)") (class "Default")
      (node (ref "C12") (pin "1") (pinfunction "1_1") (pintype "passive"))
      (node (ref "U1") (pin "4") (pinfunction "SS_4") (pintype "passive"))
    )
    (net (code "210") (name "Net-(U1-VSENSE)") (class "Default")
      (node (ref "R1") (pin "2") (pinfunction "2_2") (pintype "passive"))
      (node (ref "R2") (pin "1") (pinfunction "1_1") (pintype "passive"))
      (node (ref "U1") (pin "5") (pinfunction "VSENSE_5") (pintype "passive"))
    )
    (net (code "211") (name "Net-(U4-BOOT)") (class "Default")
      (node (ref "C18") (pin "2") (pinfunction "2_2") (pintype "passive"))
      (node (ref "U4") (pin "1") (pinfunction "BOOT_1") (pintype "passive"))
    )
    (net (code "212") (name "Net-(U4-COMP)") (class "Default")
      (node (ref "C23") (pin "1") (pinfunction "1_1") (pintype "passive"))
      (node (ref "R37") (pin "1") (pinfunction "1_1") (pintype "passive"))
      (node (ref "U4") (pin "6") (pinfunction "COMP_6") (pintype "passive"))
    )
    (net (code "213") (name "Net-(U4-EN)") (class "Default")
      (node (ref "R33") (pin "2") (pinfunction "2_2") (pintype "passive"))
      (node (ref "R40") (pin "1") (pinfunction "1_1") (pintype "passive"))
      (node (ref "U4") (pin "3") (pinfunction "EN_3") (pintype "passive"))
    )
    (net (code "214") (name "Net-(U4-SS)") (class "Default")
      (node (ref "C22") (pin "1") (pinfunction "1_1") (pintype "passive"))
      (node (ref "U4") (pin "4") (pinfunction "SS_4") (pintype "passive"))
    )
    (net (code "215") (name "Net-(U4-VSENSE)") (class "Default")
      (node (ref "R26") (pin "2") (pinfunction "2_2") (pintype "passive"))
      (node (ref "R27") (pin "1") (pinfunction "1_1") (pintype "passive"))
      (node (ref "U4") (pin "5") (pinfunction "VSENSE_5") (pintype "passive"))
    )
    (net (code "216") (name "Net-(U6-OUT)") (class "Default")
      (node (ref "R68") (pin "2") (pinfunction "2_2") (pintype "passive"))
      (node (ref "U6") (pin "6") (pinfunction "OUT_6") (pintype "passive"))
    )
    (net (code "217") (name "VOUT") (class "Default")
      (node (ref "R63") (pin "2") (pinfunction "2_2") (pintype "passive"))
      (node (ref "R64") (pin "2") (pinfunction "2_2") (pintype "passive"))
      (node (ref "SW2") (pin "3") (pinfunction "3_3") (pintype "passive"))
      (node (ref "U6") (pin "5") (pinfunction "RS-_5") (pintype "passive"))
    )
    (net (code "218") (name "V_OUT") (class "Default")
      (node (ref "JP3") (pin "1") (pinfunction "1_1") (pintype "passive"))
      (node (ref "JP3") (pin "2") (pinfunction "2_2") (pintype "passive"))
      (node (ref "OSW3") (pin "A1") (pinfunction "B+_A1") (pintype "passive"))
      (node (ref "OSW3") (pin "B1") (pinfunction "B+_B1") (pintype "passive"))
      (node (ref "OSW3") (pin "C1") (pinfunction "B+_C1") (pintype "passive"))
      (node (ref "OSW4") (pin "1") (pinfunction "A+_1") (pintype "passive"))
      (node (ref "OSW4") (pin "12") (pinfunction "B+_12") (pintype "passive"))
      (node (ref "OSW5") (pin "A1") (pinfunction "B+_A1") (pintype "passive"))
      (node (ref "OSW5") (pin "B1") (pinfunction "B+_B1") (pintype "passive"))
      (node (ref "OSW6") (pin "1") (pinfunction "B+_1") (pintype "passive"))
      (node (ref "Q1") (pin "2") (pinfunction "S2_2") (pintype "passive"))
      (node (ref "Q10") (pin "2") (pinfunction "S2_2") (pintype "passive"))
      (node (ref "Q13") (pin "2") (pinfunction "S2_2") (pintype "passive"))
      (node (ref "Q15") (pin "2") (pinfunction "S2_2") (pintype "passive"))
      (node (ref "Q17") (pin "2") (pinfunction "S2_2") (pintype "passive"))
      (node (ref "Q18") (pin "2") (pinfunction "S2_2") (pintype "passive"))
      (node (ref "Q21") (pin "2") (pinfunction "S2_2") (pintype "passive"))
      (node (ref "Q3") (pin "2") (pinfunction "S2_2") (pintype "passive"))
      (node (ref "Q4") (pin "2") (pinfunction "S2_2") (pintype "passive"))
      (node (ref "Q7") (pin "2") (pinfunction "S2_2") (pintype "passive"))
      (node (ref "Q9") (pin "2") (pinfunction "S2_2") (pintype "passive"))
      (node (ref "R100") (pin "1") (pinfunction "1_1") (pintype "passive"))
      (node (ref "R110") (pin "1") (pinfunction "1_1") (pintype "passive"))
      (node (ref "R116") (pin "1") (pinfunction "1_1") (pintype "passive"))
      (node (ref "R117") (pin "1") (pinfunction "1_1") (pintype "passive"))
      (node (ref "R120") (pin "1") (pinfunction "1_1") (pintype "passive"))
      (node (ref "R74") (pin "1") (pinfunction "1_1") (pintype "passive"))
      (node (ref "R77") (pin "1") (pinfunction "1_1") (pintype "passive"))
      (node (ref "R78") (pin "1") (pinfunction "1_1") (pintype "passive"))
      (node (ref "R84") (pin "1") (pinfunction "1_1") (pintype "passive"))
      (node (ref "R92") (pin "1") (pinfunction "1_1") (pintype "passive"))
      (node (ref "R93") (pin "1") (pinfunction "1_1") (pintype "passive"))
      (node (ref "SW2") (pin "C") (pinfunction "C_C") (pintype "passive"))
      (node (ref "U10") (pin "2") (pinfunction "+_2") (pintype "passive"))
      (node (ref "U10") (pin "3") (pinfunction "+_3") (pintype "passive"))
      (node (ref "U11") (pin "2") (pinfunction "+_2") (pintype "passive"))
      (node (ref "U11") (pin "3") (pinfunction "+_3") (pintype "passive"))
      (node (ref "U12") (pin "2") (pinfunction "+_2") (pintype "passive"))
      (node (ref "U12") (pin "3") (pinfunction "+_3") (pintype "passive"))
      (node (ref "U13") (pin "2") (pinfunction "+_2") (pintype "passive"))
      (node (ref "U13") (pin "3") (pinfunction "+_3") (pintype "passive"))
      (node (ref "U14") (pin "2") (pinfunction "+_2") (pintype "passive"))
      (node (ref "U14") (pin "3") (pinfunction "+_3") (pintype "passive"))
      (node (ref "U7") (pin "2") (pinfunction "+_2") (pintype "passive"))
      (node (ref "U7") (pin "3") (pinfunction "+_3") (pintype "passive"))
      (node (ref "U9") (pin "2") (pinfunction "+_2") (pintype "passive"))
      (node (ref "U9") (pin "3") (pinfunction "+_3") (pintype "passive"))
    )
    (net (code "219") (name "unconnected-(FPC1-RX4-Pad4)") (class "Default")
      (node (ref "FPC1") (pin "4") (pinfunction "RX4_4") (pintype "passive"))
    )
    (net (code "220") (name "unconnected-(FPC1-TX4-Pad7)") (class "Default")
      (node (ref "FPC1") (pin "7") (pinfunction "TX4_7") (pintype "passive"))
    )
    (net (code "221") (name "unconnected-(KEY2-Pad2)") (class "Default")
      (node (ref "KEY2") (pin "2") (pinfunction "2_2") (pintype "passive"))
    )
    (net (code "222") (name "unconnected-(KEY2-Pad4)") (class "Default")
      (node (ref "KEY2") (pin "4") (pinfunction "4_4") (pintype "passive"))
    )
    (net (code "223") (name "unconnected-(KEY3-Pad2)") (class "Default")
      (node (ref "KEY3") (pin "2") (pinfunction "2_2") (pintype "passive"))
    )
    (net (code "224") (name "unconnected-(KEY3-Pad4)") (class "Default")
      (node (ref "KEY3") (pin "4") (pinfunction "4_4") (pintype "passive"))
    )
    (net (code "225") (name "unconnected-(KEY4-Pad2)") (class "Default")
      (node (ref "KEY4") (pin "2") (pinfunction "2_2") (pintype "passive"))
    )
    (net (code "226") (name "unconnected-(KEY4-Pad4)") (class "Default")
      (node (ref "KEY4") (pin "4") (pinfunction "4_4") (pintype "passive"))
    )
    (net (code "227") (name "unconnected-(KEY5-Pad2)") (class "Default")
      (node (ref "KEY5") (pin "2") (pinfunction "2_2") (pintype "passive"))
    )
    (net (code "228") (name "unconnected-(KEY5-Pad4)") (class "Default")
      (node (ref "KEY5") (pin "4") (pinfunction "4_4") (pintype "passive"))
    )
    (net (code "229") (name "unconnected-(SW1-Pad3)") (class "Default")
      (node (ref "SW1") (pin "3") (pinfunction "3_3") (pintype "passive"))
    )
    (net (code "230") (name "unconnected-(SW2-Pad0)") (class "Default")
      (node (ref "SW2") (pin "0") (pinfunction "0_0") (pintype "passive"))
    )
    (net (code "231") (name "unconnected-(SW2-Pad0)_1") (class "Default")
      (node (ref "SW2") (pin "0") (pinfunction "0_0") (pintype "passive"))
    )
    (net (code "232") (name "unconnected-(SW2-Pad0)_2") (class "Default")
      (node (ref "SW2") (pin "0") (pinfunction "0_0") (pintype "passive"))
    )
    (net (code "233") (name "unconnected-(U2-PC14-OSC32_IN-Pad3)") (class "Default")
      (node (ref "U2") (pin "3") (pinfunction "PC14-OSC32_IN_3") (pintype "passive"))
    )
    (net (code "234") (name "unconnected-(U2-PC15-OSC32_OUT-Pad4)") (class "Default")
      (node (ref "U2") (pin "4") (pinfunction "PC15-OSC32_OUT_4") (pintype "passive"))
    )
    (net (code "235") (name "unconnected-(U2-PH0_-_OSC_IN-Pad5)") (class "Default")
      (node (ref "U2") (pin "5") (pinfunction "PH0_-_OSC_IN_5") (pintype "passive"))
    )
    (net (code "236") (name "unconnected-(U2-PH1_-OSC_OUT-Pad6)") (class "Default")
      (node (ref "U2") (pin "6") (pinfunction "PH1_-OSC_OUT_6") (pintype "passive"))
    )
    (net (code "237") (name "unconnected-(U8-CTS-Pad23)") (class "Default")
      (node (ref "U8") (pin "23") (pinfunction "CTS_23") (pintype "passive"))
    )
    (net (code "238") (name "unconnected-(U8-DCD-Pad1)") (class "Default")
      (node (ref "U8") (pin "1") (pinfunction "DCD_1") (pintype "passive"))
    )
    (net (code "239") (name "unconnected-(U8-DSR-Pad27)") (class "Default")
      (node (ref "U8") (pin "27") (pinfunction "DSR_27") (pintype "passive"))
    )
    (net (code "240") (name "unconnected-(U8-DTR-Pad28)") (class "Default")
      (node (ref "U8") (pin "28") (pinfunction "DTR_28") (pintype "passive"))
    )
    (net (code "241") (name "unconnected-(U8-EP-Pad29)") (class "Default")
      (node (ref "U8") (pin "29") (pinfunction "EP_29") (pintype "passive"))
    )
    (net (code "242") (name "unconnected-(U8-NC-Pad10)") (class "Default")
      (node (ref "U8") (pin "10") (pinfunction "NC_10") (pintype "passive"))
    )
    (net (code "243") (name "unconnected-(U8-NC-Pad13)") (class "Default")
      (node (ref "U8") (pin "13") (pinfunction "NC_13") (pintype "passive"))
    )
    (net (code "244") (name "unconnected-(U8-NC-Pad14)") (class "Default")
      (node (ref "U8") (pin "14") (pinfunction "NC_14") (pintype "passive"))
    )
    (net (code "245") (name "unconnected-(U8-NC-Pad15)") (class "Default")
      (node (ref "U8") (pin "15") (pinfunction "NC_15") (pintype "passive"))
    )
    (net (code "246") (name "unconnected-(U8-NC-Pad16)") (class "Default")
      (node (ref "U8") (pin "16") (pinfunction "NC_16") (pintype "passive"))
    )
    (net (code "247") (name "unconnected-(U8-NC-Pad17)") (class "Default")
      (node (ref "U8") (pin "17") (pinfunction "NC_17") (pintype "passive"))
    )
    (net (code "248") (name "unconnected-(U8-NC-Pad18)") (class "Default")
      (node (ref "U8") (pin "18") (pinfunction "NC_18") (pintype "passive"))
    )
    (net (code "249") (name "unconnected-(U8-NC-Pad19)") (class "Default")
      (node (ref "U8") (pin "19") (pinfunction "NC_19") (pintype "passive"))
    )
    (net (code "250") (name "unconnected-(U8-NC-Pad20)") (class "Default")
      (node (ref "U8") (pin "20") (pinfunction "NC_20") (pintype "passive"))
    )
    (net (code "251") (name "unconnected-(U8-NC-Pad21)") (class "Default")
      (node (ref "U8") (pin "21") (pinfunction "NC_21") (pintype "passive"))
    )
    (net (code "252") (name "unconnected-(U8-NC-Pad22)") (class "Default")
      (node (ref "U8") (pin "22") (pinfunction "NC_22") (pintype "passive"))
    )
    (net (code "253") (name "unconnected-(U8-RI-Pad2)") (class "Default")
      (node (ref "U8") (pin "2") (pinfunction "RI_2") (pintype "passive"))
    )
    (net (code "254") (name "unconnected-(U8-RST#-Pad9)") (class "Default")
      (node (ref "U8") (pin "9") (pinfunction "RST#_9") (pintype "passive"))
    )
    (net (code "255") (name "unconnected-(U8-RTS-Pad24)") (class "Default")
      (node (ref "U8") (pin "24") (pinfunction "RTS_24") (pintype "passive"))
    )
    (net (code "256") (name "unconnected-(U8-SUSPEND#-Pad11)") (class "Default")
      (node (ref "U8") (pin "11") (pinfunction "SUSPEND#_11") (pintype "passive"))
    )
    (net (code "257") (name "unconnected-(U8-SUSPEND-Pad12)") (class "Default")
      (node (ref "U8") (pin "12") (pinfunction "SUSPEND_12") (pintype "passive"))
    )
  )
)
